# all_Slaveboard_2020.net
KiCad netlist of a schematic drawn in Altium Designer
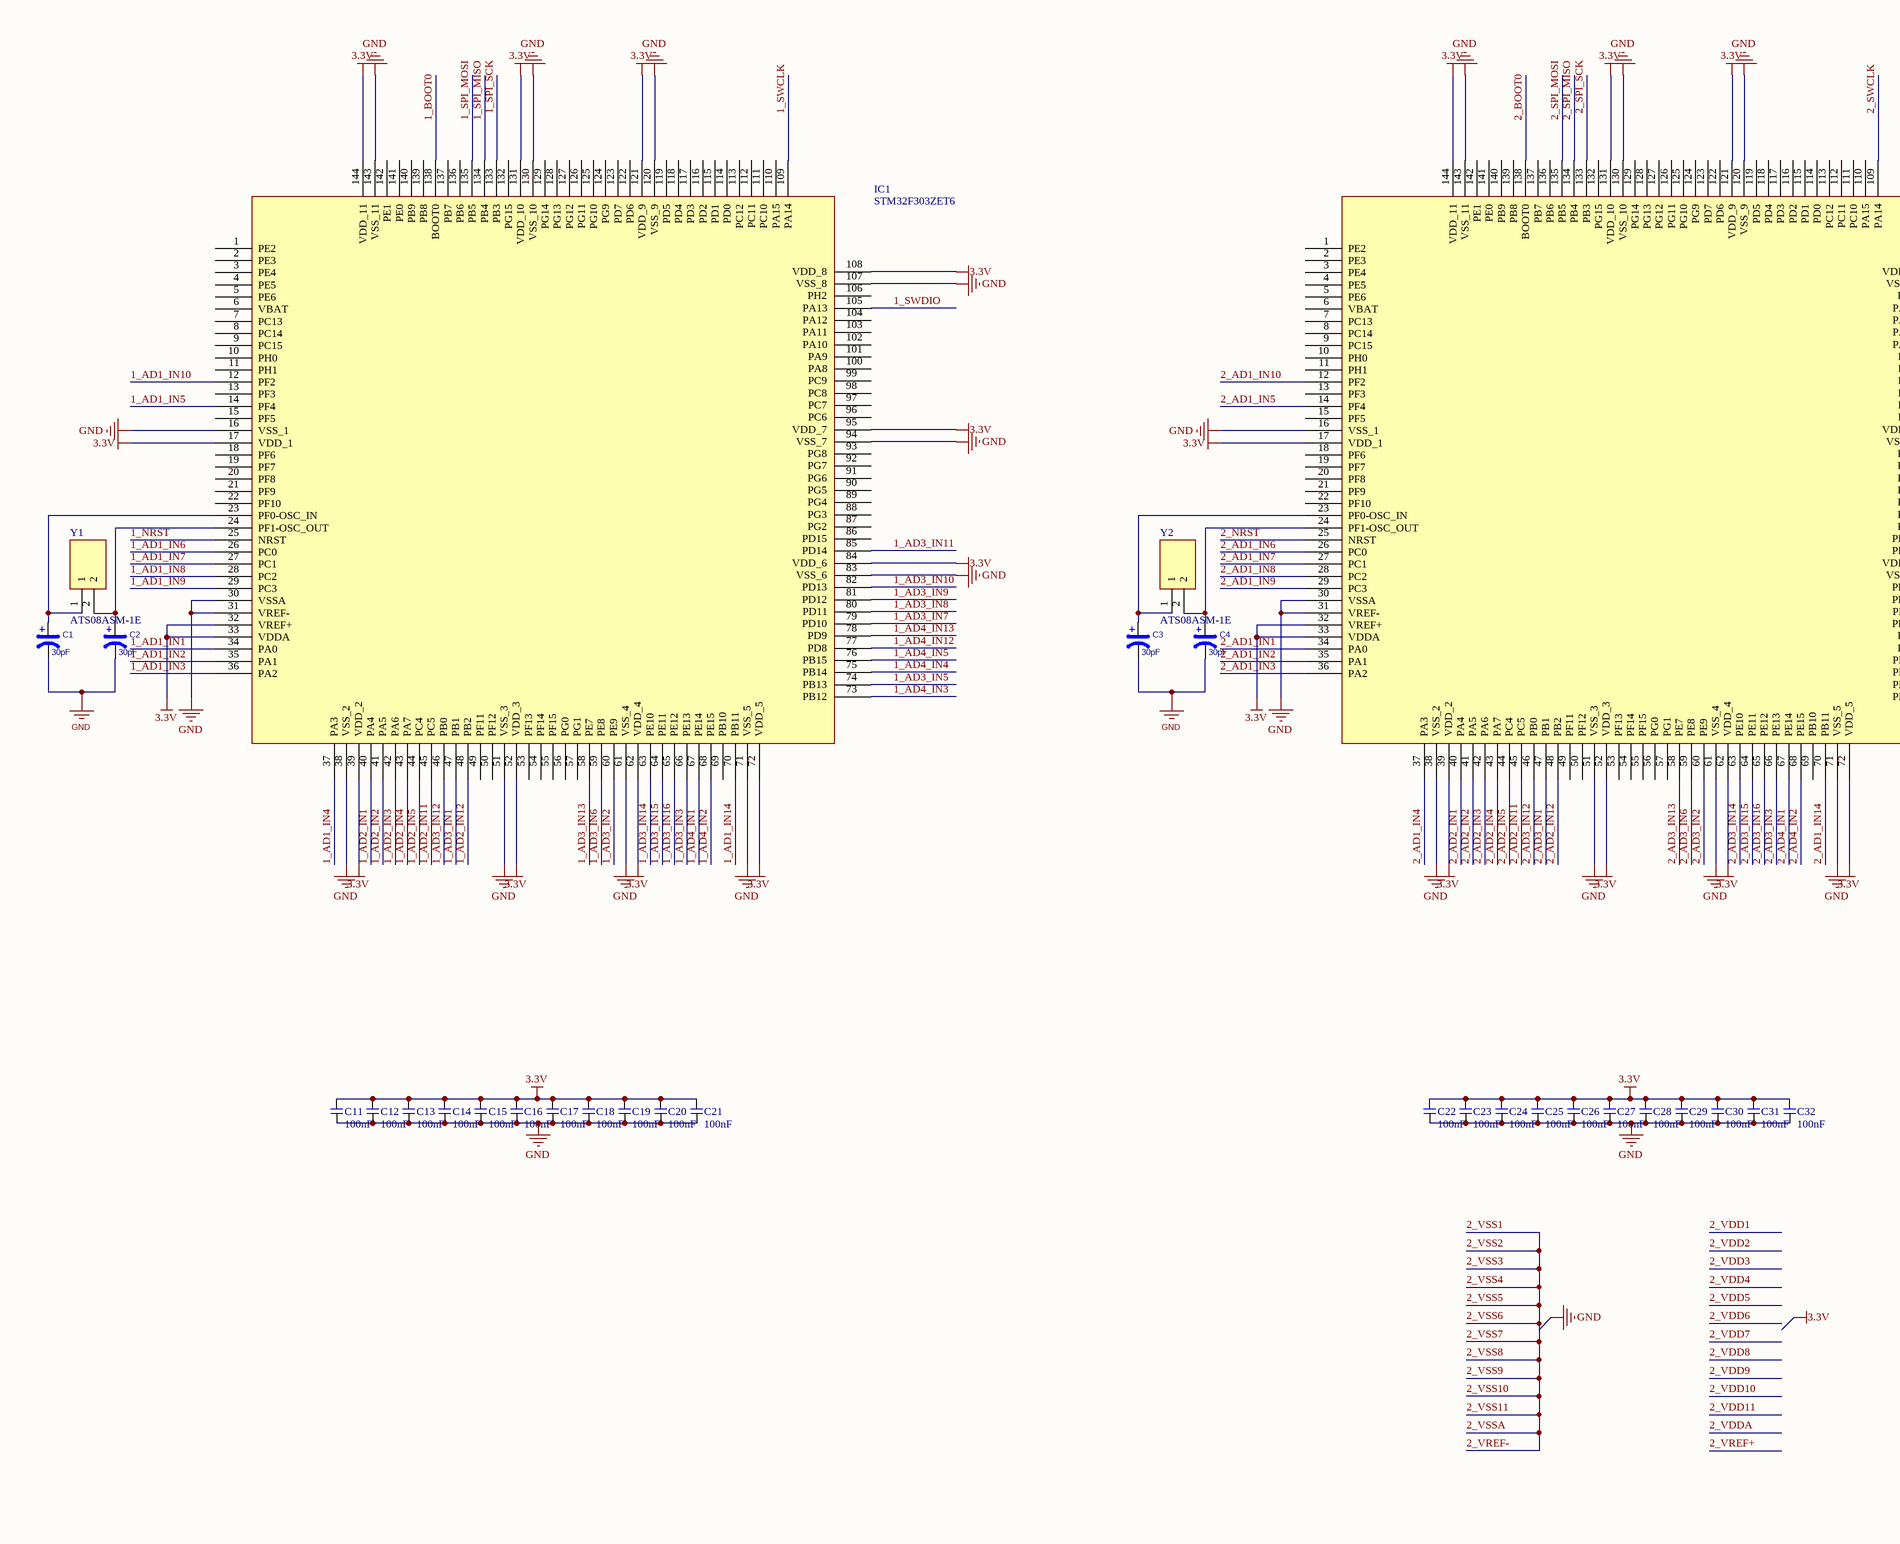
[diagram p0: all_Slaveboard_2020.SchDoc, top left]
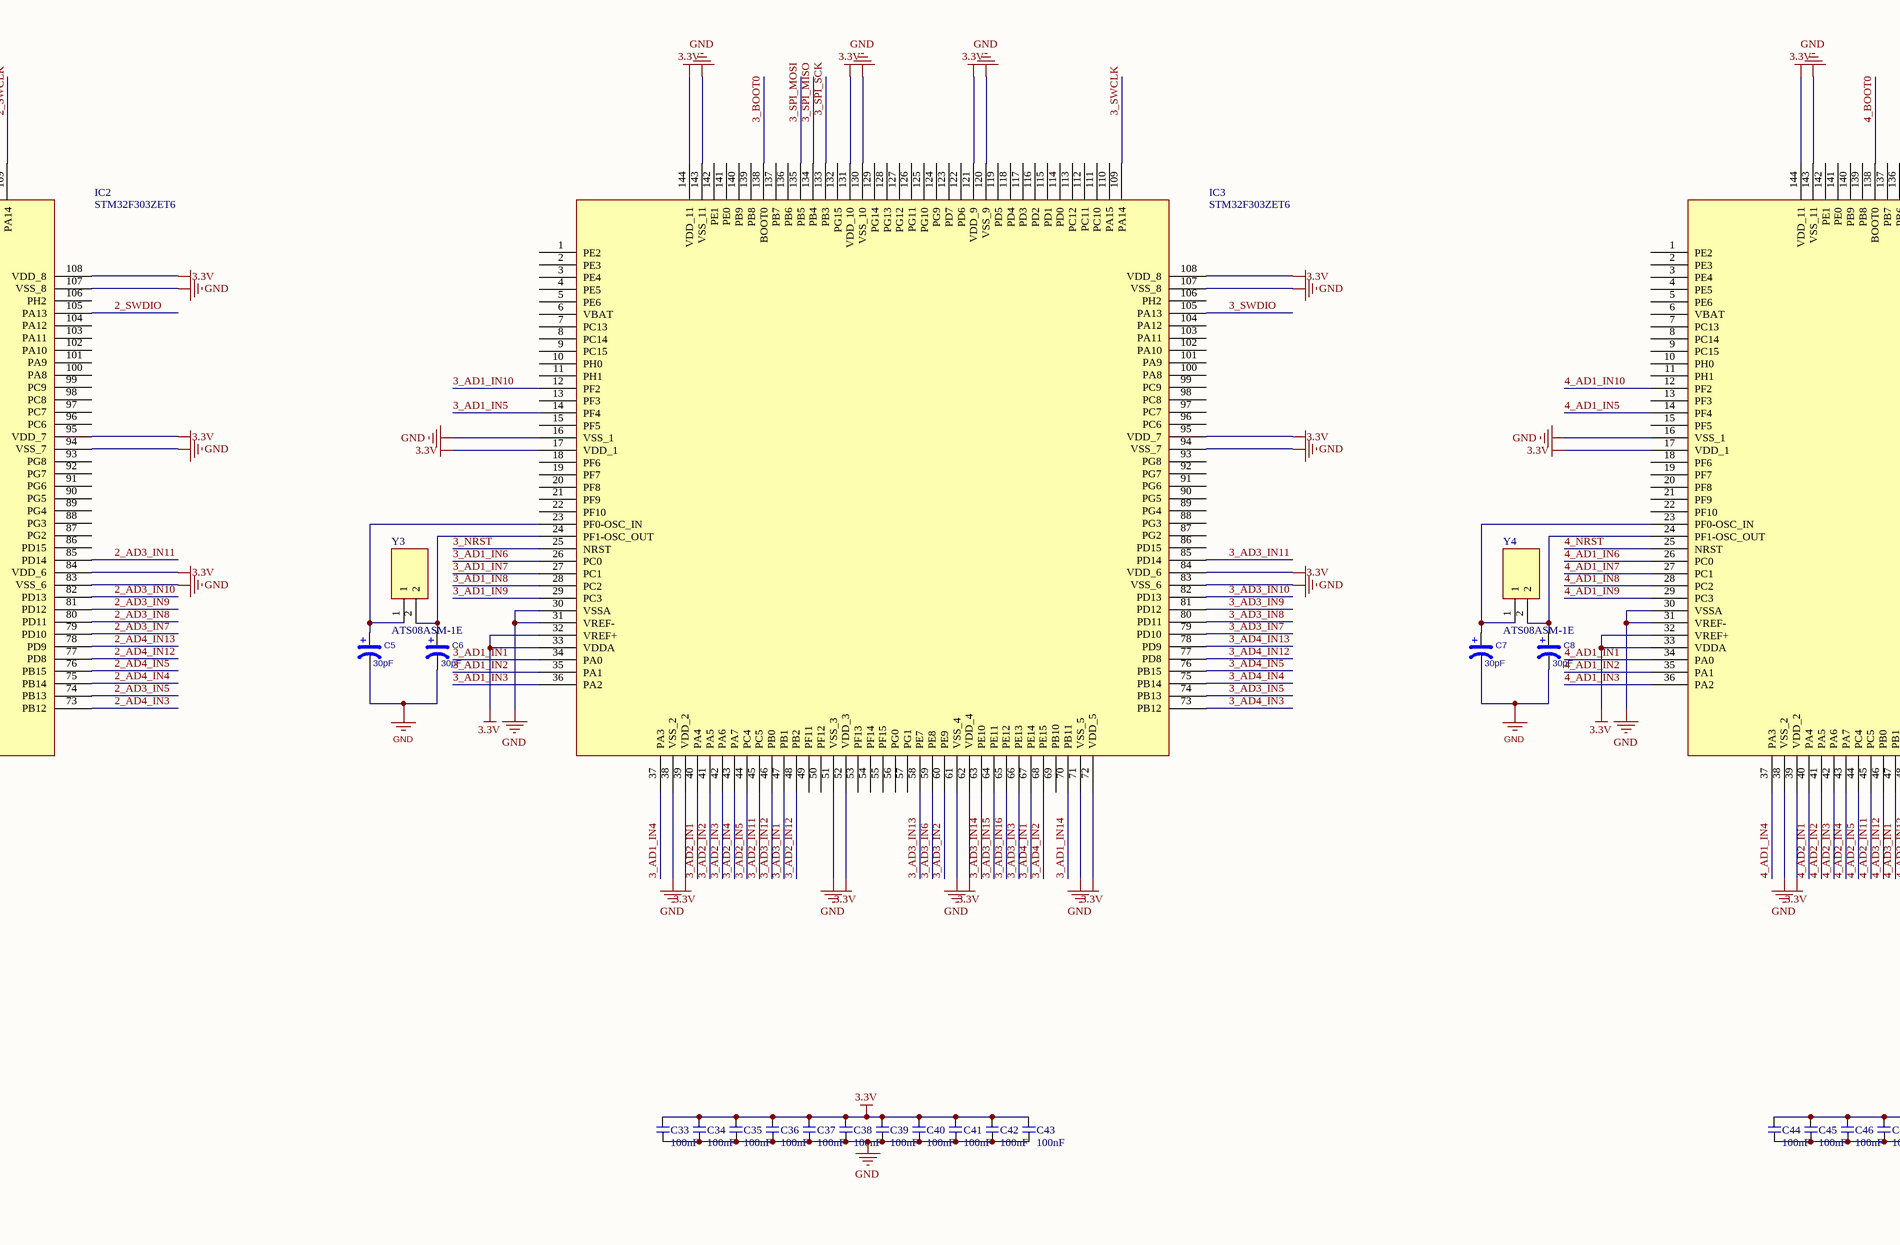
[diagram p1: all_Slaveboard_2020.SchDoc, top middle]
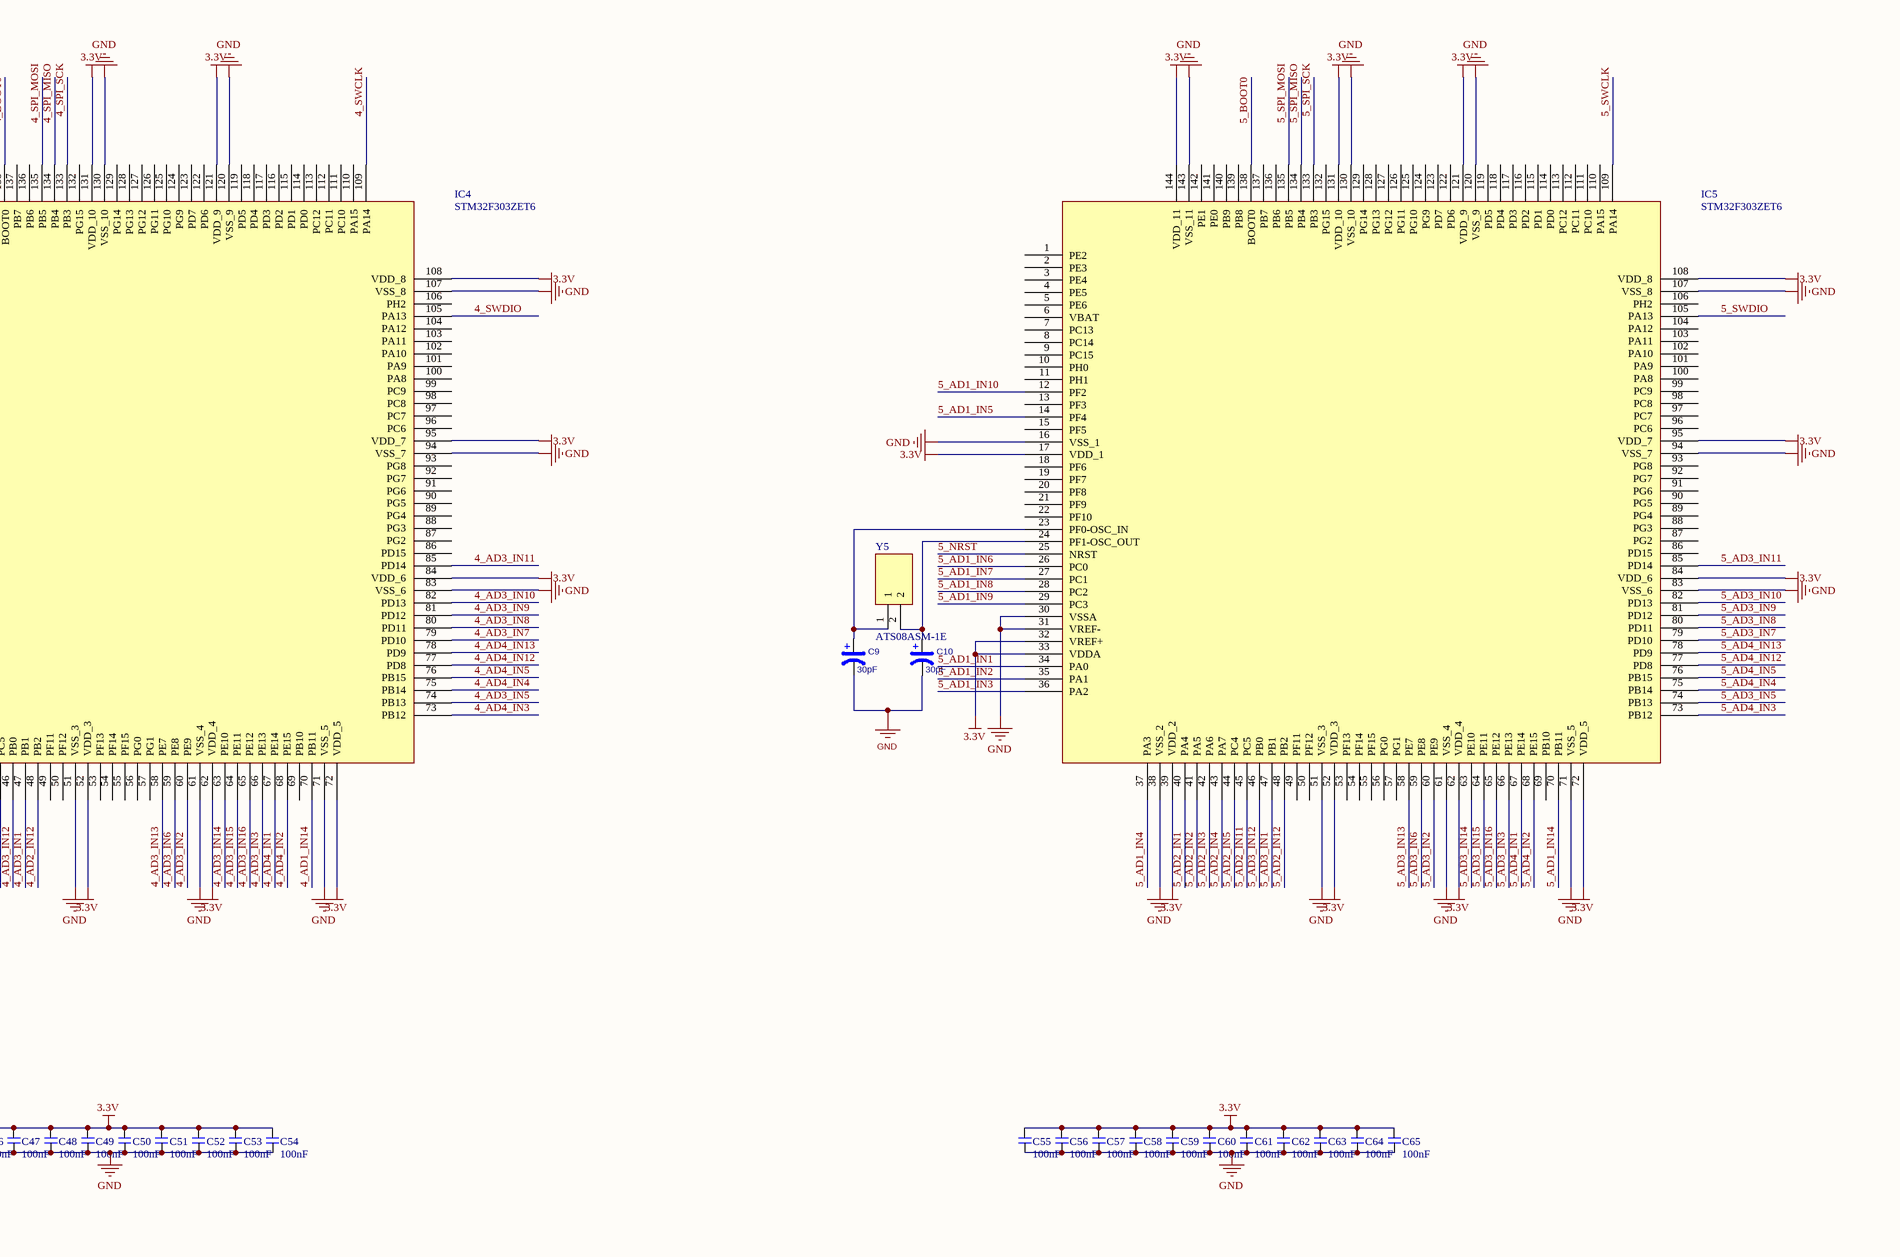
[diagram p2: all_Slaveboard_2020.SchDoc, top right]
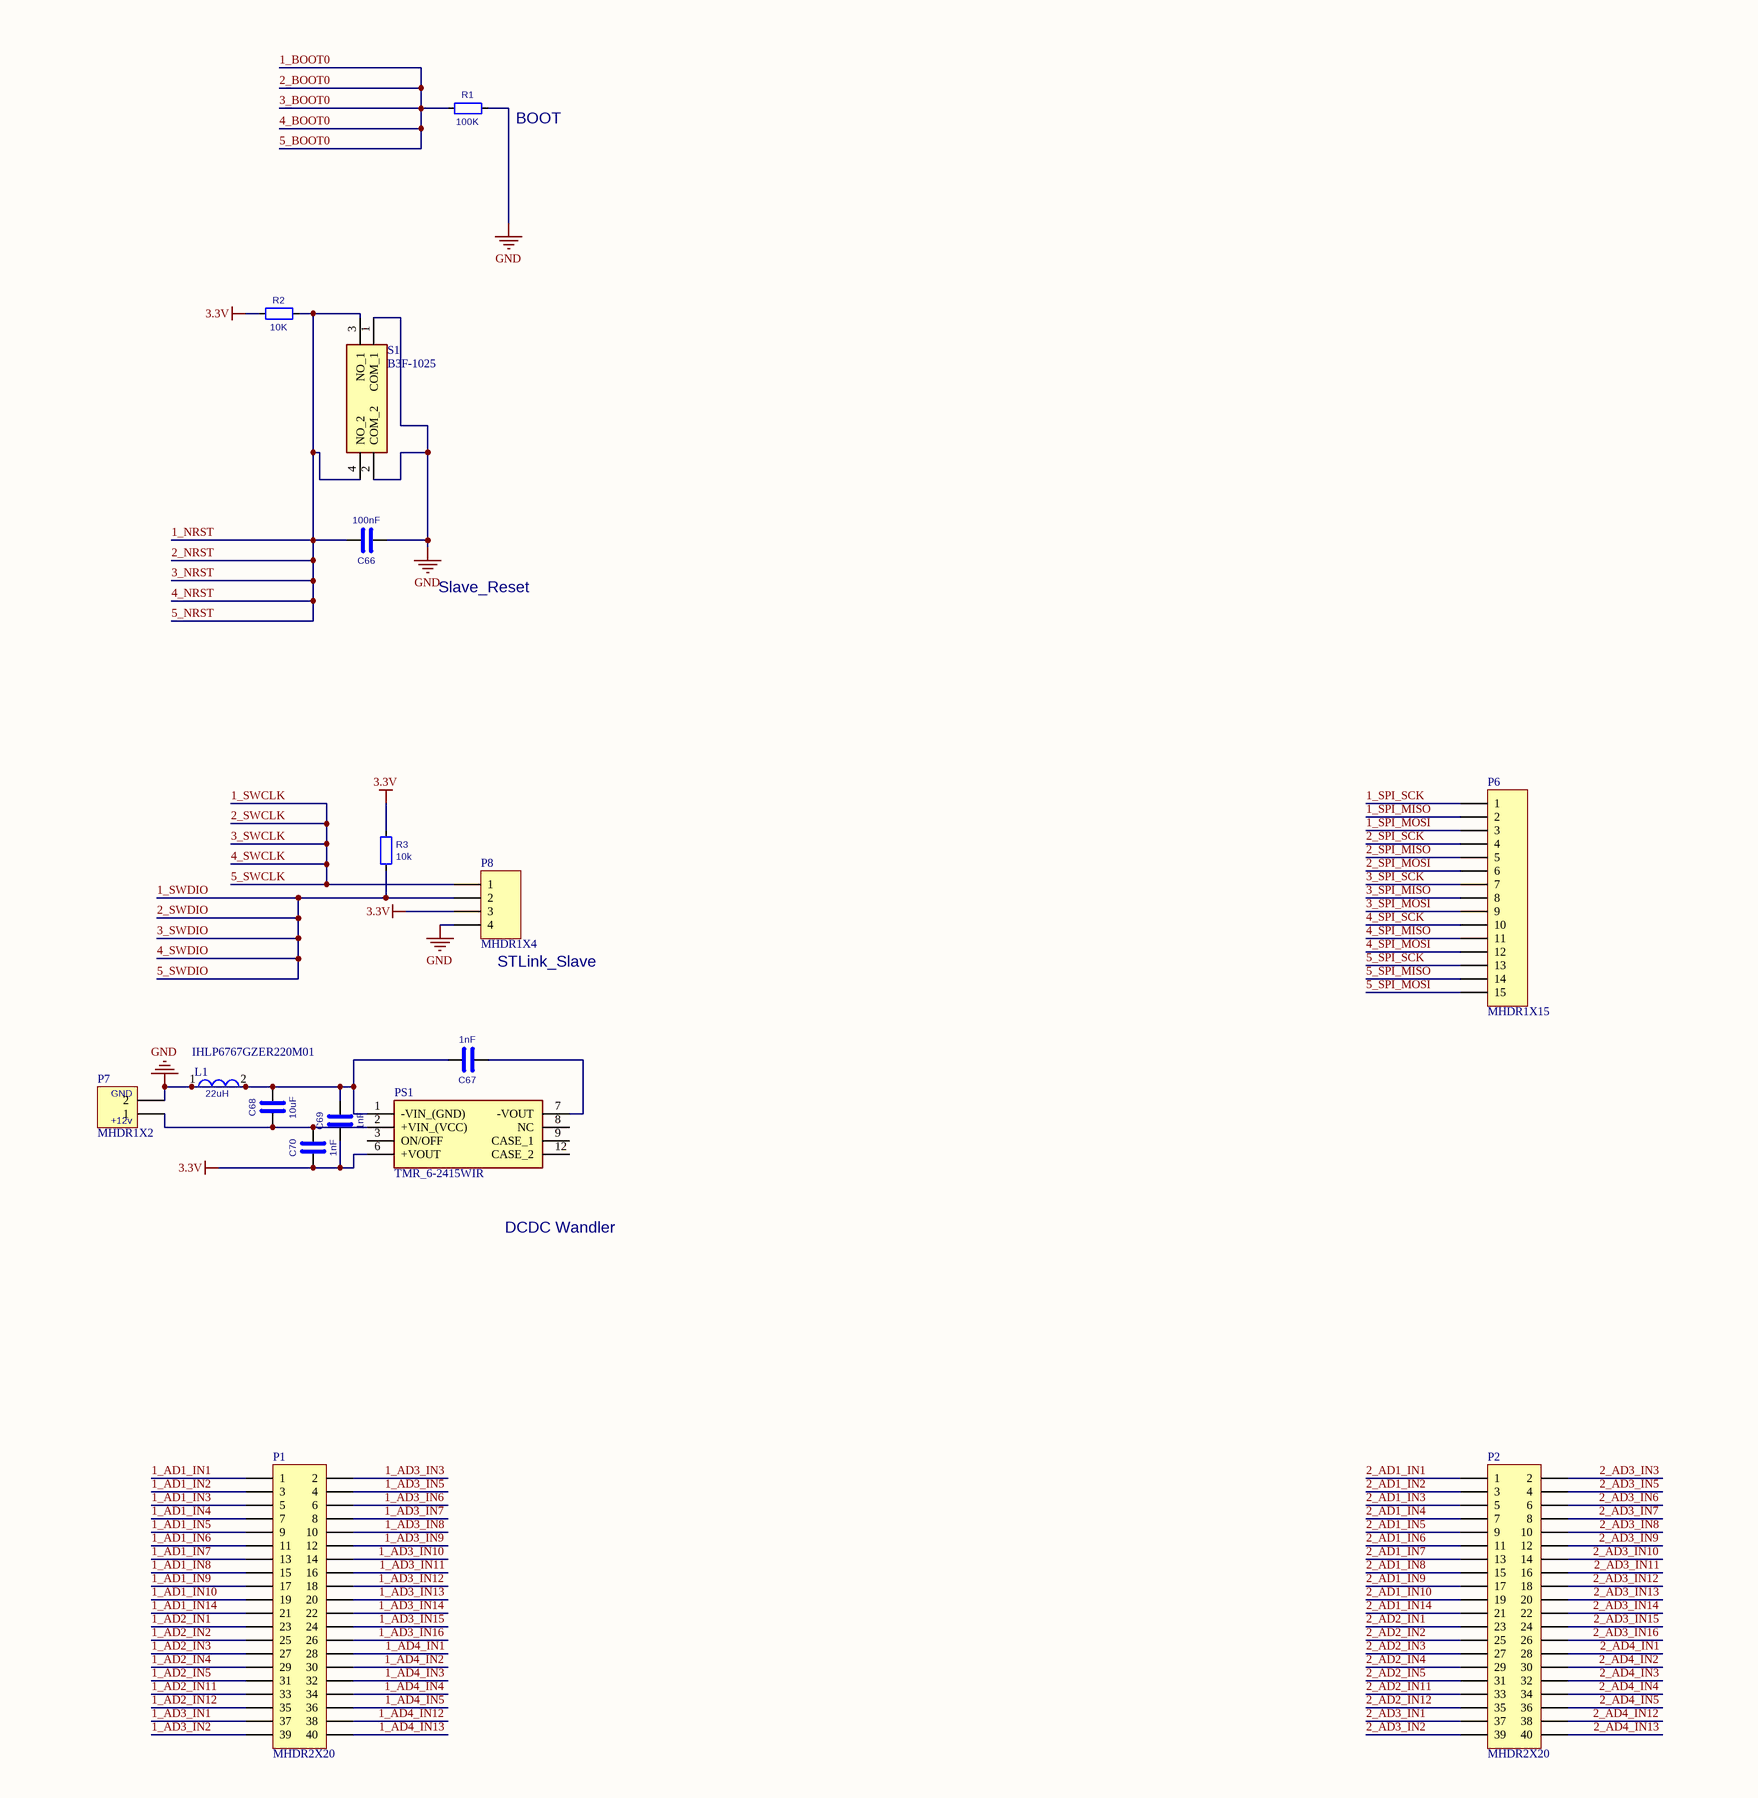
[diagram p3: all_Slaveboard_2020.SchDoc, bottom left]
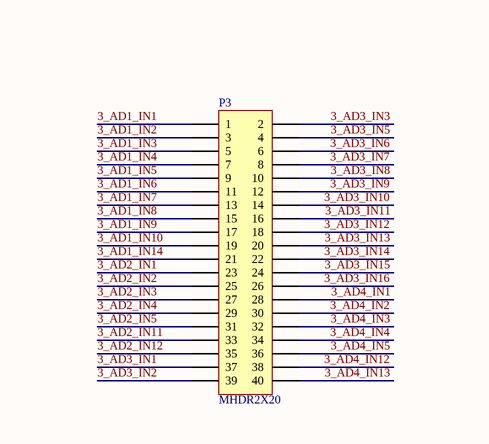
[diagram p4: all_Slaveboard_2020.SchDoc, bottom middle]
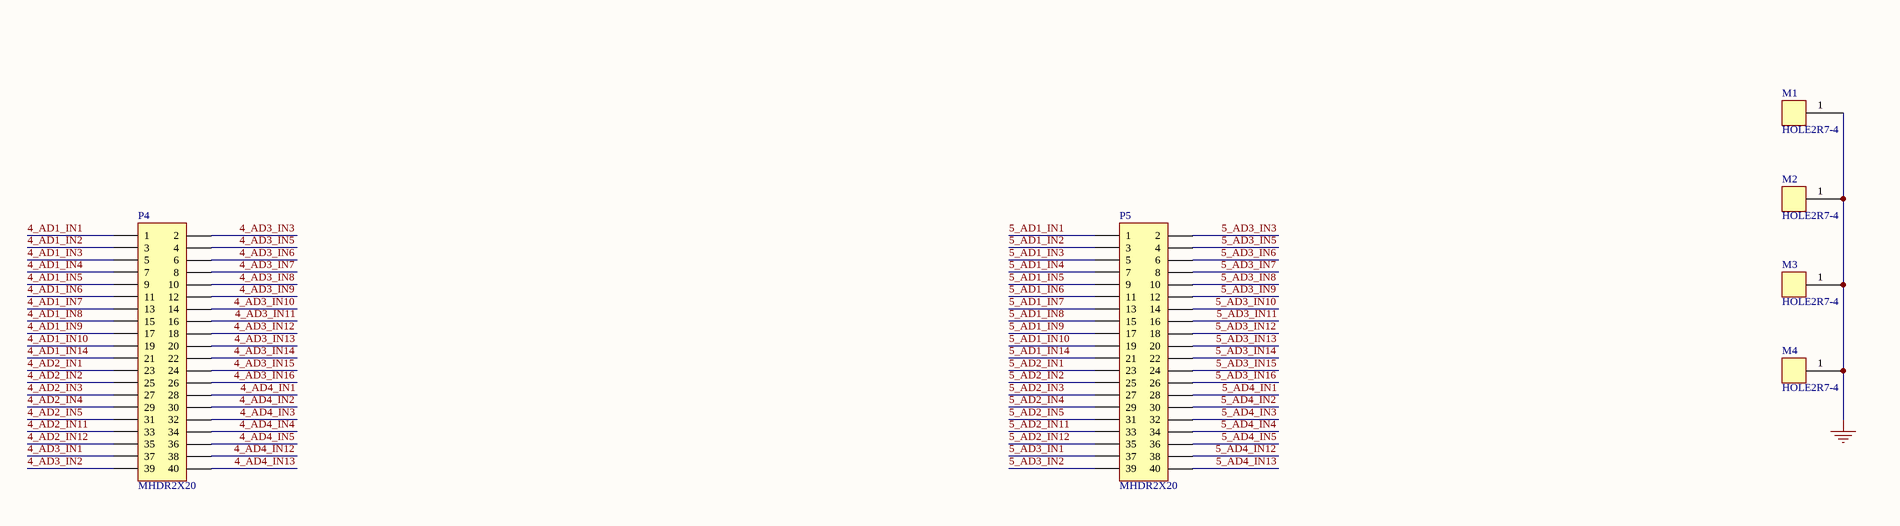
[diagram p5: all_Slaveboard_2020.SchDoc, bottom right]

(export (version "E")
  (design (tool "Eeschema 10.0.6"))
  (components
    (comp (ref "C1") (value "30pF") (footprint "c0805") (libsource (lib "Device") (part "CP1")))
    (comp (ref "C2") (value "30pF") (footprint "c0805") (libsource (lib "Device") (part "CP1")))
    (comp (ref "C3") (value "30pF") (footprint "c0805") (libsource (lib "Device") (part "CP1")))
    (comp (ref "C4") (value "30pF") (footprint "c0805") (libsource (lib "Device") (part "CP1")))
    (comp (ref "C5") (value "30pF") (footprint "c0805") (libsource (lib "Device") (part "CP1")))
    (comp (ref "C6") (value "30pF") (footprint "c0805") (libsource (lib "Device") (part "CP1")))
    (comp (ref "C7") (value "30pF") (footprint "c0805") (libsource (lib "Device") (part "CP1")))
    (comp (ref "C8") (value "30pF") (footprint "c0805") (libsource (lib "Device") (part "CP1")))
    (comp (ref "C9") (value "30pF") (footprint "c0805") (libsource (lib "Device") (part "CP1")))
    (comp (ref "C10") (value "30pF") (footprint "c0805") (libsource (lib "Device") (part "CP1")))
    (comp (ref "C11") (value "100nF") (footprint "c0201") (libsource (lib "My_Chip") (part "Cap_0805")))
    (comp (ref "C12") (value "100nF") (footprint "c0201") (libsource (lib "My_Chip") (part "Cap_0805")))
    (comp (ref "C13") (value "100nF") (footprint "c0201") (libsource (lib "My_Chip") (part "Cap_0805")))
    (comp (ref "C14") (value "100nF") (footprint "c0201") (libsource (lib "My_Chip") (part "Cap_0805")))
    (comp (ref "C15") (value "100nF") (footprint "c0201") (libsource (lib "My_Chip") (part "Cap_0805")))
    (comp (ref "C16") (value "100nF") (footprint "c0201") (libsource (lib "My_Chip") (part "Cap_0805")))
    (comp (ref "C17") (value "100nF") (footprint "c0201") (libsource (lib "My_Chip") (part "Cap_0805")))
    (comp (ref "C18") (value "100nF") (footprint "c0201") (libsource (lib "My_Chip") (part "Cap_0805")))
    (comp (ref "C19") (value "100nF") (footprint "c0201") (libsource (lib "My_Chip") (part "Cap_0805")))
    (comp (ref "C20") (value "100nF") (footprint "c0201") (libsource (lib "My_Chip") (part "Cap_0805")))
    (comp (ref "C21") (value "100nF") (footprint "c0201") (libsource (lib "My_Chip") (part "Cap_0805")))
    (comp (ref "C22") (value "100nF") (footprint "c0201") (libsource (lib "My_Chip") (part "Cap_0805")))
    (comp (ref "C23") (value "100nF") (footprint "c0201") (libsource (lib "My_Chip") (part "Cap_0805")))
    (comp (ref "C24") (value "100nF") (footprint "c0201") (libsource (lib "My_Chip") (part "Cap_0805")))
    (comp (ref "C25") (value "100nF") (footprint "c0201") (libsource (lib "My_Chip") (part "Cap_0805")))
    (comp (ref "C26") (value "100nF") (footprint "c0201") (libsource (lib "My_Chip") (part "Cap_0805")))
    (comp (ref "C27") (value "100nF") (footprint "c0201") (libsource (lib "My_Chip") (part "Cap_0805")))
    (comp (ref "C28") (value "100nF") (footprint "c0201") (libsource (lib "My_Chip") (part "Cap_0805")))
    (comp (ref "C29") (value "100nF") (footprint "c0201") (libsource (lib "My_Chip") (part "Cap_0805")))
    (comp (ref "C30") (value "100nF") (footprint "c0201") (libsource (lib "My_Chip") (part "Cap_0805")))
    (comp (ref "C31") (value "100nF") (footprint "c0201") (libsource (lib "My_Chip") (part "Cap_0805")))
    (comp (ref "C32") (value "100nF") (footprint "c0201") (libsource (lib "My_Chip") (part "Cap_0805")))
    (comp (ref "C33") (value "100nF") (footprint "c0201") (libsource (lib "My_Chip") (part "Cap_0805")))
    (comp (ref "C34") (value "100nF") (footprint "c0201") (libsource (lib "My_Chip") (part "Cap_0805")))
    (comp (ref "C35") (value "100nF") (footprint "c0201") (libsource (lib "My_Chip") (part "Cap_0805")))
    (comp (ref "C36") (value "100nF") (footprint "c0201") (libsource (lib "My_Chip") (part "Cap_0805")))
    (comp (ref "C37") (value "100nF") (footprint "c0201") (libsource (lib "My_Chip") (part "Cap_0805")))
    (comp (ref "C38") (value "100nF") (footprint "c0201") (libsource (lib "My_Chip") (part "Cap_0805")))
    (comp (ref "C39") (value "100nF") (footprint "c0201") (libsource (lib "My_Chip") (part "Cap_0805")))
    (comp (ref "C40") (value "100nF") (footprint "c0201") (libsource (lib "My_Chip") (part "Cap_0805")))
    (comp (ref "C41") (value "100nF") (footprint "c0201") (libsource (lib "My_Chip") (part "Cap_0805")))
    (comp (ref "C42") (value "100nF") (footprint "c0201") (libsource (lib "My_Chip") (part "Cap_0805")))
    (comp (ref "C43") (value "100nF") (footprint "c0201") (libsource (lib "My_Chip") (part "Cap_0805")))
    (comp (ref "C44") (value "100nF") (footprint "c0201") (libsource (lib "My_Chip") (part "Cap_0805")))
    (comp (ref "C45") (value "100nF") (footprint "c0201") (libsource (lib "My_Chip") (part "Cap_0805")))
    (comp (ref "C46") (value "100nF") (footprint "c0201") (libsource (lib "My_Chip") (part "Cap_0805")))
    (comp (ref "C47") (value "100nF") (footprint "c0201") (libsource (lib "My_Chip") (part "Cap_0805")))
    (comp (ref "C48") (value "100nF") (footprint "c0201") (libsource (lib "My_Chip") (part "Cap_0805")))
    (comp (ref "C49") (value "100nF") (footprint "c0201") (libsource (lib "My_Chip") (part "Cap_0805")))
    (comp (ref "C50") (value "100nF") (footprint "c0201") (libsource (lib "My_Chip") (part "Cap_0805")))
    (comp (ref "C51") (value "100nF") (footprint "c0201") (libsource (lib "My_Chip") (part "Cap_0805")))
    (comp (ref "C52") (value "100nF") (footprint "c0201") (libsource (lib "My_Chip") (part "Cap_0805")))
    (comp (ref "C53") (value "100nF") (footprint "c0201") (libsource (lib "My_Chip") (part "Cap_0805")))
    (comp (ref "C54") (value "100nF") (footprint "c0201") (libsource (lib "My_Chip") (part "Cap_0805")))
    (comp (ref "C55") (value "100nF") (footprint "c0201") (libsource (lib "My_Chip") (part "Cap_0805")))
    (comp (ref "C56") (value "100nF") (footprint "c0201") (libsource (lib "My_Chip") (part "Cap_0805")))
    (comp (ref "C57") (value "100nF") (footprint "c0201") (libsource (lib "My_Chip") (part "Cap_0805")))
    (comp (ref "C58") (value "100nF") (footprint "c0201") (libsource (lib "My_Chip") (part "Cap_0805")))
    (comp (ref "C59") (value "100nF") (footprint "c0201") (libsource (lib "My_Chip") (part "Cap_0805")))
    (comp (ref "C60") (value "100nF") (footprint "c0201") (libsource (lib "My_Chip") (part "Cap_0805")))
    (comp (ref "C61") (value "100nF") (footprint "c0201") (libsource (lib "My_Chip") (part "Cap_0805")))
    (comp (ref "C62") (value "100nF") (footprint "c0201") (libsource (lib "My_Chip") (part "Cap_0805")))
    (comp (ref "C63") (value "100nF") (footprint "c0201") (libsource (lib "My_Chip") (part "Cap_0805")))
    (comp (ref "C64") (value "100nF") (footprint "c0201") (libsource (lib "My_Chip") (part "Cap_0805")))
    (comp (ref "C65") (value "100nF") (footprint "c0201") (libsource (lib "My_Chip") (part "Cap_0805")))
    (comp (ref "C66") (value "100nF") (footprint "c0201") (libsource (lib "Device") (part "C")))
    (comp (ref "C67") (value "1nF") (footprint "c0201") (libsource (lib "Device") (part "C")))
    (comp (ref "C68")
      (value "10uF")
      (footprint "c0201")
      (fields (field (name "Comment") "1nF"))
      (libsource (lib "Device") (part "C"))
    )
    (comp (ref "C69") (value "1nF") (footprint "c0201") (libsource (lib "Device") (part "C")))
    (comp (ref "C70") (value "1nF") (footprint "c0201") (libsource (lib "Device") (part "C")))
    (comp (ref "IC1")
      (value "STM32F303ZET6")
      (footprint "f303QFP50P2200X2200X160-144N")
      (libsource (lib "SamacSys") (part "STM32F303ZET6"))
    )
    (comp (ref "IC2")
      (value "STM32F303ZET6")
      (footprint "f303QFP50P2200X2200X160-144N")
      (libsource (lib "SamacSys") (part "STM32F303ZET6"))
    )
    (comp (ref "IC3")
      (value "STM32F303ZET6")
      (footprint "f303QFP50P2200X2200X160-144N")
      (libsource (lib "SamacSys") (part "STM32F303ZET6"))
    )
    (comp (ref "IC4")
      (value "STM32F303ZET6")
      (footprint "f303QFP50P2200X2200X160-144N")
      (libsource (lib "SamacSys") (part "STM32F303ZET6"))
    )
    (comp (ref "IC5")
      (value "STM32F303ZET6")
      (footprint "f303QFP50P2200X2200X160-144N")
      (libsource (lib "SamacSys") (part "STM32F303ZET6"))
    )
    (comp (ref "L1")
      (value "IHLP6767GZER220M01")
      (footprint "FP-IHLP-6767GZ-FP_3_825x1-MFG")
      (description "Commercial Inductors, High Saturation Series 22uH 11A 26.5mΩ 20%")
      (fields (field (name "TOLERANCE") "20%"))
      (libsource (lib "Altium Content Vault") (part "725321dda6339637d4d059423bc1c3c"))
    )
    (comp (ref "M1")
      (value "HOLE2R7-4")
      (footprint "HOLE2R7-4")
      (libsource (lib "SamacSys") (part "HOLE2R7-4"))
    )
    (comp (ref "M2")
      (value "HOLE2R7-4")
      (footprint "HOLE2R7-4")
      (libsource (lib "SamacSys") (part "HOLE2R7-4"))
    )
    (comp (ref "M3")
      (value "HOLE2R7-4")
      (footprint "HOLE2R7-4")
      (libsource (lib "SamacSys") (part "HOLE2R7-4"))
    )
    (comp (ref "M4")
      (value "HOLE2R7-4")
      (footprint "HOLE2R7-4")
      (libsource (lib "SamacSys") (part "HOLE2R7-4"))
    )
    (comp (ref "P1")
      (value "MHDR2X20")
      (footprint "MHDR2X20")
      (description "Header, 20-Pin, Dual row")
      (fields (field (name "PUBLISHER") "Altium Limited"))
      (libsource (lib "Miscellaneous Connectors") (part "MHDR2X20"))
    )
    (comp (ref "P2")
      (value "MHDR2X20")
      (footprint "MHDR2X20")
      (description "Header, 20-Pin, Dual row")
      (fields (field (name "PUBLISHER") "Altium Limited"))
      (libsource (lib "Miscellaneous Connectors") (part "MHDR2X20"))
    )
    (comp (ref "P3")
      (value "MHDR2X20")
      (footprint "MHDR2X20")
      (description "Header, 20-Pin, Dual row")
      (fields (field (name "PUBLISHER") "Altium Limited"))
      (libsource (lib "Miscellaneous Connectors") (part "MHDR2X20"))
    )
    (comp (ref "P4")
      (value "MHDR2X20")
      (footprint "MHDR2X20")
      (description "Header, 20-Pin, Dual row")
      (fields (field (name "PUBLISHER") "Altium Limited"))
      (libsource (lib "Miscellaneous Connectors") (part "MHDR2X20"))
    )
    (comp (ref "P5")
      (value "MHDR2X20")
      (footprint "MHDR2X20")
      (description "Header, 20-Pin, Dual row")
      (fields (field (name "PUBLISHER") "Altium Limited"))
      (libsource (lib "Miscellaneous Connectors") (part "MHDR2X20"))
    )
    (comp (ref "P6")
      (value "MHDR1X15")
      (footprint "MHDR1X15")
      (description "Header, 15-Pin")
      (fields (field (name "PUBLISHER") "Altium Limited"))
      (libsource (lib "Miscellaneous Connectors") (part "MHDR1X15"))
    )
    (comp (ref "P7")
      (value "MHDR1X2")
      (footprint "MHDR1X2")
      (description "Header, 2-Pin")
      (fields (field (name "PUBLISHER") "Altium Limited"))
      (libsource (lib "Miscellaneous Connectors") (part "MHDR1X2"))
    )
    (comp (ref "P8")
      (value "MHDR1X4")
      (footprint "MHDR1X4")
      (description "Header, 4-Pin")
      (fields (field (name "PUBLISHER") "Altium Limited"))
      (libsource (lib "Miscellaneous Connectors") (part "MHDR1X4"))
    )
    (comp (ref "PS1")
      (value "TMR_6-2415WIR")
      (footprint "TMR62410WIR")
      (description "Power Supply")
      (fields
        (field (name "MANUFACTURER_PART_NUMBER") "TMR 6-2415WIR")
        (field (name "MOUSER PART NUMBER") "495-TMR6-2415WIR")
      )
      (libsource (lib "*") (part "TMR_6-2415WIR"))
    )
    (comp (ref "R1")
      (value "100K")
      (footprint "C0805")
      (fields (field (name "Comment") "10K"))
      (libsource (lib "Device") (part "R"))
    )
    (comp (ref "R2") (value "10K") (footprint "C0805") (libsource (lib "Device") (part "R")))
    (comp (ref "R3") (value "10k") (footprint "C0805") (libsource (lib "") (part "R_1")))
    (comp (ref "S1")
      (value "B3F-1025")
      (footprint "B3F1025")
      (description "Switch")
      (fields (field (name "MOUSER PART NUMBER") "653-B3F-1025"))
      (libsource (lib "*") (part "B3F-1025"))
    )
    (comp (ref "Y1")
      (value "ATS08ASM-1E")
      (footprint "ATS040SM1")
      (description "Crystal or Oscillator")
      (fields (field (name "MOUSER PART NUMBER") "774-ATS08ASM-1E"))
      (libsource (lib "*") (part "ATS08ASM-1E"))
    )
    (comp (ref "Y2")
      (value "ATS08ASM-1E")
      (footprint "ATS040SM1")
      (description "Crystal or Oscillator")
      (fields (field (name "MOUSER PART NUMBER") "774-ATS08ASM-1E"))
      (libsource (lib "*") (part "ATS08ASM-1E"))
    )
    (comp (ref "Y3")
      (value "ATS08ASM-1E")
      (footprint "ATS040SM1")
      (description "Crystal or Oscillator")
      (fields (field (name "MOUSER PART NUMBER") "774-ATS08ASM-1E"))
      (libsource (lib "*") (part "ATS08ASM-1E"))
    )
    (comp (ref "Y4")
      (value "ATS08ASM-1E")
      (footprint "ATS040SM1")
      (description "Crystal or Oscillator")
      (fields (field (name "MOUSER PART NUMBER") "774-ATS08ASM-1E"))
      (libsource (lib "*") (part "ATS08ASM-1E"))
    )
    (comp (ref "Y5")
      (value "ATS08ASM-1E")
      (footprint "ATS040SM1")
      (description "Crystal or Oscillator")
      (fields (field (name "MOUSER PART NUMBER") "774-ATS08ASM-1E"))
      (libsource (lib "*") (part "ATS08ASM-1E"))
    )
  )
  (nets
    (net (code "1") (name "/1_AD1_IN1") (class "Default")
      (node (ref "IC1") (pin "34") (pinfunction "PA0_34") (pintype "passive"))
      (node (ref "P1") (pin "1") (pinfunction "1_1") (pintype "passive"))
    )
    (net (code "2") (name "/1_AD1_IN2") (class "Default")
      (node (ref "IC1") (pin "35") (pinfunction "PA1_35") (pintype "passive"))
      (node (ref "P1") (pin "3") (pinfunction "3_3") (pintype "passive"))
    )
    (net (code "3") (name "/1_AD1_IN3") (class "Default")
      (node (ref "IC1") (pin "36") (pinfunction "PA2_36") (pintype "passive"))
      (node (ref "P1") (pin "5") (pinfunction "5_5") (pintype "passive"))
    )
    (net (code "4") (name "/1_AD1_IN4") (class "Default")
      (node (ref "IC1") (pin "37") (pinfunction "PA3_37") (pintype "passive"))
      (node (ref "P1") (pin "7") (pinfunction "7_7") (pintype "passive"))
    )
    (net (code "5") (name "/1_AD1_IN5") (class "Default")
      (node (ref "IC1") (pin "14") (pinfunction "PF4_14") (pintype "passive"))
      (node (ref "P1") (pin "9") (pinfunction "9_9") (pintype "passive"))
    )
    (net (code "6") (name "/1_AD1_IN6") (class "Default")
      (node (ref "IC1") (pin "26") (pinfunction "PC0_26") (pintype "passive"))
      (node (ref "P1") (pin "11") (pinfunction "11_11") (pintype "passive"))
    )
    (net (code "7") (name "/1_AD1_IN7") (class "Default")
      (node (ref "IC1") (pin "27") (pinfunction "PC1_27") (pintype "passive"))
      (node (ref "P1") (pin "13") (pinfunction "13_13") (pintype "passive"))
    )
    (net (code "8") (name "/1_AD1_IN8") (class "Default")
      (node (ref "IC1") (pin "28") (pinfunction "PC2_28") (pintype "passive"))
      (node (ref "P1") (pin "15") (pinfunction "15_15") (pintype "passive"))
    )
    (net (code "9") (name "/1_AD1_IN9") (class "Default")
      (node (ref "IC1") (pin "29") (pinfunction "PC3_29") (pintype "passive"))
      (node (ref "P1") (pin "17") (pinfunction "17_17") (pintype "passive"))
    )
    (net (code "10") (name "/1_AD1_IN10") (class "Default")
      (node (ref "IC1") (pin "12") (pinfunction "PF2_12") (pintype "passive"))
      (node (ref "P1") (pin "19") (pinfunction "19_19") (pintype "passive"))
    )
    (net (code "11") (name "/1_AD1_IN14") (class "Default")
      (node (ref "IC1") (pin "70") (pinfunction "PB11_70") (pintype "passive"))
      (node (ref "P1") (pin "21") (pinfunction "21_21") (pintype "passive"))
    )
    (net (code "12") (name "/1_AD2_IN1") (class "Default")
      (node (ref "IC1") (pin "40") (pinfunction "PA4_40") (pintype "passive"))
      (node (ref "P1") (pin "23") (pinfunction "23_23") (pintype "passive"))
    )
    (net (code "13") (name "/1_AD2_IN2") (class "Default")
      (node (ref "IC1") (pin "41") (pinfunction "PA5_41") (pintype "passive"))
      (node (ref "P1") (pin "25") (pinfunction "25_25") (pintype "passive"))
    )
    (net (code "14") (name "/1_AD2_IN3") (class "Default")
      (node (ref "IC1") (pin "42") (pinfunction "PA6_42") (pintype "passive"))
      (node (ref "P1") (pin "27") (pinfunction "27_27") (pintype "passive"))
    )
    (net (code "15") (name "/1_AD2_IN4") (class "Default")
      (node (ref "IC1") (pin "43") (pinfunction "PA7_43") (pintype "passive"))
      (node (ref "P1") (pin "29") (pinfunction "29_29") (pintype "passive"))
    )
    (net (code "16") (name "/1_AD2_IN5") (class "Default")
      (node (ref "IC1") (pin "44") (pinfunction "PC4_44") (pintype "passive"))
      (node (ref "P1") (pin "31") (pinfunction "31_31") (pintype "passive"))
    )
    (net (code "17") (name "/1_AD2_IN11") (class "Default")
      (node (ref "IC1") (pin "45") (pinfunction "PC5_45") (pintype "passive"))
      (node (ref "P1") (pin "33") (pinfunction "33_33") (pintype "passive"))
    )
    (net (code "18") (name "/1_AD2_IN12") (class "Default")
      (node (ref "IC1") (pin "48") (pinfunction "PB2_48") (pintype "passive"))
      (node (ref "P1") (pin "35") (pinfunction "35_35") (pintype "passive"))
    )
    (net (code "19") (name "/1_AD3_IN1") (class "Default")
      (node (ref "IC1") (pin "47") (pinfunction "PB1_47") (pintype "passive"))
      (node (ref "P1") (pin "37") (pinfunction "37_37") (pintype "passive"))
    )
    (net (code "20") (name "/1_AD3_IN2") (class "Default")
      (node (ref "IC1") (pin "60") (pinfunction "PE9_60") (pintype "passive"))
      (node (ref "P1") (pin "39") (pinfunction "39_39") (pintype "passive"))
    )
    (net (code "21") (name "/1_AD3_IN3") (class "Default")
      (node (ref "IC1") (pin "66") (pinfunction "PE13_66") (pintype "passive"))
      (node (ref "P1") (pin "2") (pinfunction "2_2") (pintype "passive"))
    )
    (net (code "22") (name "/1_AD3_IN5") (class "Default")
      (node (ref "IC1") (pin "74") (pinfunction "PB13_74") (pintype "passive"))
      (node (ref "P1") (pin "4") (pinfunction "4_4") (pintype "passive"))
    )
    (net (code "23") (name "/1_AD3_IN6") (class "Default")
      (node (ref "IC1") (pin "59") (pinfunction "PE8_59") (pintype "passive"))
      (node (ref "P1") (pin "6") (pinfunction "6_6") (pintype "passive"))
    )
    (net (code "24") (name "/1_AD3_IN7") (class "Default")
      (node (ref "IC1") (pin "79") (pinfunction "PD10_79") (pintype "passive"))
      (node (ref "P1") (pin "8") (pinfunction "8_8") (pintype "passive"))
    )
    (net (code "25") (name "/1_AD3_IN8") (class "Default")
      (node (ref "IC1") (pin "80") (pinfunction "PD11_80") (pintype "passive"))
      (node (ref "P1") (pin "10") (pinfunction "10_10") (pintype "passive"))
    )
    (net (code "26") (name "/1_AD3_IN9") (class "Default")
      (node (ref "IC1") (pin "81") (pinfunction "PD12_81") (pintype "passive"))
      (node (ref "P1") (pin "12") (pinfunction "12_12") (pintype "passive"))
    )
    (net (code "27") (name "/1_AD3_IN10") (class "Default")
      (node (ref "IC1") (pin "82") (pinfunction "PD13_82") (pintype "passive"))
      (node (ref "P1") (pin "14") (pinfunction "14_14") (pintype "passive"))
    )
    (net (code "28") (name "/1_AD3_IN11") (class "Default")
      (node (ref "IC1") (pin "85") (pinfunction "PD14_85") (pintype "passive"))
      (node (ref "P1") (pin "16") (pinfunction "16_16") (pintype "passive"))
    )
    (net (code "29") (name "/1_AD3_IN12") (class "Default")
      (node (ref "IC1") (pin "46") (pinfunction "PB0_46") (pintype "passive"))
      (node (ref "P1") (pin "18") (pinfunction "18_18") (pintype "passive"))
    )
    (net (code "30") (name "/1_AD3_IN13") (class "Default")
      (node (ref "IC1") (pin "58") (pinfunction "PE7_58") (pintype "passive"))
      (node (ref "P1") (pin "20") (pinfunction "20_20") (pintype "passive"))
    )
    (net (code "31") (name "/1_AD3_IN14") (class "Default")
      (node (ref "IC1") (pin "63") (pinfunction "PE10_63") (pintype "passive"))
      (node (ref "P1") (pin "22") (pinfunction "22_22") (pintype "passive"))
    )
    (net (code "32") (name "/1_AD3_IN15") (class "Default")
      (node (ref "IC1") (pin "64") (pinfunction "PE11_64") (pintype "passive"))
      (node (ref "P1") (pin "24") (pinfunction "24_24") (pintype "passive"))
    )
    (net (code "33") (name "/1_AD3_IN16") (class "Default")
      (node (ref "IC1") (pin "65") (pinfunction "PE12_65") (pintype "passive"))
      (node (ref "P1") (pin "26") (pinfunction "26_26") (pintype "passive"))
    )
    (net (code "34") (name "/1_AD4_IN1") (class "Default")
      (node (ref "IC1") (pin "67") (pinfunction "PE14_67") (pintype "passive"))
      (node (ref "P1") (pin "28") (pinfunction "28_28") (pintype "passive"))
    )
    (net (code "35") (name "/1_AD4_IN2") (class "Default")
      (node (ref "IC1") (pin "68") (pinfunction "PE15_68") (pintype "passive"))
      (node (ref "P1") (pin "30") (pinfunction "30_30") (pintype "passive"))
    )
    (net (code "36") (name "/1_AD4_IN3") (class "Default")
      (node (ref "IC1") (pin "73") (pinfunction "PB12_73") (pintype "passive"))
      (node (ref "P1") (pin "32") (pinfunction "32_32") (pintype "passive"))
    )
    (net (code "37") (name "/1_AD4_IN4") (class "Default")
      (node (ref "IC1") (pin "75") (pinfunction "PB14_75") (pintype "passive"))
      (node (ref "P1") (pin "34") (pinfunction "34_34") (pintype "passive"))
    )
    (net (code "38") (name "/1_AD4_IN5") (class "Default")
      (node (ref "IC1") (pin "76") (pinfunction "PB15_76") (pintype "passive"))
      (node (ref "P1") (pin "36") (pinfunction "36_36") (pintype "passive"))
    )
    (net (code "39") (name "/1_AD4_IN12") (class "Default")
      (node (ref "IC1") (pin "77") (pinfunction "PD8_77") (pintype "passive"))
      (node (ref "P1") (pin "38") (pinfunction "38_38") (pintype "passive"))
    )
    (net (code "40") (name "/1_AD4_IN13") (class "Default")
      (node (ref "IC1") (pin "78") (pinfunction "PD9_78") (pintype "passive"))
      (node (ref "P1") (pin "40") (pinfunction "40_40") (pintype "passive"))
    )
    (net (code "41") (name "/1_BOOT0") (class "Default")
      (node (ref "IC1") (pin "138") (pinfunction "BOOT0_138") (pintype "passive"))
      (node (ref "IC2") (pin "138") (pinfunction "BOOT0_138") (pintype "passive"))
      (node (ref "IC3") (pin "138") (pinfunction "BOOT0_138") (pintype "passive"))
      (node (ref "IC4") (pin "138") (pinfunction "BOOT0_138") (pintype "passive"))
      (node (ref "IC5") (pin "138") (pinfunction "BOOT0_138") (pintype "passive"))
      (node (ref "R1") (pin "2") (pinfunction "2_2") (pintype "passive"))
    )
    (net (code "42") (name "/1_NRST") (class "Default")
      (node (ref "C66") (pin "1") (pinfunction "1_1") (pintype "passive"))
      (node (ref "IC1") (pin "25") (pinfunction "NRST_25") (pintype "passive"))
      (node (ref "IC2") (pin "25") (pinfunction "NRST_25") (pintype "passive"))
      (node (ref "IC3") (pin "25") (pinfunction "NRST_25") (pintype "passive"))
      (node (ref "IC4") (pin "25") (pinfunction "NRST_25") (pintype "passive"))
      (node (ref "IC5") (pin "25") (pinfunction "NRST_25") (pintype "passive"))
      (node (ref "R2") (pin "1") (pinfunction "1_1") (pintype "passive"))
      (node (ref "S1") (pin "3") (pinfunction "NO_1_3") (pintype "passive"))
      (node (ref "S1") (pin "4") (pinfunction "NO_2_4") (pintype "passive"))
    )
    (net (code "43") (name "/1_SPI_MISO") (class "Default")
      (node (ref "IC1") (pin "134") (pinfunction "PB4_134") (pintype "passive"))
      (node (ref "P6") (pin "2") (pinfunction "2_2") (pintype "passive"))
    )
    (net (code "44") (name "/1_SPI_MOSI") (class "Default")
      (node (ref "IC1") (pin "135") (pinfunction "PB5_135") (pintype "passive"))
      (node (ref "P6") (pin "3") (pinfunction "3_3") (pintype "passive"))
    )
    (net (code "45") (name "/1_SPI_SCK") (class "Default")
      (node (ref "IC1") (pin "133") (pinfunction "PB3_133") (pintype "passive"))
      (node (ref "P6") (pin "1") (pinfunction "1_1") (pintype "passive"))
    )
    (net (code "46") (name "/1_SWCLK") (class "Default")
      (node (ref "IC1") (pin "109") (pinfunction "PA14_109") (pintype "passive"))
      (node (ref "IC2") (pin "109") (pinfunction "PA14_109") (pintype "passive"))
      (node (ref "IC3") (pin "109") (pinfunction "PA14_109") (pintype "passive"))
      (node (ref "IC4") (pin "109") (pinfunction "PA14_109") (pintype "passive"))
      (node (ref "IC5") (pin "109") (pinfunction "PA14_109") (pintype "passive"))
      (node (ref "P8") (pin "1") (pinfunction "1_1") (pintype "passive"))
    )
    (net (code "47") (name "/1_SWDIO") (class "Default")
      (node (ref "IC1") (pin "105") (pinfunction "PA13_105") (pintype "passive"))
      (node (ref "IC2") (pin "105") (pinfunction "PA13_105") (pintype "passive"))
      (node (ref "IC3") (pin "105") (pinfunction "PA13_105") (pintype "passive"))
      (node (ref "IC4") (pin "105") (pinfunction "PA13_105") (pintype "passive"))
      (node (ref "IC5") (pin "105") (pinfunction "PA13_105") (pintype "passive"))
      (node (ref "P8") (pin "2") (pinfunction "2_2") (pintype "passive"))
      (node (ref "R3") (pin "2") (pinfunction "2_2") (pintype "passive"))
    )
    (net (code "48") (name "/2_AD1_IN1") (class "Default")
      (node (ref "IC2") (pin "34") (pinfunction "PA0_34") (pintype "passive"))
      (node (ref "P2") (pin "1") (pinfunction "1_1") (pintype "passive"))
    )
    (net (code "49") (name "/2_AD1_IN2") (class "Default")
      (node (ref "IC2") (pin "35") (pinfunction "PA1_35") (pintype "passive"))
      (node (ref "P2") (pin "3") (pinfunction "3_3") (pintype "passive"))
    )
    (net (code "50") (name "/2_AD1_IN3") (class "Default")
      (node (ref "IC2") (pin "36") (pinfunction "PA2_36") (pintype "passive"))
      (node (ref "P2") (pin "5") (pinfunction "5_5") (pintype "passive"))
    )
    (net (code "51") (name "/2_AD1_IN4") (class "Default")
      (node (ref "IC2") (pin "37") (pinfunction "PA3_37") (pintype "passive"))
      (node (ref "P2") (pin "7") (pinfunction "7_7") (pintype "passive"))
    )
    (net (code "52") (name "/2_AD1_IN5") (class "Default")
      (node (ref "IC2") (pin "14") (pinfunction "PF4_14") (pintype "passive"))
      (node (ref "P2") (pin "9") (pinfunction "9_9") (pintype "passive"))
    )
    (net (code "53") (name "/2_AD1_IN6") (class "Default")
      (node (ref "IC2") (pin "26") (pinfunction "PC0_26") (pintype "passive"))
      (node (ref "P2") (pin "11") (pinfunction "11_11") (pintype "passive"))
    )
    (net (code "54") (name "/2_AD1_IN7") (class "Default")
      (node (ref "IC2") (pin "27") (pinfunction "PC1_27") (pintype "passive"))
      (node (ref "P2") (pin "13") (pinfunction "13_13") (pintype "passive"))
    )
    (net (code "55") (name "/2_AD1_IN8") (class "Default")
      (node (ref "IC2") (pin "28") (pinfunction "PC2_28") (pintype "passive"))
      (node (ref "P2") (pin "15") (pinfunction "15_15") (pintype "passive"))
    )
    (net (code "56") (name "/2_AD1_IN9") (class "Default")
      (node (ref "IC2") (pin "29") (pinfunction "PC3_29") (pintype "passive"))
      (node (ref "P2") (pin "17") (pinfunction "17_17") (pintype "passive"))
    )
    (net (code "57") (name "/2_AD1_IN10") (class "Default")
      (node (ref "IC2") (pin "12") (pinfunction "PF2_12") (pintype "passive"))
      (node (ref "P2") (pin "19") (pinfunction "19_19") (pintype "passive"))
    )
    (net (code "58") (name "/2_AD1_IN14") (class "Default")
      (node (ref "IC2") (pin "70") (pinfunction "PB11_70") (pintype "passive"))
      (node (ref "P2") (pin "21") (pinfunction "21_21") (pintype "passive"))
    )
    (net (code "59") (name "/2_AD2_IN1") (class "Default")
      (node (ref "IC2") (pin "40") (pinfunction "PA4_40") (pintype "passive"))
      (node (ref "P2") (pin "23") (pinfunction "23_23") (pintype "passive"))
    )
    (net (code "60") (name "/2_AD2_IN2") (class "Default")
      (node (ref "IC2") (pin "41") (pinfunction "PA5_41") (pintype "passive"))
      (node (ref "P2") (pin "25") (pinfunction "25_25") (pintype "passive"))
    )
    (net (code "61") (name "/2_AD2_IN3") (class "Default")
      (node (ref "IC2") (pin "42") (pinfunction "PA6_42") (pintype "passive"))
      (node (ref "P2") (pin "27") (pinfunction "27_27") (pintype "passive"))
    )
    (net (code "62") (name "/2_AD2_IN4") (class "Default")
      (node (ref "IC2") (pin "43") (pinfunction "PA7_43") (pintype "passive"))
      (node (ref "P2") (pin "29") (pinfunction "29_29") (pintype "passive"))
    )
    (net (code "63") (name "/2_AD2_IN5") (class "Default")
      (node (ref "IC2") (pin "44") (pinfunction "PC4_44") (pintype "passive"))
      (node (ref "P2") (pin "31") (pinfunction "31_31") (pintype "passive"))
    )
    (net (code "64") (name "/2_AD2_IN11") (class "Default")
      (node (ref "IC2") (pin "45") (pinfunction "PC5_45") (pintype "passive"))
      (node (ref "P2") (pin "33") (pinfunction "33_33") (pintype "passive"))
    )
    (net (code "65") (name "/2_AD2_IN12") (class "Default")
      (node (ref "IC2") (pin "48") (pinfunction "PB2_48") (pintype "passive"))
      (node (ref "P2") (pin "35") (pinfunction "35_35") (pintype "passive"))
    )
    (net (code "66") (name "/2_AD3_IN1") (class "Default")
      (node (ref "IC2") (pin "47") (pinfunction "PB1_47") (pintype "passive"))
      (node (ref "P2") (pin "37") (pinfunction "37_37") (pintype "passive"))
    )
    (net (code "67") (name "/2_AD3_IN2") (class "Default")
      (node (ref "IC2") (pin "60") (pinfunction "PE9_60") (pintype "passive"))
      (node (ref "P2") (pin "39") (pinfunction "39_39") (pintype "passive"))
    )
    (net (code "68") (name "/2_AD3_IN3") (class "Default")
      (node (ref "IC2") (pin "66") (pinfunction "PE13_66") (pintype "passive"))
      (node (ref "P2") (pin "2") (pinfunction "2_2") (pintype "passive"))
    )
    (net (code "69") (name "/2_AD3_IN5") (class "Default")
      (node (ref "IC2") (pin "74") (pinfunction "PB13_74") (pintype "passive"))
      (node (ref "P2") (pin "4") (pinfunction "4_4") (pintype "passive"))
    )
    (net (code "70") (name "/2_AD3_IN6") (class "Default")
      (node (ref "IC2") (pin "59") (pinfunction "PE8_59") (pintype "passive"))
      (node (ref "P2") (pin "6") (pinfunction "6_6") (pintype "passive"))
    )
    (net (code "71") (name "/2_AD3_IN7") (class "Default")
      (node (ref "IC2") (pin "79") (pinfunction "PD10_79") (pintype "passive"))
      (node (ref "P2") (pin "8") (pinfunction "8_8") (pintype "passive"))
    )
    (net (code "72") (name "/2_AD3_IN8") (class "Default")
      (node (ref "IC2") (pin "80") (pinfunction "PD11_80") (pintype "passive"))
      (node (ref "P2") (pin "10") (pinfunction "10_10") (pintype "passive"))
    )
    (net (code "73") (name "/2_AD3_IN9") (class "Default")
      (node (ref "IC2") (pin "81") (pinfunction "PD12_81") (pintype "passive"))
      (node (ref "P2") (pin "12") (pinfunction "12_12") (pintype "passive"))
    )
    (net (code "74") (name "/2_AD3_IN10") (class "Default")
      (node (ref "IC2") (pin "82") (pinfunction "PD13_82") (pintype "passive"))
      (node (ref "P2") (pin "14") (pinfunction "14_14") (pintype "passive"))
    )
    (net (code "75") (name "/2_AD3_IN11") (class "Default")
      (node (ref "IC2") (pin "85") (pinfunction "PD14_85") (pintype "passive"))
      (node (ref "P2") (pin "16") (pinfunction "16_16") (pintype "passive"))
    )
    (net (code "76") (name "/2_AD3_IN12") (class "Default")
      (node (ref "IC2") (pin "46") (pinfunction "PB0_46") (pintype "passive"))
      (node (ref "P2") (pin "18") (pinfunction "18_18") (pintype "passive"))
    )
    (net (code "77") (name "/2_AD3_IN13") (class "Default")
      (node (ref "IC2") (pin "58") (pinfunction "PE7_58") (pintype "passive"))
      (node (ref "P2") (pin "20") (pinfunction "20_20") (pintype "passive"))
    )
    (net (code "78") (name "/2_AD3_IN14") (class "Default")
      (node (ref "IC2") (pin "63") (pinfunction "PE10_63") (pintype "passive"))
      (node (ref "P2") (pin "22") (pinfunction "22_22") (pintype "passive"))
    )
    (net (code "79") (name "/2_AD3_IN15") (class "Default")
      (node (ref "IC2") (pin "64") (pinfunction "PE11_64") (pintype "passive"))
      (node (ref "P2") (pin "24") (pinfunction "24_24") (pintype "passive"))
    )
    (net (code "80") (name "/2_AD3_IN16") (class "Default")
      (node (ref "IC2") (pin "65") (pinfunction "PE12_65") (pintype "passive"))
      (node (ref "P2") (pin "26") (pinfunction "26_26") (pintype "passive"))
    )
    (net (code "81") (name "/2_AD4_IN1") (class "Default")
      (node (ref "IC2") (pin "67") (pinfunction "PE14_67") (pintype "passive"))
      (node (ref "P2") (pin "28") (pinfunction "28_28") (pintype "passive"))
    )
    (net (code "82") (name "/2_AD4_IN2") (class "Default")
      (node (ref "IC2") (pin "68") (pinfunction "PE15_68") (pintype "passive"))
      (node (ref "P2") (pin "30") (pinfunction "30_30") (pintype "passive"))
    )
    (net (code "83") (name "/2_AD4_IN3") (class "Default")
      (node (ref "IC2") (pin "73") (pinfunction "PB12_73") (pintype "passive"))
      (node (ref "P2") (pin "32") (pinfunction "32_32") (pintype "passive"))
    )
    (net (code "84") (name "/2_AD4_IN4") (class "Default")
      (node (ref "IC2") (pin "75") (pinfunction "PB14_75") (pintype "passive"))
      (node (ref "P2") (pin "34") (pinfunction "34_34") (pintype "passive"))
    )
    (net (code "85") (name "/2_AD4_IN5") (class "Default")
      (node (ref "IC2") (pin "76") (pinfunction "PB15_76") (pintype "passive"))
      (node (ref "P2") (pin "36") (pinfunction "36_36") (pintype "passive"))
    )
    (net (code "86") (name "/2_AD4_IN12") (class "Default")
      (node (ref "IC2") (pin "77") (pinfunction "PD8_77") (pintype "passive"))
      (node (ref "P2") (pin "38") (pinfunction "38_38") (pintype "passive"))
    )
    (net (code "87") (name "/2_AD4_IN13") (class "Default")
      (node (ref "IC2") (pin "78") (pinfunction "PD9_78") (pintype "passive"))
      (node (ref "P2") (pin "40") (pinfunction "40_40") (pintype "passive"))
    )
    (net (code "88") (name "/2_SPI_MISO") (class "Default")
      (node (ref "IC2") (pin "134") (pinfunction "PB4_134") (pintype "passive"))
      (node (ref "P6") (pin "5") (pinfunction "5_5") (pintype "passive"))
    )
    (net (code "89") (name "/2_SPI_MOSI") (class "Default")
      (node (ref "IC2") (pin "135") (pinfunction "PB5_135") (pintype "passive"))
      (node (ref "P6") (pin "6") (pinfunction "6_6") (pintype "passive"))
    )
    (net (code "90") (name "/2_SPI_SCK") (class "Default")
      (node (ref "IC2") (pin "133") (pinfunction "PB3_133") (pintype "passive"))
      (node (ref "P6") (pin "4") (pinfunction "4_4") (pintype "passive"))
    )
    (net (code "105") (name "/3_AD1_IN1") (class "Default")
      (node (ref "IC3") (pin "34") (pinfunction "PA0_34") (pintype "passive"))
      (node (ref "P3") (pin "1") (pinfunction "1_1") (pintype "passive"))
    )
    (net (code "106") (name "/3_AD1_IN2") (class "Default")
      (node (ref "IC3") (pin "35") (pinfunction "PA1_35") (pintype "passive"))
      (node (ref "P3") (pin "3") (pinfunction "3_3") (pintype "passive"))
    )
    (net (code "107") (name "/3_AD1_IN3") (class "Default")
      (node (ref "IC3") (pin "36") (pinfunction "PA2_36") (pintype "passive"))
      (node (ref "P3") (pin "5") (pinfunction "5_5") (pintype "passive"))
    )
    (net (code "108") (name "/3_AD1_IN4") (class "Default")
      (node (ref "IC3") (pin "37") (pinfunction "PA3_37") (pintype "passive"))
      (node (ref "P3") (pin "7") (pinfunction "7_7") (pintype "passive"))
    )
    (net (code "109") (name "/3_AD1_IN5") (class "Default")
      (node (ref "IC3") (pin "14") (pinfunction "PF4_14") (pintype "passive"))
      (node (ref "P3") (pin "9") (pinfunction "9_9") (pintype "passive"))
    )
    (net (code "110") (name "/3_AD1_IN6") (class "Default")
      (node (ref "IC3") (pin "26") (pinfunction "PC0_26") (pintype "passive"))
      (node (ref "P3") (pin "11") (pinfunction "11_11") (pintype "passive"))
    )
    (net (code "111") (name "/3_AD1_IN7") (class "Default")
      (node (ref "IC3") (pin "27") (pinfunction "PC1_27") (pintype "passive"))
      (node (ref "P3") (pin "13") (pinfunction "13_13") (pintype "passive"))
    )
    (net (code "112") (name "/3_AD1_IN8") (class "Default")
      (node (ref "IC3") (pin "28") (pinfunction "PC2_28") (pintype "passive"))
      (node (ref "P3") (pin "15") (pinfunction "15_15") (pintype "passive"))
    )
    (net (code "113") (name "/3_AD1_IN9") (class "Default")
      (node (ref "IC3") (pin "29") (pinfunction "PC3_29") (pintype "passive"))
      (node (ref "P3") (pin "17") (pinfunction "17_17") (pintype "passive"))
    )
    (net (code "114") (name "/3_AD1_IN10") (class "Default")
      (node (ref "IC3") (pin "12") (pinfunction "PF2_12") (pintype "passive"))
      (node (ref "P3") (pin "19") (pinfunction "19_19") (pintype "passive"))
    )
    (net (code "115") (name "/3_AD1_IN14") (class "Default")
      (node (ref "IC3") (pin "70") (pinfunction "PB11_70") (pintype "passive"))
      (node (ref "P3") (pin "21") (pinfunction "21_21") (pintype "passive"))
    )
    (net (code "116") (name "/3_AD2_IN1") (class "Default")
      (node (ref "IC3") (pin "40") (pinfunction "PA4_40") (pintype "passive"))
      (node (ref "P3") (pin "23") (pinfunction "23_23") (pintype "passive"))
    )
    (net (code "117") (name "/3_AD2_IN2") (class "Default")
      (node (ref "IC3") (pin "41") (pinfunction "PA5_41") (pintype "passive"))
      (node (ref "P3") (pin "25") (pinfunction "25_25") (pintype "passive"))
    )
    (net (code "118") (name "/3_AD2_IN3") (class "Default")
      (node (ref "IC3") (pin "42") (pinfunction "PA6_42") (pintype "passive"))
      (node (ref "P3") (pin "27") (pinfunction "27_27") (pintype "passive"))
    )
    (net (code "119") (name "/3_AD2_IN4") (class "Default")
      (node (ref "IC3") (pin "43") (pinfunction "PA7_43") (pintype "passive"))
      (node (ref "P3") (pin "29") (pinfunction "29_29") (pintype "passive"))
    )
    (net (code "120") (name "/3_AD2_IN5") (class "Default")
      (node (ref "IC3") (pin "44") (pinfunction "PC4_44") (pintype "passive"))
      (node (ref "P3") (pin "31") (pinfunction "31_31") (pintype "passive"))
    )
    (net (code "121") (name "/3_AD2_IN11") (class "Default")
      (node (ref "IC3") (pin "45") (pinfunction "PC5_45") (pintype "passive"))
      (node (ref "P3") (pin "33") (pinfunction "33_33") (pintype "passive"))
    )
    (net (code "122") (name "/3_AD2_IN12") (class "Default")
      (node (ref "IC3") (pin "48") (pinfunction "PB2_48") (pintype "passive"))
      (node (ref "P3") (pin "35") (pinfunction "35_35") (pintype "passive"))
    )
    (net (code "123") (name "/3_AD3_IN1") (class "Default")
      (node (ref "IC3") (pin "47") (pinfunction "PB1_47") (pintype "passive"))
      (node (ref "P3") (pin "37") (pinfunction "37_37") (pintype "passive"))
    )
    (net (code "124") (name "/3_AD3_IN2") (class "Default")
      (node (ref "IC3") (pin "60") (pinfunction "PE9_60") (pintype "passive"))
      (node (ref "P3") (pin "39") (pinfunction "39_39") (pintype "passive"))
    )
    (net (code "125") (name "/3_AD3_IN3") (class "Default")
      (node (ref "IC3") (pin "66") (pinfunction "PE13_66") (pintype "passive"))
      (node (ref "P3") (pin "2") (pinfunction "2_2") (pintype "passive"))
    )
    (net (code "126") (name "/3_AD3_IN5") (class "Default")
      (node (ref "IC3") (pin "74") (pinfunction "PB13_74") (pintype "passive"))
      (node (ref "P3") (pin "4") (pinfunction "4_4") (pintype "passive"))
    )
    (net (code "127") (name "/3_AD3_IN6") (class "Default")
      (node (ref "IC3") (pin "59") (pinfunction "PE8_59") (pintype "passive"))
      (node (ref "P3") (pin "6") (pinfunction "6_6") (pintype "passive"))
    )
    (net (code "128") (name "/3_AD3_IN7") (class "Default")
      (node (ref "IC3") (pin "79") (pinfunction "PD10_79") (pintype "passive"))
      (node (ref "P3") (pin "8") (pinfunction "8_8") (pintype "passive"))
    )
    (net (code "129") (name "/3_AD3_IN8") (class "Default")
      (node (ref "IC3") (pin "80") (pinfunction "PD11_80") (pintype "passive"))
      (node (ref "P3") (pin "10") (pinfunction "10_10") (pintype "passive"))
    )
    (net (code "130") (name "/3_AD3_IN9") (class "Default")
      (node (ref "IC3") (pin "81") (pinfunction "PD12_81") (pintype "passive"))
      (node (ref "P3") (pin "12") (pinfunction "12_12") (pintype "passive"))
    )
    (net (code "131") (name "/3_AD3_IN10") (class "Default")
      (node (ref "IC3") (pin "82") (pinfunction "PD13_82") (pintype "passive"))
      (node (ref "P3") (pin "14") (pinfunction "14_14") (pintype "passive"))
    )
    (net (code "132") (name "/3_AD3_IN11") (class "Default")
      (node (ref "IC3") (pin "85") (pinfunction "PD14_85") (pintype "passive"))
      (node (ref "P3") (pin "16") (pinfunction "16_16") (pintype "passive"))
    )
    (net (code "133") (name "/3_AD3_IN12") (class "Default")
      (node (ref "IC3") (pin "46") (pinfunction "PB0_46") (pintype "passive"))
      (node (ref "P3") (pin "18") (pinfunction "18_18") (pintype "passive"))
    )
    (net (code "134") (name "/3_AD3_IN13") (class "Default")
      (node (ref "IC3") (pin "58") (pinfunction "PE7_58") (pintype "passive"))
      (node (ref "P3") (pin "20") (pinfunction "20_20") (pintype "passive"))
    )
    (net (code "135") (name "/3_AD3_IN14") (class "Default")
      (node (ref "IC3") (pin "63") (pinfunction "PE10_63") (pintype "passive"))
      (node (ref "P3") (pin "22") (pinfunction "22_22") (pintype "passive"))
    )
    (net (code "136") (name "/3_AD3_IN15") (class "Default")
      (node (ref "IC3") (pin "64") (pinfunction "PE11_64") (pintype "passive"))
      (node (ref "P3") (pin "24") (pinfunction "24_24") (pintype "passive"))
    )
    (net (code "137") (name "/3_AD3_IN16") (class "Default")
      (node (ref "IC3") (pin "65") (pinfunction "PE12_65") (pintype "passive"))
      (node (ref "P3") (pin "26") (pinfunction "26_26") (pintype "passive"))
    )
    (net (code "138") (name "/3_AD4_IN1") (class "Default")
      (node (ref "IC3") (pin "67") (pinfunction "PE14_67") (pintype "passive"))
      (node (ref "P3") (pin "28") (pinfunction "28_28") (pintype "passive"))
    )
    (net (code "139") (name "/3_AD4_IN2") (class "Default")
      (node (ref "IC3") (pin "68") (pinfunction "PE15_68") (pintype "passive"))
      (node (ref "P3") (pin "30") (pinfunction "30_30") (pintype "passive"))
    )
    (net (code "140") (name "/3_AD4_IN3") (class "Default")
      (node (ref "IC3") (pin "73") (pinfunction "PB12_73") (pintype "passive"))
      (node (ref "P3") (pin "32") (pinfunction "32_32") (pintype "passive"))
    )
    (net (code "141") (name "/3_AD4_IN4") (class "Default")
      (node (ref "IC3") (pin "75") (pinfunction "PB14_75") (pintype "passive"))
      (node (ref "P3") (pin "34") (pinfunction "34_34") (pintype "passive"))
    )
    (net (code "142") (name "/3_AD4_IN5") (class "Default")
      (node (ref "IC3") (pin "76") (pinfunction "PB15_76") (pintype "passive"))
      (node (ref "P3") (pin "36") (pinfunction "36_36") (pintype "passive"))
    )
    (net (code "143") (name "/3_AD4_IN12") (class "Default")
      (node (ref "IC3") (pin "77") (pinfunction "PD8_77") (pintype "passive"))
      (node (ref "P3") (pin "38") (pinfunction "38_38") (pintype "passive"))
    )
    (net (code "144") (name "/3_AD4_IN13") (class "Default")
      (node (ref "IC3") (pin "78") (pinfunction "PD9_78") (pintype "passive"))
      (node (ref "P3") (pin "40") (pinfunction "40_40") (pintype "passive"))
    )
    (net (code "145") (name "/3_SPI_MISO") (class "Default")
      (node (ref "IC3") (pin "134") (pinfunction "PB4_134") (pintype "passive"))
      (node (ref "P6") (pin "8") (pinfunction "8_8") (pintype "passive"))
    )
    (net (code "146") (name "/3_SPI_MOSI") (class "Default")
      (node (ref "IC3") (pin "135") (pinfunction "PB5_135") (pintype "passive"))
      (node (ref "P6") (pin "9") (pinfunction "9_9") (pintype "passive"))
    )
    (net (code "147") (name "/3_SPI_SCK") (class "Default")
      (node (ref "IC3") (pin "133") (pinfunction "PB3_133") (pintype "passive"))
      (node (ref "P6") (pin "7") (pinfunction "7_7") (pintype "passive"))
    )
    (net (code "148") (name "/4_AD1_IN1") (class "Default")
      (node (ref "IC4") (pin "34") (pinfunction "PA0_34") (pintype "passive"))
      (node (ref "P4") (pin "1") (pinfunction "1_1") (pintype "passive"))
    )
    (net (code "149") (name "/4_AD1_IN2") (class "Default")
      (node (ref "IC4") (pin "35") (pinfunction "PA1_35") (pintype "passive"))
      (node (ref "P4") (pin "3") (pinfunction "3_3") (pintype "passive"))
    )
    (net (code "150") (name "/4_AD1_IN3") (class "Default")
      (node (ref "IC4") (pin "36") (pinfunction "PA2_36") (pintype "passive"))
      (node (ref "P4") (pin "5") (pinfunction "5_5") (pintype "passive"))
    )
    (net (code "151") (name "/4_AD1_IN4") (class "Default")
      (node (ref "IC4") (pin "37") (pinfunction "PA3_37") (pintype "passive"))
      (node (ref "P4") (pin "7") (pinfunction "7_7") (pintype "passive"))
    )
    (net (code "152") (name "/4_AD1_IN5") (class "Default")
      (node (ref "IC4") (pin "14") (pinfunction "PF4_14") (pintype "passive"))
      (node (ref "P4") (pin "9") (pinfunction "9_9") (pintype "passive"))
    )
    (net (code "153") (name "/4_AD1_IN6") (class "Default")
      (node (ref "IC4") (pin "26") (pinfunction "PC0_26") (pintype "passive"))
      (node (ref "P4") (pin "11") (pinfunction "11_11") (pintype "passive"))
    )
    (net (code "154") (name "/4_AD1_IN7") (class "Default")
      (node (ref "IC4") (pin "27") (pinfunction "PC1_27") (pintype "passive"))
      (node (ref "P4") (pin "13") (pinfunction "13_13") (pintype "passive"))
    )
    (net (code "155") (name "/4_AD1_IN8") (class "Default")
      (node (ref "IC4") (pin "28") (pinfunction "PC2_28") (pintype "passive"))
      (node (ref "P4") (pin "15") (pinfunction "15_15") (pintype "passive"))
    )
    (net (code "156") (name "/4_AD1_IN9") (class "Default")
      (node (ref "IC4") (pin "29") (pinfunction "PC3_29") (pintype "passive"))
      (node (ref "P4") (pin "17") (pinfunction "17_17") (pintype "passive"))
    )
    (net (code "157") (name "/4_AD1_IN10") (class "Default")
      (node (ref "IC4") (pin "12") (pinfunction "PF2_12") (pintype "passive"))
      (node (ref "P4") (pin "19") (pinfunction "19_19") (pintype "passive"))
    )
    (net (code "158") (name "/4_AD1_IN14") (class "Default")
      (node (ref "IC4") (pin "70") (pinfunction "PB11_70") (pintype "passive"))
      (node (ref "P4") (pin "21") (pinfunction "21_21") (pintype "passive"))
    )
    (net (code "159") (name "/4_AD2_IN1") (class "Default")
      (node (ref "IC4") (pin "40") (pinfunction "PA4_40") (pintype "passive"))
      (node (ref "P4") (pin "23") (pinfunction "23_23") (pintype "passive"))
    )
    (net (code "160") (name "/4_AD2_IN2") (class "Default")
      (node (ref "IC4") (pin "41") (pinfunction "PA5_41") (pintype "passive"))
      (node (ref "P4") (pin "25") (pinfunction "25_25") (pintype "passive"))
    )
    (net (code "161") (name "/4_AD2_IN3") (class "Default")
      (node (ref "IC4") (pin "42") (pinfunction "PA6_42") (pintype "passive"))
      (node (ref "P4") (pin "27") (pinfunction "27_27") (pintype "passive"))
    )
    (net (code "162") (name "/4_AD2_IN4") (class "Default")
      (node (ref "IC4") (pin "43") (pinfunction "PA7_43") (pintype "passive"))
      (node (ref "P4") (pin "29") (pinfunction "29_29") (pintype "passive"))
    )
    (net (code "163") (name "/4_AD2_IN5") (class "Default")
      (node (ref "IC4") (pin "44") (pinfunction "PC4_44") (pintype "passive"))
      (node (ref "P4") (pin "31") (pinfunction "31_31") (pintype "passive"))
    )
    (net (code "164") (name "/4_AD2_IN11") (class "Default")
      (node (ref "IC4") (pin "45") (pinfunction "PC5_45") (pintype "passive"))
      (node (ref "P4") (pin "33") (pinfunction "33_33") (pintype "passive"))
    )
    (net (code "165") (name "/4_AD2_IN12") (class "Default")
      (node (ref "IC4") (pin "48") (pinfunction "PB2_48") (pintype "passive"))
      (node (ref "P4") (pin "35") (pinfunction "35_35") (pintype "passive"))
    )
    (net (code "166") (name "/4_AD3_IN1") (class "Default")
      (node (ref "IC4") (pin "47") (pinfunction "PB1_47") (pintype "passive"))
      (node (ref "P4") (pin "37") (pinfunction "37_37") (pintype "passive"))
    )
    (net (code "167") (name "/4_AD3_IN2") (class "Default")
      (node (ref "IC4") (pin "60") (pinfunction "PE9_60") (pintype "passive"))
      (node (ref "P4") (pin "39") (pinfunction "39_39") (pintype "passive"))
    )
    (net (code "168") (name "/4_AD3_IN3") (class "Default")
      (node (ref "IC4") (pin "66") (pinfunction "PE13_66") (pintype "passive"))
      (node (ref "P4") (pin "2") (pinfunction "2_2") (pintype "passive"))
    )
    (net (code "169") (name "/4_AD3_IN5") (class "Default")
      (node (ref "IC4") (pin "74") (pinfunction "PB13_74") (pintype "passive"))
      (node (ref "P4") (pin "4") (pinfunction "4_4") (pintype "passive"))
    )
    (net (code "170") (name "/4_AD3_IN6") (class "Default")
      (node (ref "IC4") (pin "59") (pinfunction "PE8_59") (pintype "passive"))
      (node (ref "P4") (pin "6") (pinfunction "6_6") (pintype "passive"))
    )
    (net (code "171") (name "/4_AD3_IN7") (class "Default")
      (node (ref "IC4") (pin "79") (pinfunction "PD10_79") (pintype "passive"))
      (node (ref "P4") (pin "8") (pinfunction "8_8") (pintype "passive"))
    )
    (net (code "172") (name "/4_AD3_IN8") (class "Default")
      (node (ref "IC4") (pin "80") (pinfunction "PD11_80") (pintype "passive"))
      (node (ref "P4") (pin "10") (pinfunction "10_10") (pintype "passive"))
    )
    (net (code "173") (name "/4_AD3_IN9") (class "Default")
      (node (ref "IC4") (pin "81") (pinfunction "PD12_81") (pintype "passive"))
      (node (ref "P4") (pin "12") (pinfunction "12_12") (pintype "passive"))
    )
    (net (code "174") (name "/4_AD3_IN10") (class "Default")
      (node (ref "IC4") (pin "82") (pinfunction "PD13_82") (pintype "passive"))
      (node (ref "P4") (pin "14") (pinfunction "14_14") (pintype "passive"))
    )
    (net (code "175") (name "/4_AD3_IN11") (class "Default")
      (node (ref "IC4") (pin "85") (pinfunction "PD14_85") (pintype "passive"))
      (node (ref "P4") (pin "16") (pinfunction "16_16") (pintype "passive"))
    )
    (net (code "176") (name "/4_AD3_IN12") (class "Default")
      (node (ref "IC4") (pin "46") (pinfunction "PB0_46") (pintype "passive"))
      (node (ref "P4") (pin "18") (pinfunction "18_18") (pintype "passive"))
    )
    (net (code "177") (name "/4_AD3_IN13") (class "Default")
      (node (ref "IC4") (pin "58") (pinfunction "PE7_58") (pintype "passive"))
      (node (ref "P4") (pin "20") (pinfunction "20_20") (pintype "passive"))
    )
    (net (code "178") (name "/4_AD3_IN14") (class "Default")
      (node (ref "IC4") (pin "63") (pinfunction "PE10_63") (pintype "passive"))
      (node (ref "P4") (pin "22") (pinfunction "22_22") (pintype "passive"))
    )
    (net (code "179") (name "/4_AD3_IN15") (class "Default")
      (node (ref "IC4") (pin "64") (pinfunction "PE11_64") (pintype "passive"))
      (node (ref "P4") (pin "24") (pinfunction "24_24") (pintype "passive"))
    )
    (net (code "180") (name "/4_AD3_IN16") (class "Default")
      (node (ref "IC4") (pin "65") (pinfunction "PE12_65") (pintype "passive"))
      (node (ref "P4") (pin "26") (pinfunction "26_26") (pintype "passive"))
    )
    (net (code "181") (name "/4_AD4_IN1") (class "Default")
      (node (ref "IC4") (pin "67") (pinfunction "PE14_67") (pintype "passive"))
      (node (ref "P4") (pin "28") (pinfunction "28_28") (pintype "passive"))
    )
    (net (code "182") (name "/4_AD4_IN2") (class "Default")
      (node (ref "IC4") (pin "68") (pinfunction "PE15_68") (pintype "passive"))
      (node (ref "P4") (pin "30") (pinfunction "30_30") (pintype "passive"))
    )
    (net (code "183") (name "/4_AD4_IN3") (class "Default")
      (node (ref "IC4") (pin "73") (pinfunction "PB12_73") (pintype "passive"))
      (node (ref "P4") (pin "32") (pinfunction "32_32") (pintype "passive"))
    )
    (net (code "184") (name "/4_AD4_IN4") (class "Default")
      (node (ref "IC4") (pin "75") (pinfunction "PB14_75") (pintype "passive"))
      (node (ref "P4") (pin "34") (pinfunction "34_34") (pintype "passive"))
    )
    (net (code "185") (name "/4_AD4_IN5") (class "Default")
      (node (ref "IC4") (pin "76") (pinfunction "PB15_76") (pintype "passive"))
      (node (ref "P4") (pin "36") (pinfunction "36_36") (pintype "passive"))
    )
    (net (code "186") (name "/4_AD4_IN12") (class "Default")
      (node (ref "IC4") (pin "77") (pinfunction "PD8_77") (pintype "passive"))
      (node (ref "P4") (pin "38") (pinfunction "38_38") (pintype "passive"))
    )
    (net (code "187") (name "/4_AD4_IN13") (class "Default")
      (node (ref "IC4") (pin "78") (pinfunction "PD9_78") (pintype "passive"))
      (node (ref "P4") (pin "40") (pinfunction "40_40") (pintype "passive"))
    )
    (net (code "188") (name "/4_SPI_MISO") (class "Default")
      (node (ref "IC4") (pin "134") (pinfunction "PB4_134") (pintype "passive"))
      (node (ref "P6") (pin "11") (pinfunction "11_11") (pintype "passive"))
    )
    (net (code "189") (name "/4_SPI_MOSI") (class "Default")
      (node (ref "IC4") (pin "135") (pinfunction "PB5_135") (pintype "passive"))
      (node (ref "P6") (pin "12") (pinfunction "12_12") (pintype "passive"))
    )
    (net (code "190") (name "/4_SPI_SCK") (class "Default")
      (node (ref "IC4") (pin "133") (pinfunction "PB3_133") (pintype "passive"))
      (node (ref "P6") (pin "10") (pinfunction "10_10") (pintype "passive"))
    )
    (net (code "191") (name "/5_AD1_IN1") (class "Default")
      (node (ref "IC5") (pin "34") (pinfunction "PA0_34") (pintype "passive"))
      (node (ref "P5") (pin "1") (pinfunction "1_1") (pintype "passive"))
    )
    (net (code "192") (name "/5_AD1_IN2") (class "Default")
      (node (ref "IC5") (pin "35") (pinfunction "PA1_35") (pintype "passive"))
      (node (ref "P5") (pin "3") (pinfunction "3_3") (pintype "passive"))
    )
    (net (code "193") (name "/5_AD1_IN3") (class "Default")
      (node (ref "IC5") (pin "36") (pinfunction "PA2_36") (pintype "passive"))
      (node (ref "P5") (pin "5") (pinfunction "5_5") (pintype "passive"))
    )
    (net (code "194") (name "/5_AD1_IN4") (class "Default")
      (node (ref "IC5") (pin "37") (pinfunction "PA3_37") (pintype "passive"))
      (node (ref "P5") (pin "7") (pinfunction "7_7") (pintype "passive"))
    )
    (net (code "195") (name "/5_AD1_IN5") (class "Default")
      (node (ref "IC5") (pin "14") (pinfunction "PF4_14") (pintype "passive"))
      (node (ref "P5") (pin "9") (pinfunction "9_9") (pintype "passive"))
    )
    (net (code "196") (name "/5_AD1_IN6") (class "Default")
      (node (ref "IC5") (pin "26") (pinfunction "PC0_26") (pintype "passive"))
      (node (ref "P5") (pin "11") (pinfunction "11_11") (pintype "passive"))
    )
    (net (code "197") (name "/5_AD1_IN7") (class "Default")
      (node (ref "IC5") (pin "27") (pinfunction "PC1_27") (pintype "passive"))
      (node (ref "P5") (pin "13") (pinfunction "13_13") (pintype "passive"))
    )
    (net (code "198") (name "/5_AD1_IN8") (class "Default")
      (node (ref "IC5") (pin "28") (pinfunction "PC2_28") (pintype "passive"))
      (node (ref "P5") (pin "15") (pinfunction "15_15") (pintype "passive"))
    )
    (net (code "199") (name "/5_AD1_IN9") (class "Default")
      (node (ref "IC5") (pin "29") (pinfunction "PC3_29") (pintype "passive"))
      (node (ref "P5") (pin "17") (pinfunction "17_17") (pintype "passive"))
    )
    (net (code "200") (name "/5_AD1_IN10") (class "Default")
      (node (ref "IC5") (pin "12") (pinfunction "PF2_12") (pintype "passive"))
      (node (ref "P5") (pin "19") (pinfunction "19_19") (pintype "passive"))
    )
    (net (code "201") (name "/5_AD1_IN14") (class "Default")
      (node (ref "IC5") (pin "70") (pinfunction "PB11_70") (pintype "passive"))
      (node (ref "P5") (pin "21") (pinfunction "21_21") (pintype "passive"))
    )
    (net (code "202") (name "/5_AD2_IN1") (class "Default")
      (node (ref "IC5") (pin "40") (pinfunction "PA4_40") (pintype "passive"))
      (node (ref "P5") (pin "23") (pinfunction "23_23") (pintype "passive"))
    )
    (net (code "203") (name "/5_AD2_IN2") (class "Default")
      (node (ref "IC5") (pin "41") (pinfunction "PA5_41") (pintype "passive"))
      (node (ref "P5") (pin "25") (pinfunction "25_25") (pintype "passive"))
    )
    (net (code "204") (name "/5_AD2_IN3") (class "Default")
      (node (ref "IC5") (pin "42") (pinfunction "PA6_42") (pintype "passive"))
      (node (ref "P5") (pin "27") (pinfunction "27_27") (pintype "passive"))
    )
    (net (code "205") (name "/5_AD2_IN4") (class "Default")
      (node (ref "IC5") (pin "43") (pinfunction "PA7_43") (pintype "passive"))
      (node (ref "P5") (pin "29") (pinfunction "29_29") (pintype "passive"))
    )
    (net (code "206") (name "/5_AD2_IN5") (class "Default")
      (node (ref "IC5") (pin "44") (pinfunction "PC4_44") (pintype "passive"))
      (node (ref "P5") (pin "31") (pinfunction "31_31") (pintype "passive"))
    )
    (net (code "207") (name "/5_AD2_IN11") (class "Default")
      (node (ref "IC5") (pin "45") (pinfunction "PC5_45") (pintype "passive"))
      (node (ref "P5") (pin "33") (pinfunction "33_33") (pintype "passive"))
    )
    (net (code "208") (name "/5_AD2_IN12") (class "Default")
      (node (ref "IC5") (pin "48") (pinfunction "PB2_48") (pintype "passive"))
      (node (ref "P5") (pin "35") (pinfunction "35_35") (pintype "passive"))
    )
    (net (code "209") (name "/5_AD3_IN1") (class "Default")
      (node (ref "IC5") (pin "47") (pinfunction "PB1_47") (pintype "passive"))
      (node (ref "P5") (pin "37") (pinfunction "37_37") (pintype "passive"))
    )
    (net (code "210") (name "/5_AD3_IN2") (class "Default")
      (node (ref "IC5") (pin "60") (pinfunction "PE9_60") (pintype "passive"))
      (node (ref "P5") (pin "39") (pinfunction "39_39") (pintype "passive"))
    )
    (net (code "211") (name "/5_AD3_IN3") (class "Default")
      (node (ref "IC5") (pin "66") (pinfunction "PE13_66") (pintype "passive"))
      (node (ref "P5") (pin "2") (pinfunction "2_2") (pintype "passive"))
    )
    (net (code "212") (name "/5_AD3_IN5") (class "Default")
      (node (ref "IC5") (pin "74") (pinfunction "PB13_74") (pintype "passive"))
      (node (ref "P5") (pin "4") (pinfunction "4_4") (pintype "passive"))
    )
    (net (code "213") (name "/5_AD3_IN6") (class "Default")
      (node (ref "IC5") (pin "59") (pinfunction "PE8_59") (pintype "passive"))
      (node (ref "P5") (pin "6") (pinfunction "6_6") (pintype "passive"))
    )
    (net (code "214") (name "/5_AD3_IN7") (class "Default")
      (node (ref "IC5") (pin "79") (pinfunction "PD10_79") (pintype "passive"))
      (node (ref "P5") (pin "8") (pinfunction "8_8") (pintype "passive"))
    )
    (net (code "215") (name "/5_AD3_IN8") (class "Default")
      (node (ref "IC5") (pin "80") (pinfunction "PD11_80") (pintype "passive"))
      (node (ref "P5") (pin "10") (pinfunction "10_10") (pintype "passive"))
    )
    (net (code "216") (name "/5_AD3_IN9") (class "Default")
      (node (ref "IC5") (pin "81") (pinfunction "PD12_81") (pintype "passive"))
      (node (ref "P5") (pin "12") (pinfunction "12_12") (pintype "passive"))
    )
    (net (code "217") (name "/5_AD3_IN10") (class "Default")
      (node (ref "IC5") (pin "82") (pinfunction "PD13_82") (pintype "passive"))
      (node (ref "P5") (pin "14") (pinfunction "14_14") (pintype "passive"))
    )
    (net (code "218") (name "/5_AD3_IN11") (class "Default")
      (node (ref "IC5") (pin "85") (pinfunction "PD14_85") (pintype "passive"))
      (node (ref "P5") (pin "16") (pinfunction "16_16") (pintype "passive"))
    )
    (net (code "219") (name "/5_AD3_IN12") (class "Default")
      (node (ref "IC5") (pin "46") (pinfunction "PB0_46") (pintype "passive"))
      (node (ref "P5") (pin "18") (pinfunction "18_18") (pintype "passive"))
    )
    (net (code "220") (name "/5_AD3_IN13") (class "Default")
      (node (ref "IC5") (pin "58") (pinfunction "PE7_58") (pintype "passive"))
      (node (ref "P5") (pin "20") (pinfunction "20_20") (pintype "passive"))
    )
    (net (code "221") (name "/5_AD3_IN14") (class "Default")
      (node (ref "IC5") (pin "63") (pinfunction "PE10_63") (pintype "passive"))
      (node (ref "P5") (pin "22") (pinfunction "22_22") (pintype "passive"))
    )
    (net (code "222") (name "/5_AD3_IN15") (class "Default")
      (node (ref "IC5") (pin "64") (pinfunction "PE11_64") (pintype "passive"))
      (node (ref "P5") (pin "24") (pinfunction "24_24") (pintype "passive"))
    )
    (net (code "223") (name "/5_AD3_IN16") (class "Default")
      (node (ref "IC5") (pin "65") (pinfunction "PE12_65") (pintype "passive"))
      (node (ref "P5") (pin "26") (pinfunction "26_26") (pintype "passive"))
    )
    (net (code "224") (name "/5_AD4_IN1") (class "Default")
      (node (ref "IC5") (pin "67") (pinfunction "PE14_67") (pintype "passive"))
      (node (ref "P5") (pin "28") (pinfunction "28_28") (pintype "passive"))
    )
    (net (code "225") (name "/5_AD4_IN2") (class "Default")
      (node (ref "IC5") (pin "68") (pinfunction "PE15_68") (pintype "passive"))
      (node (ref "P5") (pin "30") (pinfunction "30_30") (pintype "passive"))
    )
    (net (code "226") (name "/5_AD4_IN3") (class "Default")
      (node (ref "IC5") (pin "73") (pinfunction "PB12_73") (pintype "passive"))
      (node (ref "P5") (pin "32") (pinfunction "32_32") (pintype "passive"))
    )
    (net (code "227") (name "/5_AD4_IN4") (class "Default")
      (node (ref "IC5") (pin "75") (pinfunction "PB14_75") (pintype "passive"))
      (node (ref "P5") (pin "34") (pinfunction "34_34") (pintype "passive"))
    )
    (net (code "228") (name "/5_AD4_IN5") (class "Default")
      (node (ref "IC5") (pin "76") (pinfunction "PB15_76") (pintype "passive"))
      (node (ref "P5") (pin "36") (pinfunction "36_36") (pintype "passive"))
    )
    (net (code "229") (name "/5_AD4_IN12") (class "Default")
      (node (ref "IC5") (pin "77") (pinfunction "PD8_77") (pintype "passive"))
      (node (ref "P5") (pin "38") (pinfunction "38_38") (pintype "passive"))
    )
    (net (code "230") (name "/5_AD4_IN13") (class "Default")
      (node (ref "IC5") (pin "78") (pinfunction "PD9_78") (pintype "passive"))
      (node (ref "P5") (pin "40") (pinfunction "40_40") (pintype "passive"))
    )
    (net (code "231") (name "/5_SPI_MISO") (class "Default")
      (node (ref "IC5") (pin "134") (pinfunction "PB4_134") (pintype "passive"))
      (node (ref "P6") (pin "14") (pinfunction "14_14") (pintype "passive"))
    )
    (net (code "232") (name "/5_SPI_MOSI") (class "Default")
      (node (ref "IC5") (pin "135") (pinfunction "PB5_135") (pintype "passive"))
      (node (ref "P6") (pin "15") (pinfunction "15_15") (pintype "passive"))
    )
    (net (code "233") (name "/5_SPI_SCK") (class "Default")
      (node (ref "IC5") (pin "133") (pinfunction "PB3_133") (pintype "passive"))
      (node (ref "P6") (pin "13") (pinfunction "13_13") (pintype "passive"))
    )
    (net (code "234") (name "3.3V") (class "Default")
      (node (ref "C11") (pin "1") (pinfunction "1_1") (pintype "passive"))
      (node (ref "C12") (pin "1") (pinfunction "1_1") (pintype "passive"))
      (node (ref "C13") (pin "1") (pinfunction "1_1") (pintype "passive"))
      (node (ref "C14") (pin "1") (pinfunction "1_1") (pintype "passive"))
      (node (ref "C15") (pin "1") (pinfunction "1_1") (pintype "passive"))
      (node (ref "C16") (pin "1") (pinfunction "1_1") (pintype "passive"))
      (node (ref "C17") (pin "1") (pinfunction "1_1") (pintype "passive"))
      (node (ref "C18") (pin "1") (pinfunction "1_1") (pintype "passive"))
      (node (ref "C19") (pin "1") (pinfunction "1_1") (pintype "passive"))
      (node (ref "C20") (pin "1") (pinfunction "1_1") (pintype "passive"))
      (node (ref "C21") (pin "1") (pinfunction "1_1") (pintype "passive"))
      (node (ref "C22") (pin "1") (pinfunction "1_1") (pintype "passive"))
      (node (ref "C23") (pin "1") (pinfunction "1_1") (pintype "passive"))
      (node (ref "C24") (pin "1") (pinfunction "1_1") (pintype "passive"))
      (node (ref "C25") (pin "1") (pinfunction "1_1") (pintype "passive"))
      (node (ref "C26") (pin "1") (pinfunction "1_1") (pintype "passive"))
      (node (ref "C27") (pin "1") (pinfunction "1_1") (pintype "passive"))
      (node (ref "C28") (pin "1") (pinfunction "1_1") (pintype "passive"))
      (node (ref "C29") (pin "1") (pinfunction "1_1") (pintype "passive"))
      (node (ref "C30") (pin "1") (pinfunction "1_1") (pintype "passive"))
      (node (ref "C31") (pin "1") (pinfunction "1_1") (pintype "passive"))
      (node (ref "C32") (pin "1") (pinfunction "1_1") (pintype "passive"))
      (node (ref "C33") (pin "1") (pinfunction "1_1") (pintype "passive"))
      (node (ref "C34") (pin "1") (pinfunction "1_1") (pintype "passive"))
      (node (ref "C35") (pin "1") (pinfunction "1_1") (pintype "passive"))
      (node (ref "C36") (pin "1") (pinfunction "1_1") (pintype "passive"))
      (node (ref "C37") (pin "1") (pinfunction "1_1") (pintype "passive"))
      (node (ref "C38") (pin "1") (pinfunction "1_1") (pintype "passive"))
      (node (ref "C39") (pin "1") (pinfunction "1_1") (pintype "passive"))
      (node (ref "C40") (pin "1") (pinfunction "1_1") (pintype "passive"))
      (node (ref "C41") (pin "1") (pinfunction "1_1") (pintype "passive"))
      (node (ref "C42") (pin "1") (pinfunction "1_1") (pintype "passive"))
      (node (ref "C43") (pin "1") (pinfunction "1_1") (pintype "passive"))
      (node (ref "C44") (pin "1") (pinfunction "1_1") (pintype "passive"))
      (node (ref "C45") (pin "1") (pinfunction "1_1") (pintype "passive"))
      (node (ref "C46") (pin "1") (pinfunction "1_1") (pintype "passive"))
      (node (ref "C47") (pin "1") (pinfunction "1_1") (pintype "passive"))
      (node (ref "C48") (pin "1") (pinfunction "1_1") (pintype "passive"))
      (node (ref "C49") (pin "1") (pinfunction "1_1") (pintype "passive"))
      (node (ref "C50") (pin "1") (pinfunction "1_1") (pintype "passive"))
      (node (ref "C51") (pin "1") (pinfunction "1_1") (pintype "passive"))
      (node (ref "C52") (pin "1") (pinfunction "1_1") (pintype "passive"))
      (node (ref "C53") (pin "1") (pinfunction "1_1") (pintype "passive"))
      (node (ref "C54") (pin "1") (pinfunction "1_1") (pintype "passive"))
      (node (ref "C55") (pin "1") (pinfunction "1_1") (pintype "passive"))
      (node (ref "C56") (pin "1") (pinfunction "1_1") (pintype "passive"))
      (node (ref "C57") (pin "1") (pinfunction "1_1") (pintype "passive"))
      (node (ref "C58") (pin "1") (pinfunction "1_1") (pintype "passive"))
      (node (ref "C59") (pin "1") (pinfunction "1_1") (pintype "passive"))
      (node (ref "C60") (pin "1") (pinfunction "1_1") (pintype "passive"))
      (node (ref "C61") (pin "1") (pinfunction "1_1") (pintype "passive"))
      (node (ref "C62") (pin "1") (pinfunction "1_1") (pintype "passive"))
      (node (ref "C63") (pin "1") (pinfunction "1_1") (pintype "passive"))
      (node (ref "C64") (pin "1") (pinfunction "1_1") (pintype "passive"))
      (node (ref "C65") (pin "1") (pinfunction "1_1") (pintype "passive"))
      (node (ref "C69") (pin "2") (pinfunction "2_2") (pintype "passive"))
      (node (ref "C70") (pin "2") (pinfunction "2_2") (pintype "passive"))
      (node (ref "IC1") (pin "108") (pinfunction "VDD_8_108") (pintype "passive"))
      (node (ref "IC1") (pin "121") (pinfunction "VDD_9_121") (pintype "passive"))
      (node (ref "IC1") (pin "131") (pinfunction "VDD_10_131") (pintype "passive"))
      (node (ref "IC1") (pin "144") (pinfunction "VDD_11_144") (pintype "passive"))
      (node (ref "IC1") (pin "17") (pinfunction "VDD_1_17") (pintype "passive"))
      (node (ref "IC1") (pin "32") (pinfunction "VREF+_32") (pintype "passive"))
      (node (ref "IC1") (pin "33") (pinfunction "VDDA_33") (pintype "passive"))
      (node (ref "IC1") (pin "39") (pinfunction "VDD_2_39") (pintype "passive"))
      (node (ref "IC1") (pin "52") (pinfunction "VDD_3_52") (pintype "passive"))
      (node (ref "IC1") (pin "62") (pinfunction "VDD_4_62") (pintype "passive"))
      (node (ref "IC1") (pin "72") (pinfunction "VDD_5_72") (pintype "passive"))
      (node (ref "IC1") (pin "84") (pinfunction "VDD_6_84") (pintype "passive"))
      (node (ref "IC1") (pin "95") (pinfunction "VDD_7_95") (pintype "passive"))
      (node (ref "IC2") (pin "108") (pinfunction "VDD_8_108") (pintype "passive"))
      (node (ref "IC2") (pin "121") (pinfunction "VDD_9_121") (pintype "passive"))
      (node (ref "IC2") (pin "131") (pinfunction "VDD_10_131") (pintype "passive"))
      (node (ref "IC2") (pin "144") (pinfunction "VDD_11_144") (pintype "passive"))
      (node (ref "IC2") (pin "17") (pinfunction "VDD_1_17") (pintype "passive"))
      (node (ref "IC2") (pin "32") (pinfunction "VREF+_32") (pintype "passive"))
      (node (ref "IC2") (pin "33") (pinfunction "VDDA_33") (pintype "passive"))
      (node (ref "IC2") (pin "39") (pinfunction "VDD_2_39") (pintype "passive"))
      (node (ref "IC2") (pin "52") (pinfunction "VDD_3_52") (pintype "passive"))
      (node (ref "IC2") (pin "62") (pinfunction "VDD_4_62") (pintype "passive"))
      (node (ref "IC2") (pin "72") (pinfunction "VDD_5_72") (pintype "passive"))
      (node (ref "IC2") (pin "84") (pinfunction "VDD_6_84") (pintype "passive"))
      (node (ref "IC2") (pin "95") (pinfunction "VDD_7_95") (pintype "passive"))
      (node (ref "IC3") (pin "108") (pinfunction "VDD_8_108") (pintype "passive"))
      (node (ref "IC3") (pin "121") (pinfunction "VDD_9_121") (pintype "passive"))
      (node (ref "IC3") (pin "131") (pinfunction "VDD_10_131") (pintype "passive"))
      (node (ref "IC3") (pin "144") (pinfunction "VDD_11_144") (pintype "passive"))
      (node (ref "IC3") (pin "17") (pinfunction "VDD_1_17") (pintype "passive"))
      (node (ref "IC3") (pin "32") (pinfunction "VREF+_32") (pintype "passive"))
      (node (ref "IC3") (pin "33") (pinfunction "VDDA_33") (pintype "passive"))
      (node (ref "IC3") (pin "39") (pinfunction "VDD_2_39") (pintype "passive"))
      (node (ref "IC3") (pin "52") (pinfunction "VDD_3_52") (pintype "passive"))
      (node (ref "IC3") (pin "62") (pinfunction "VDD_4_62") (pintype "passive"))
      (node (ref "IC3") (pin "72") (pinfunction "VDD_5_72") (pintype "passive"))
      (node (ref "IC3") (pin "84") (pinfunction "VDD_6_84") (pintype "passive"))
      (node (ref "IC3") (pin "95") (pinfunction "VDD_7_95") (pintype "passive"))
      (node (ref "IC4") (pin "108") (pinfunction "VDD_8_108") (pintype "passive"))
      (node (ref "IC4") (pin "121") (pinfunction "VDD_9_121") (pintype "passive"))
      (node (ref "IC4") (pin "131") (pinfunction "VDD_10_131") (pintype "passive"))
      (node (ref "IC4") (pin "144") (pinfunction "VDD_11_144") (pintype "passive"))
      (node (ref "IC4") (pin "17") (pinfunction "VDD_1_17") (pintype "passive"))
      (node (ref "IC4") (pin "32") (pinfunction "VREF+_32") (pintype "passive"))
      (node (ref "IC4") (pin "33") (pinfunction "VDDA_33") (pintype "passive"))
      (node (ref "IC4") (pin "39") (pinfunction "VDD_2_39") (pintype "passive"))
      (node (ref "IC4") (pin "52") (pinfunction "VDD_3_52") (pintype "passive"))
      (node (ref "IC4") (pin "62") (pinfunction "VDD_4_62") (pintype "passive"))
      (node (ref "IC4") (pin "72") (pinfunction "VDD_5_72") (pintype "passive"))
      (node (ref "IC4") (pin "84") (pinfunction "VDD_6_84") (pintype "passive"))
      (node (ref "IC4") (pin "95") (pinfunction "VDD_7_95") (pintype "passive"))
      (node (ref "IC5") (pin "108") (pinfunction "VDD_8_108") (pintype "passive"))
      (node (ref "IC5") (pin "121") (pinfunction "VDD_9_121") (pintype "passive"))
      (node (ref "IC5") (pin "131") (pinfunction "VDD_10_131") (pintype "passive"))
      (node (ref "IC5") (pin "144") (pinfunction "VDD_11_144") (pintype "passive"))
      (node (ref "IC5") (pin "17") (pinfunction "VDD_1_17") (pintype "passive"))
      (node (ref "IC5") (pin "32") (pinfunction "VREF+_32") (pintype "passive"))
      (node (ref "IC5") (pin "33") (pinfunction "VDDA_33") (pintype "passive"))
      (node (ref "IC5") (pin "39") (pinfunction "VDD_2_39") (pintype "passive"))
      (node (ref "IC5") (pin "52") (pinfunction "VDD_3_52") (pintype "passive"))
      (node (ref "IC5") (pin "62") (pinfunction "VDD_4_62") (pintype "passive"))
      (node (ref "IC5") (pin "72") (pinfunction "VDD_5_72") (pintype "passive"))
      (node (ref "IC5") (pin "84") (pinfunction "VDD_6_84") (pintype "passive"))
      (node (ref "IC5") (pin "95") (pinfunction "VDD_7_95") (pintype "passive"))
      (node (ref "P8") (pin "3") (pinfunction "3_3") (pintype "passive"))
      (node (ref "PS1") (pin "6") (pinfunction "+VOUT_6") (pintype "passive"))
      (node (ref "R2") (pin "2") (pinfunction "2_2") (pintype "passive"))
      (node (ref "R3") (pin "1") (pinfunction "1_1") (pintype "passive"))
    )
    (net (code "235") (name "GND") (class "Default")
      (node (ref "C1") (pin "2") (pinfunction "2_2") (pintype "passive"))
      (node (ref "C10") (pin "2") (pinfunction "2_2") (pintype "passive"))
      (node (ref "C11") (pin "2") (pinfunction "2_2") (pintype "passive"))
      (node (ref "C12") (pin "2") (pinfunction "2_2") (pintype "passive"))
      (node (ref "C13") (pin "2") (pinfunction "2_2") (pintype "passive"))
      (node (ref "C14") (pin "2") (pinfunction "2_2") (pintype "passive"))
      (node (ref "C15") (pin "2") (pinfunction "2_2") (pintype "passive"))
      (node (ref "C16") (pin "2") (pinfunction "2_2") (pintype "passive"))
      (node (ref "C17") (pin "2") (pinfunction "2_2") (pintype "passive"))
      (node (ref "C18") (pin "2") (pinfunction "2_2") (pintype "passive"))
      (node (ref "C19") (pin "2") (pinfunction "2_2") (pintype "passive"))
      (node (ref "C2") (pin "2") (pinfunction "2_2") (pintype "passive"))
      (node (ref "C20") (pin "2") (pinfunction "2_2") (pintype "passive"))
      (node (ref "C21") (pin "2") (pinfunction "2_2") (pintype "passive"))
      (node (ref "C22") (pin "2") (pinfunction "2_2") (pintype "passive"))
      (node (ref "C23") (pin "2") (pinfunction "2_2") (pintype "passive"))
      (node (ref "C24") (pin "2") (pinfunction "2_2") (pintype "passive"))
      (node (ref "C25") (pin "2") (pinfunction "2_2") (pintype "passive"))
      (node (ref "C26") (pin "2") (pinfunction "2_2") (pintype "passive"))
      (node (ref "C27") (pin "2") (pinfunction "2_2") (pintype "passive"))
      (node (ref "C28") (pin "2") (pinfunction "2_2") (pintype "passive"))
      (node (ref "C29") (pin "2") (pinfunction "2_2") (pintype "passive"))
      (node (ref "C3") (pin "2") (pinfunction "2_2") (pintype "passive"))
      (node (ref "C30") (pin "2") (pinfunction "2_2") (pintype "passive"))
      (node (ref "C31") (pin "2") (pinfunction "2_2") (pintype "passive"))
      (node (ref "C32") (pin "2") (pinfunction "2_2") (pintype "passive"))
      (node (ref "C33") (pin "2") (pinfunction "2_2") (pintype "passive"))
      (node (ref "C34") (pin "2") (pinfunction "2_2") (pintype "passive"))
      (node (ref "C35") (pin "2") (pinfunction "2_2") (pintype "passive"))
      (node (ref "C36") (pin "2") (pinfunction "2_2") (pintype "passive"))
      (node (ref "C37") (pin "2") (pinfunction "2_2") (pintype "passive"))
      (node (ref "C38") (pin "2") (pinfunction "2_2") (pintype "passive"))
      (node (ref "C39") (pin "2") (pinfunction "2_2") (pintype "passive"))
      (node (ref "C4") (pin "2") (pinfunction "2_2") (pintype "passive"))
      (node (ref "C40") (pin "2") (pinfunction "2_2") (pintype "passive"))
      (node (ref "C41") (pin "2") (pinfunction "2_2") (pintype "passive"))
      (node (ref "C42") (pin "2") (pinfunction "2_2") (pintype "passive"))
      (node (ref "C43") (pin "2") (pinfunction "2_2") (pintype "passive"))
      (node (ref "C44") (pin "2") (pinfunction "2_2") (pintype "passive"))
      (node (ref "C45") (pin "2") (pinfunction "2_2") (pintype "passive"))
      (node (ref "C46") (pin "2") (pinfunction "2_2") (pintype "passive"))
      (node (ref "C47") (pin "2") (pinfunction "2_2") (pintype "passive"))
      (node (ref "C48") (pin "2") (pinfunction "2_2") (pintype "passive"))
      (node (ref "C49") (pin "2") (pinfunction "2_2") (pintype "passive"))
      (node (ref "C5") (pin "2") (pinfunction "2_2") (pintype "passive"))
      (node (ref "C50") (pin "2") (pinfunction "2_2") (pintype "passive"))
      (node (ref "C51") (pin "2") (pinfunction "2_2") (pintype "passive"))
      (node (ref "C52") (pin "2") (pinfunction "2_2") (pintype "passive"))
      (node (ref "C53") (pin "2") (pinfunction "2_2") (pintype "passive"))
      (node (ref "C54") (pin "2") (pinfunction "2_2") (pintype "passive"))
      (node (ref "C55") (pin "2") (pinfunction "2_2") (pintype "passive"))
      (node (ref "C56") (pin "2") (pinfunction "2_2") (pintype "passive"))
      (node (ref "C57") (pin "2") (pinfunction "2_2") (pintype "passive"))
      (node (ref "C58") (pin "2") (pinfunction "2_2") (pintype "passive"))
      (node (ref "C59") (pin "2") (pinfunction "2_2") (pintype "passive"))
      (node (ref "C6") (pin "2") (pinfunction "2_2") (pintype "passive"))
      (node (ref "C60") (pin "2") (pinfunction "2_2") (pintype "passive"))
      (node (ref "C61") (pin "2") (pinfunction "2_2") (pintype "passive"))
      (node (ref "C62") (pin "2") (pinfunction "2_2") (pintype "passive"))
      (node (ref "C63") (pin "2") (pinfunction "2_2") (pintype "passive"))
      (node (ref "C64") (pin "2") (pinfunction "2_2") (pintype "passive"))
      (node (ref "C65") (pin "2") (pinfunction "2_2") (pintype "passive"))
      (node (ref "C66") (pin "2") (pinfunction "2_2") (pintype "passive"))
      (node (ref "C67") (pin "1") (pinfunction "1_1") (pintype "passive"))
      (node (ref "C68") (pin "1") (pinfunction "1_1") (pintype "passive"))
      (node (ref "C69") (pin "1") (pinfunction "1_1") (pintype "passive"))
      (node (ref "C7") (pin "2") (pinfunction "2_2") (pintype "passive"))
      (node (ref "C8") (pin "2") (pinfunction "2_2") (pintype "passive"))
      (node (ref "C9") (pin "2") (pinfunction "2_2") (pintype "passive"))
      (node (ref "IC1") (pin "107") (pinfunction "VSS_8_107") (pintype "passive"))
      (node (ref "IC1") (pin "120") (pinfunction "VSS_9_120") (pintype "passive"))
      (node (ref "IC1") (pin "130") (pinfunction "VSS_10_130") (pintype "passive"))
      (node (ref "IC1") (pin "143") (pinfunction "VSS_11_143") (pintype "passive"))
      (node (ref "IC1") (pin "16") (pinfunction "VSS_1_16") (pintype "passive"))
      (node (ref "IC1") (pin "30") (pinfunction "VSSA_30") (pintype "passive"))
      (node (ref "IC1") (pin "31") (pinfunction "VREF-_31") (pintype "passive"))
      (node (ref "IC1") (pin "38") (pinfunction "VSS_2_38") (pintype "passive"))
      (node (ref "IC1") (pin "51") (pinfunction "VSS_3_51") (pintype "passive"))
      (node (ref "IC1") (pin "61") (pinfunction "VSS_4_61") (pintype "passive"))
      (node (ref "IC1") (pin "71") (pinfunction "VSS_5_71") (pintype "passive"))
      (node (ref "IC1") (pin "83") (pinfunction "VSS_6_83") (pintype "passive"))
      (node (ref "IC1") (pin "94") (pinfunction "VSS_7_94") (pintype "passive"))
      (node (ref "IC2") (pin "107") (pinfunction "VSS_8_107") (pintype "passive"))
      (node (ref "IC2") (pin "120") (pinfunction "VSS_9_120") (pintype "passive"))
      (node (ref "IC2") (pin "130") (pinfunction "VSS_10_130") (pintype "passive"))
      (node (ref "IC2") (pin "143") (pinfunction "VSS_11_143") (pintype "passive"))
      (node (ref "IC2") (pin "16") (pinfunction "VSS_1_16") (pintype "passive"))
      (node (ref "IC2") (pin "30") (pinfunction "VSSA_30") (pintype "passive"))
      (node (ref "IC2") (pin "31") (pinfunction "VREF-_31") (pintype "passive"))
      (node (ref "IC2") (pin "38") (pinfunction "VSS_2_38") (pintype "passive"))
      (node (ref "IC2") (pin "51") (pinfunction "VSS_3_51") (pintype "passive"))
      (node (ref "IC2") (pin "61") (pinfunction "VSS_4_61") (pintype "passive"))
      (node (ref "IC2") (pin "71") (pinfunction "VSS_5_71") (pintype "passive"))
      (node (ref "IC2") (pin "83") (pinfunction "VSS_6_83") (pintype "passive"))
      (node (ref "IC2") (pin "94") (pinfunction "VSS_7_94") (pintype "passive"))
      (node (ref "IC3") (pin "107") (pinfunction "VSS_8_107") (pintype "passive"))
      (node (ref "IC3") (pin "120") (pinfunction "VSS_9_120") (pintype "passive"))
      (node (ref "IC3") (pin "130") (pinfunction "VSS_10_130") (pintype "passive"))
      (node (ref "IC3") (pin "143") (pinfunction "VSS_11_143") (pintype "passive"))
      (node (ref "IC3") (pin "16") (pinfunction "VSS_1_16") (pintype "passive"))
      (node (ref "IC3") (pin "30") (pinfunction "VSSA_30") (pintype "passive"))
      (node (ref "IC3") (pin "31") (pinfunction "VREF-_31") (pintype "passive"))
      (node (ref "IC3") (pin "38") (pinfunction "VSS_2_38") (pintype "passive"))
      (node (ref "IC3") (pin "51") (pinfunction "VSS_3_51") (pintype "passive"))
      (node (ref "IC3") (pin "61") (pinfunction "VSS_4_61") (pintype "passive"))
      (node (ref "IC3") (pin "71") (pinfunction "VSS_5_71") (pintype "passive"))
      (node (ref "IC3") (pin "83") (pinfunction "VSS_6_83") (pintype "passive"))
      (node (ref "IC3") (pin "94") (pinfunction "VSS_7_94") (pintype "passive"))
      (node (ref "IC4") (pin "107") (pinfunction "VSS_8_107") (pintype "passive"))
      (node (ref "IC4") (pin "120") (pinfunction "VSS_9_120") (pintype "passive"))
      (node (ref "IC4") (pin "130") (pinfunction "VSS_10_130") (pintype "passive"))
      (node (ref "IC4") (pin "143") (pinfunction "VSS_11_143") (pintype "passive"))
      (node (ref "IC4") (pin "16") (pinfunction "VSS_1_16") (pintype "passive"))
      (node (ref "IC4") (pin "30") (pinfunction "VSSA_30") (pintype "passive"))
      (node (ref "IC4") (pin "31") (pinfunction "VREF-_31") (pintype "passive"))
      (node (ref "IC4") (pin "38") (pinfunction "VSS_2_38") (pintype "passive"))
      (node (ref "IC4") (pin "51") (pinfunction "VSS_3_51") (pintype "passive"))
      (node (ref "IC4") (pin "61") (pinfunction "VSS_4_61") (pintype "passive"))
      (node (ref "IC4") (pin "71") (pinfunction "VSS_5_71") (pintype "passive"))
      (node (ref "IC4") (pin "83") (pinfunction "VSS_6_83") (pintype "passive"))
      (node (ref "IC4") (pin "94") (pinfunction "VSS_7_94") (pintype "passive"))
      (node (ref "IC5") (pin "107") (pinfunction "VSS_8_107") (pintype "passive"))
      (node (ref "IC5") (pin "120") (pinfunction "VSS_9_120") (pintype "passive"))
      (node (ref "IC5") (pin "130") (pinfunction "VSS_10_130") (pintype "passive"))
      (node (ref "IC5") (pin "143") (pinfunction "VSS_11_143") (pintype "passive"))
      (node (ref "IC5") (pin "16") (pinfunction "VSS_1_16") (pintype "passive"))
      (node (ref "IC5") (pin "30") (pinfunction "VSSA_30") (pintype "passive"))
      (node (ref "IC5") (pin "31") (pinfunction "VREF-_31") (pintype "passive"))
      (node (ref "IC5") (pin "38") (pinfunction "VSS_2_38") (pintype "passive"))
      (node (ref "IC5") (pin "51") (pinfunction "VSS_3_51") (pintype "passive"))
      (node (ref "IC5") (pin "61") (pinfunction "VSS_4_61") (pintype "passive"))
      (node (ref "IC5") (pin "71") (pinfunction "VSS_5_71") (pintype "passive"))
      (node (ref "IC5") (pin "83") (pinfunction "VSS_6_83") (pintype "passive"))
      (node (ref "IC5") (pin "94") (pinfunction "VSS_7_94") (pintype "passive"))
      (node (ref "L1") (pin "1") (pinfunction "1_1") (pintype "passive"))
      (node (ref "L1") (pin "2") (pinfunction "2_2") (pintype "passive"))
      (node (ref "M1") (pin "1") (pintype "passive"))
      (node (ref "M2") (pin "1") (pintype "passive"))
      (node (ref "M3") (pin "1") (pintype "passive"))
      (node (ref "M4") (pin "1") (pintype "passive"))
      (node (ref "P7") (pin "2") (pinfunction "2_2") (pintype "passive"))
      (node (ref "P8") (pin "4") (pinfunction "4_4") (pintype "passive"))
      (node (ref "PS1") (pin "1") (pinfunction "-VIN_(GND)_1") (pintype "passive"))
      (node (ref "R1") (pin "1") (pinfunction "1_1") (pintype "passive"))
      (node (ref "S1") (pin "1") (pinfunction "COM_1_1") (pintype "passive"))
      (node (ref "S1") (pin "2") (pinfunction "COM_2_2") (pintype "passive"))
    )
    (net (code "236") (name "Net-(IC1-PF0-OSC_IN)") (class "Default")
      (node (ref "C1") (pin "1") (pinfunction "1_1") (pintype "passive"))
      (node (ref "IC1") (pin "23") (pinfunction "PF0-OSC_IN_23") (pintype "passive"))
      (node (ref "Y1") (pin "1") (pinfunction "1_1") (pintype "passive"))
    )
    (net (code "237") (name "Net-(IC1-PF1-OSC_OUT)") (class "Default")
      (node (ref "C2") (pin "1") (pinfunction "1_1") (pintype "passive"))
      (node (ref "IC1") (pin "24") (pinfunction "PF1-OSC_OUT_24") (pintype "passive"))
      (node (ref "Y1") (pin "2") (pinfunction "2_2") (pintype "passive"))
    )
    (net (code "238") (name "Net-(IC2-PF0-OSC_IN)") (class "Default")
      (node (ref "C3") (pin "1") (pinfunction "1_1") (pintype "passive"))
      (node (ref "IC2") (pin "23") (pinfunction "PF0-OSC_IN_23") (pintype "passive"))
      (node (ref "Y2") (pin "1") (pinfunction "1_1") (pintype "passive"))
    )
    (net (code "239") (name "Net-(IC2-PF1-OSC_OUT)") (class "Default")
      (node (ref "C4") (pin "1") (pinfunction "1_1") (pintype "passive"))
      (node (ref "IC2") (pin "24") (pinfunction "PF1-OSC_OUT_24") (pintype "passive"))
      (node (ref "Y2") (pin "2") (pinfunction "2_2") (pintype "passive"))
    )
    (net (code "240") (name "Net-(IC3-PF0-OSC_IN)") (class "Default")
      (node (ref "C5") (pin "1") (pinfunction "1_1") (pintype "passive"))
      (node (ref "IC3") (pin "23") (pinfunction "PF0-OSC_IN_23") (pintype "passive"))
      (node (ref "Y3") (pin "1") (pinfunction "1_1") (pintype "passive"))
    )
    (net (code "241") (name "Net-(IC3-PF1-OSC_OUT)") (class "Default")
      (node (ref "C6") (pin "1") (pinfunction "1_1") (pintype "passive"))
      (node (ref "IC3") (pin "24") (pinfunction "PF1-OSC_OUT_24") (pintype "passive"))
      (node (ref "Y3") (pin "2") (pinfunction "2_2") (pintype "passive"))
    )
    (net (code "242") (name "Net-(IC4-PF0-OSC_IN)") (class "Default")
      (node (ref "C7") (pin "1") (pinfunction "1_1") (pintype "passive"))
      (node (ref "IC4") (pin "23") (pinfunction "PF0-OSC_IN_23") (pintype "passive"))
      (node (ref "Y4") (pin "1") (pinfunction "1_1") (pintype "passive"))
    )
    (net (code "243") (name "Net-(IC4-PF1-OSC_OUT)") (class "Default")
      (node (ref "C8") (pin "1") (pinfunction "1_1") (pintype "passive"))
      (node (ref "IC4") (pin "24") (pinfunction "PF1-OSC_OUT_24") (pintype "passive"))
      (node (ref "Y4") (pin "2") (pinfunction "2_2") (pintype "passive"))
    )
    (net (code "244") (name "Net-(IC5-PF0-OSC_IN)") (class "Default")
      (node (ref "C9") (pin "1") (pinfunction "1_1") (pintype "passive"))
      (node (ref "IC5") (pin "23") (pinfunction "PF0-OSC_IN_23") (pintype "passive"))
      (node (ref "Y5") (pin "1") (pinfunction "1_1") (pintype "passive"))
    )
    (net (code "245") (name "Net-(IC5-PF1-OSC_OUT)") (class "Default")
      (node (ref "C10") (pin "1") (pinfunction "1_1") (pintype "passive"))
      (node (ref "IC5") (pin "24") (pinfunction "PF1-OSC_OUT_24") (pintype "passive"))
      (node (ref "Y5") (pin "2") (pinfunction "2_2") (pintype "passive"))
    )
    (net (code "246") (name "Net-(PS1-+VIN_(VCC))") (class "Default")
      (node (ref "C68") (pin "2") (pinfunction "2_2") (pintype "passive"))
      (node (ref "C70") (pin "1") (pinfunction "1_1") (pintype "passive"))
      (node (ref "P7") (pin "1") (pinfunction "1_1") (pintype "passive"))
      (node (ref "PS1") (pin "2") (pinfunction "+VIN_(VCC)_2") (pintype "passive"))
    )
    (net (code "247") (name "Net-(PS1--VOUT)") (class "Default")
      (node (ref "C67") (pin "2") (pinfunction "2_2") (pintype "passive"))
      (node (ref "PS1") (pin "7") (pinfunction "-VOUT_7") (pintype "passive"))
    )
    (net (code "248") (name "unconnected-(IC1-PA8-Pad100)") (class "Default")
      (node (ref "IC1") (pin "100") (pinfunction "PA8_100") (pintype "passive"))
    )
    (net (code "249") (name "unconnected-(IC1-PA9-Pad101)") (class "Default")
      (node (ref "IC1") (pin "101") (pinfunction "PA9_101") (pintype "passive"))
    )
    (net (code "250") (name "unconnected-(IC1-PA10-Pad102)") (class "Default")
      (node (ref "IC1") (pin "102") (pinfunction "PA10_102") (pintype "passive"))
    )
    (net (code "251") (name "unconnected-(IC1-PA11-Pad103)") (class "Default")
      (node (ref "IC1") (pin "103") (pinfunction "PA11_103") (pintype "passive"))
    )
    (net (code "252") (name "unconnected-(IC1-PA12-Pad104)") (class "Default")
      (node (ref "IC1") (pin "104") (pinfunction "PA12_104") (pintype "passive"))
    )
    (net (code "253") (name "unconnected-(IC1-PA15-Pad110)") (class "Default")
      (node (ref "IC1") (pin "110") (pinfunction "PA15_110") (pintype "passive"))
    )
    (net (code "254") (name "unconnected-(IC1-PB6-Pad136)") (class "Default")
      (node (ref "IC1") (pin "136") (pinfunction "PB6_136") (pintype "passive"))
    )
    (net (code "255") (name "unconnected-(IC1-PB7-Pad137)") (class "Default")
      (node (ref "IC1") (pin "137") (pinfunction "PB7_137") (pintype "passive"))
    )
    (net (code "256") (name "unconnected-(IC1-PB8-Pad139)") (class "Default")
      (node (ref "IC1") (pin "139") (pinfunction "PB8_139") (pintype "passive"))
    )
    (net (code "257") (name "unconnected-(IC1-PB9-Pad140)") (class "Default")
      (node (ref "IC1") (pin "140") (pinfunction "PB9_140") (pintype "passive"))
    )
    (net (code "258") (name "unconnected-(IC1-PB10-Pad69)") (class "Default")
      (node (ref "IC1") (pin "69") (pinfunction "PB10_69") (pintype "passive"))
    )
    (net (code "259") (name "unconnected-(IC1-PC6-Pad96)") (class "Default")
      (node (ref "IC1") (pin "96") (pinfunction "PC6_96") (pintype "passive"))
    )
    (net (code "260") (name "unconnected-(IC1-PC7-Pad97)") (class "Default")
      (node (ref "IC1") (pin "97") (pinfunction "PC7_97") (pintype "passive"))
    )
    (net (code "261") (name "unconnected-(IC1-PC8-Pad98)") (class "Default")
      (node (ref "IC1") (pin "98") (pinfunction "PC8_98") (pintype "passive"))
    )
    (net (code "262") (name "unconnected-(IC1-PC9-Pad99)") (class "Default")
      (node (ref "IC1") (pin "99") (pinfunction "PC9_99") (pintype "passive"))
    )
    (net (code "263") (name "unconnected-(IC1-PC10-Pad111)") (class "Default")
      (node (ref "IC1") (pin "111") (pinfunction "PC10_111") (pintype "passive"))
    )
    (net (code "264") (name "unconnected-(IC1-PC11-Pad112)") (class "Default")
      (node (ref "IC1") (pin "112") (pinfunction "PC11_112") (pintype "passive"))
    )
    (net (code "265") (name "unconnected-(IC1-PC12-Pad113)") (class "Default")
      (node (ref "IC1") (pin "113") (pinfunction "PC12_113") (pintype "passive"))
    )
    (net (code "266") (name "unconnected-(IC1-PC13-Pad7)") (class "Default")
      (node (ref "IC1") (pin "7") (pinfunction "PC13_7") (pintype "passive"))
    )
    (net (code "267") (name "unconnected-(IC1-PC14-Pad8)") (class "Default")
      (node (ref "IC1") (pin "8") (pinfunction "PC14_8") (pintype "passive"))
    )
    (net (code "268") (name "unconnected-(IC1-PC15-Pad9)") (class "Default")
      (node (ref "IC1") (pin "9") (pinfunction "PC15_9") (pintype "passive"))
    )
    (net (code "269") (name "unconnected-(IC1-PD0-Pad114)") (class "Default")
      (node (ref "IC1") (pin "114") (pinfunction "PD0_114") (pintype "passive"))
    )
    (net (code "270") (name "unconnected-(IC1-PD1-Pad115)") (class "Default")
      (node (ref "IC1") (pin "115") (pinfunction "PD1_115") (pintype "passive"))
    )
    (net (code "271") (name "unconnected-(IC1-PD2-Pad116)") (class "Default")
      (node (ref "IC1") (pin "116") (pinfunction "PD2_116") (pintype "passive"))
    )
    (net (code "272") (name "unconnected-(IC1-PD3-Pad117)") (class "Default")
      (node (ref "IC1") (pin "117") (pinfunction "PD3_117") (pintype "passive"))
    )
    (net (code "273") (name "unconnected-(IC1-PD4-Pad118)") (class "Default")
      (node (ref "IC1") (pin "118") (pinfunction "PD4_118") (pintype "passive"))
    )
    (net (code "274") (name "unconnected-(IC1-PD5-Pad119)") (class "Default")
      (node (ref "IC1") (pin "119") (pinfunction "PD5_119") (pintype "passive"))
    )
    (net (code "275") (name "unconnected-(IC1-PD6-Pad122)") (class "Default")
      (node (ref "IC1") (pin "122") (pinfunction "PD6_122") (pintype "passive"))
    )
    (net (code "276") (name "unconnected-(IC1-PD7-Pad123)") (class "Default")
      (node (ref "IC1") (pin "123") (pinfunction "PD7_123") (pintype "passive"))
    )
    (net (code "277") (name "unconnected-(IC1-PD15-Pad86)") (class "Default")
      (node (ref "IC1") (pin "86") (pinfunction "PD15_86") (pintype "passive"))
    )
    (net (code "278") (name "unconnected-(IC1-PE0-Pad141)") (class "Default")
      (node (ref "IC1") (pin "141") (pinfunction "PE0_141") (pintype "passive"))
    )
    (net (code "279") (name "unconnected-(IC1-PE1-Pad142)") (class "Default")
      (node (ref "IC1") (pin "142") (pinfunction "PE1_142") (pintype "passive"))
    )
    (net (code "280") (name "unconnected-(IC1-PE2-Pad1)") (class "Default")
      (node (ref "IC1") (pin "1") (pinfunction "PE2_1") (pintype "passive"))
    )
    (net (code "281") (name "unconnected-(IC1-PE3-Pad2)") (class "Default")
      (node (ref "IC1") (pin "2") (pinfunction "PE3_2") (pintype "passive"))
    )
    (net (code "282") (name "unconnected-(IC1-PE4-Pad3)") (class "Default")
      (node (ref "IC1") (pin "3") (pinfunction "PE4_3") (pintype "passive"))
    )
    (net (code "283") (name "unconnected-(IC1-PE5-Pad4)") (class "Default")
      (node (ref "IC1") (pin "4") (pinfunction "PE5_4") (pintype "passive"))
    )
    (net (code "284") (name "unconnected-(IC1-PE6-Pad5)") (class "Default")
      (node (ref "IC1") (pin "5") (pinfunction "PE6_5") (pintype "passive"))
    )
    (net (code "285") (name "unconnected-(IC1-PF3-Pad13)") (class "Default")
      (node (ref "IC1") (pin "13") (pinfunction "PF3_13") (pintype "passive"))
    )
    (net (code "286") (name "unconnected-(IC1-PF5-Pad15)") (class "Default")
      (node (ref "IC1") (pin "15") (pinfunction "PF5_15") (pintype "passive"))
    )
    (net (code "287") (name "unconnected-(IC1-PF6-Pad18)") (class "Default")
      (node (ref "IC1") (pin "18") (pinfunction "PF6_18") (pintype "passive"))
    )
    (net (code "288") (name "unconnected-(IC1-PF7-Pad19)") (class "Default")
      (node (ref "IC1") (pin "19") (pinfunction "PF7_19") (pintype "passive"))
    )
    (net (code "289") (name "unconnected-(IC1-PF8-Pad20)") (class "Default")
      (node (ref "IC1") (pin "20") (pinfunction "PF8_20") (pintype "passive"))
    )
    (net (code "290") (name "unconnected-(IC1-PF9-Pad21)") (class "Default")
      (node (ref "IC1") (pin "21") (pinfunction "PF9_21") (pintype "passive"))
    )
    (net (code "291") (name "unconnected-(IC1-PF10-Pad22)") (class "Default")
      (node (ref "IC1") (pin "22") (pinfunction "PF10_22") (pintype "passive"))
    )
    (net (code "292") (name "unconnected-(IC1-PF11-Pad49)") (class "Default")
      (node (ref "IC1") (pin "49") (pinfunction "PF11_49") (pintype "passive"))
    )
    (net (code "293") (name "unconnected-(IC1-PF12-Pad50)") (class "Default")
      (node (ref "IC1") (pin "50") (pinfunction "PF12_50") (pintype "passive"))
    )
    (net (code "294") (name "unconnected-(IC1-PF13-Pad53)") (class "Default")
      (node (ref "IC1") (pin "53") (pinfunction "PF13_53") (pintype "passive"))
    )
    (net (code "295") (name "unconnected-(IC1-PF14-Pad54)") (class "Default")
      (node (ref "IC1") (pin "54") (pinfunction "PF14_54") (pintype "passive"))
    )
    (net (code "296") (name "unconnected-(IC1-PF15-Pad55)") (class "Default")
      (node (ref "IC1") (pin "55") (pinfunction "PF15_55") (pintype "passive"))
    )
    (net (code "297") (name "unconnected-(IC1-PG0-Pad56)") (class "Default")
      (node (ref "IC1") (pin "56") (pinfunction "PG0_56") (pintype "passive"))
    )
    (net (code "298") (name "unconnected-(IC1-PG1-Pad57)") (class "Default")
      (node (ref "IC1") (pin "57") (pinfunction "PG1_57") (pintype "passive"))
    )
    (net (code "299") (name "unconnected-(IC1-PG2-Pad87)") (class "Default")
      (node (ref "IC1") (pin "87") (pinfunction "PG2_87") (pintype "passive"))
    )
    (net (code "300") (name "unconnected-(IC1-PG3-Pad88)") (class "Default")
      (node (ref "IC1") (pin "88") (pinfunction "PG3_88") (pintype "passive"))
    )
    (net (code "301") (name "unconnected-(IC1-PG4-Pad89)") (class "Default")
      (node (ref "IC1") (pin "89") (pinfunction "PG4_89") (pintype "passive"))
    )
    (net (code "302") (name "unconnected-(IC1-PG5-Pad90)") (class "Default")
      (node (ref "IC1") (pin "90") (pinfunction "PG5_90") (pintype "passive"))
    )
    (net (code "303") (name "unconnected-(IC1-PG6-Pad91)") (class "Default")
      (node (ref "IC1") (pin "91") (pinfunction "PG6_91") (pintype "passive"))
    )
    (net (code "304") (name "unconnected-(IC1-PG7-Pad92)") (class "Default")
      (node (ref "IC1") (pin "92") (pinfunction "PG7_92") (pintype "passive"))
    )
    (net (code "305") (name "unconnected-(IC1-PG8-Pad93)") (class "Default")
      (node (ref "IC1") (pin "93") (pinfunction "PG8_93") (pintype "passive"))
    )
    (net (code "306") (name "unconnected-(IC1-PG9-Pad124)") (class "Default")
      (node (ref "IC1") (pin "124") (pinfunction "PG9_124") (pintype "passive"))
    )
    (net (code "307") (name "unconnected-(IC1-PG10-Pad125)") (class "Default")
      (node (ref "IC1") (pin "125") (pinfunction "PG10_125") (pintype "passive"))
    )
    (net (code "308") (name "unconnected-(IC1-PG11-Pad126)") (class "Default")
      (node (ref "IC1") (pin "126") (pinfunction "PG11_126") (pintype "passive"))
    )
    (net (code "309") (name "unconnected-(IC1-PG12-Pad127)") (class "Default")
      (node (ref "IC1") (pin "127") (pinfunction "PG12_127") (pintype "passive"))
    )
    (net (code "310") (name "unconnected-(IC1-PG13-Pad128)") (class "Default")
      (node (ref "IC1") (pin "128") (pinfunction "PG13_128") (pintype "passive"))
    )
    (net (code "311") (name "unconnected-(IC1-PG14-Pad129)") (class "Default")
      (node (ref "IC1") (pin "129") (pinfunction "PG14_129") (pintype "passive"))
    )
    (net (code "312") (name "unconnected-(IC1-PG15-Pad132)") (class "Default")
      (node (ref "IC1") (pin "132") (pinfunction "PG15_132") (pintype "passive"))
    )
    (net (code "313") (name "unconnected-(IC1-PH0-Pad10)") (class "Default")
      (node (ref "IC1") (pin "10") (pinfunction "PH0_10") (pintype "passive"))
    )
    (net (code "314") (name "unconnected-(IC1-PH1-Pad11)") (class "Default")
      (node (ref "IC1") (pin "11") (pinfunction "PH1_11") (pintype "passive"))
    )
    (net (code "315") (name "unconnected-(IC1-PH2-Pad106)") (class "Default")
      (node (ref "IC1") (pin "106") (pinfunction "PH2_106") (pintype "passive"))
    )
    (net (code "316") (name "unconnected-(IC1-VBAT-Pad6)") (class "Default")
      (node (ref "IC1") (pin "6") (pinfunction "VBAT_6") (pintype "passive"))
    )
    (net (code "317") (name "unconnected-(IC2-PA8-Pad100)") (class "Default")
      (node (ref "IC2") (pin "100") (pinfunction "PA8_100") (pintype "passive"))
    )
    (net (code "318") (name "unconnected-(IC2-PA9-Pad101)") (class "Default")
      (node (ref "IC2") (pin "101") (pinfunction "PA9_101") (pintype "passive"))
    )
    (net (code "319") (name "unconnected-(IC2-PA10-Pad102)") (class "Default")
      (node (ref "IC2") (pin "102") (pinfunction "PA10_102") (pintype "passive"))
    )
    (net (code "320") (name "unconnected-(IC2-PA11-Pad103)") (class "Default")
      (node (ref "IC2") (pin "103") (pinfunction "PA11_103") (pintype "passive"))
    )
    (net (code "321") (name "unconnected-(IC2-PA12-Pad104)") (class "Default")
      (node (ref "IC2") (pin "104") (pinfunction "PA12_104") (pintype "passive"))
    )
    (net (code "322") (name "unconnected-(IC2-PA15-Pad110)") (class "Default")
      (node (ref "IC2") (pin "110") (pinfunction "PA15_110") (pintype "passive"))
    )
    (net (code "323") (name "unconnected-(IC2-PB6-Pad136)") (class "Default")
      (node (ref "IC2") (pin "136") (pinfunction "PB6_136") (pintype "passive"))
    )
    (net (code "324") (name "unconnected-(IC2-PB7-Pad137)") (class "Default")
      (node (ref "IC2") (pin "137") (pinfunction "PB7_137") (pintype "passive"))
    )
    (net (code "325") (name "unconnected-(IC2-PB8-Pad139)") (class "Default")
      (node (ref "IC2") (pin "139") (pinfunction "PB8_139") (pintype "passive"))
    )
    (net (code "326") (name "unconnected-(IC2-PB9-Pad140)") (class "Default")
      (node (ref "IC2") (pin "140") (pinfunction "PB9_140") (pintype "passive"))
    )
    (net (code "327") (name "unconnected-(IC2-PB10-Pad69)") (class "Default")
      (node (ref "IC2") (pin "69") (pinfunction "PB10_69") (pintype "passive"))
    )
    (net (code "328") (name "unconnected-(IC2-PC6-Pad96)") (class "Default")
      (node (ref "IC2") (pin "96") (pinfunction "PC6_96") (pintype "passive"))
    )
    (net (code "329") (name "unconnected-(IC2-PC7-Pad97)") (class "Default")
      (node (ref "IC2") (pin "97") (pinfunction "PC7_97") (pintype "passive"))
    )
    (net (code "330") (name "unconnected-(IC2-PC8-Pad98)") (class "Default")
      (node (ref "IC2") (pin "98") (pinfunction "PC8_98") (pintype "passive"))
    )
    (net (code "331") (name "unconnected-(IC2-PC9-Pad99)") (class "Default")
      (node (ref "IC2") (pin "99") (pinfunction "PC9_99") (pintype "passive"))
    )
    (net (code "332") (name "unconnected-(IC2-PC10-Pad111)") (class "Default")
      (node (ref "IC2") (pin "111") (pinfunction "PC10_111") (pintype "passive"))
    )
    (net (code "333") (name "unconnected-(IC2-PC11-Pad112)") (class "Default")
      (node (ref "IC2") (pin "112") (pinfunction "PC11_112") (pintype "passive"))
    )
    (net (code "334") (name "unconnected-(IC2-PC12-Pad113)") (class "Default")
      (node (ref "IC2") (pin "113") (pinfunction "PC12_113") (pintype "passive"))
    )
    (net (code "335") (name "unconnected-(IC2-PC13-Pad7)") (class "Default")
      (node (ref "IC2") (pin "7") (pinfunction "PC13_7") (pintype "passive"))
    )
    (net (code "336") (name "unconnected-(IC2-PC14-Pad8)") (class "Default")
      (node (ref "IC2") (pin "8") (pinfunction "PC14_8") (pintype "passive"))
    )
    (net (code "337") (name "unconnected-(IC2-PC15-Pad9)") (class "Default")
      (node (ref "IC2") (pin "9") (pinfunction "PC15_9") (pintype "passive"))
    )
    (net (code "338") (name "unconnected-(IC2-PD0-Pad114)") (class "Default")
      (node (ref "IC2") (pin "114") (pinfunction "PD0_114") (pintype "passive"))
    )
    (net (code "339") (name "unconnected-(IC2-PD1-Pad115)") (class "Default")
      (node (ref "IC2") (pin "115") (pinfunction "PD1_115") (pintype "passive"))
    )
    (net (code "340") (name "unconnected-(IC2-PD2-Pad116)") (class "Default")
      (node (ref "IC2") (pin "116") (pinfunction "PD2_116") (pintype "passive"))
    )
    (net (code "341") (name "unconnected-(IC2-PD3-Pad117)") (class "Default")
      (node (ref "IC2") (pin "117") (pinfunction "PD3_117") (pintype "passive"))
    )
    (net (code "342") (name "unconnected-(IC2-PD4-Pad118)") (class "Default")
      (node (ref "IC2") (pin "118") (pinfunction "PD4_118") (pintype "passive"))
    )
    (net (code "343") (name "unconnected-(IC2-PD5-Pad119)") (class "Default")
      (node (ref "IC2") (pin "119") (pinfunction "PD5_119") (pintype "passive"))
    )
    (net (code "344") (name "unconnected-(IC2-PD6-Pad122)") (class "Default")
      (node (ref "IC2") (pin "122") (pinfunction "PD6_122") (pintype "passive"))
    )
    (net (code "345") (name "unconnected-(IC2-PD7-Pad123)") (class "Default")
      (node (ref "IC2") (pin "123") (pinfunction "PD7_123") (pintype "passive"))
    )
    (net (code "346") (name "unconnected-(IC2-PD15-Pad86)") (class "Default")
      (node (ref "IC2") (pin "86") (pinfunction "PD15_86") (pintype "passive"))
    )
    (net (code "347") (name "unconnected-(IC2-PE0-Pad141)") (class "Default")
      (node (ref "IC2") (pin "141") (pinfunction "PE0_141") (pintype "passive"))
    )
    (net (code "348") (name "unconnected-(IC2-PE1-Pad142)") (class "Default")
      (node (ref "IC2") (pin "142") (pinfunction "PE1_142") (pintype "passive"))
    )
    (net (code "349") (name "unconnected-(IC2-PE2-Pad1)") (class "Default")
      (node (ref "IC2") (pin "1") (pinfunction "PE2_1") (pintype "passive"))
    )
    (net (code "350") (name "unconnected-(IC2-PE3-Pad2)") (class "Default")
      (node (ref "IC2") (pin "2") (pinfunction "PE3_2") (pintype "passive"))
    )
    (net (code "351") (name "unconnected-(IC2-PE4-Pad3)") (class "Default")
      (node (ref "IC2") (pin "3") (pinfunction "PE4_3") (pintype "passive"))
    )
    (net (code "352") (name "unconnected-(IC2-PE5-Pad4)") (class "Default")
      (node (ref "IC2") (pin "4") (pinfunction "PE5_4") (pintype "passive"))
    )
    (net (code "353") (name "unconnected-(IC2-PE6-Pad5)") (class "Default")
      (node (ref "IC2") (pin "5") (pinfunction "PE6_5") (pintype "passive"))
    )
    (net (code "354") (name "unconnected-(IC2-PF3-Pad13)") (class "Default")
      (node (ref "IC2") (pin "13") (pinfunction "PF3_13") (pintype "passive"))
    )
    (net (code "355") (name "unconnected-(IC2-PF5-Pad15)") (class "Default")
      (node (ref "IC2") (pin "15") (pinfunction "PF5_15") (pintype "passive"))
    )
    (net (code "356") (name "unconnected-(IC2-PF6-Pad18)") (class "Default")
      (node (ref "IC2") (pin "18") (pinfunction "PF6_18") (pintype "passive"))
    )
    (net (code "357") (name "unconnected-(IC2-PF7-Pad19)") (class "Default")
      (node (ref "IC2") (pin "19") (pinfunction "PF7_19") (pintype "passive"))
    )
    (net (code "358") (name "unconnected-(IC2-PF8-Pad20)") (class "Default")
      (node (ref "IC2") (pin "20") (pinfunction "PF8_20") (pintype "passive"))
    )
    (net (code "359") (name "unconnected-(IC2-PF9-Pad21)") (class "Default")
      (node (ref "IC2") (pin "21") (pinfunction "PF9_21") (pintype "passive"))
    )
    (net (code "360") (name "unconnected-(IC2-PF10-Pad22)") (class "Default")
      (node (ref "IC2") (pin "22") (pinfunction "PF10_22") (pintype "passive"))
    )
    (net (code "361") (name "unconnected-(IC2-PF11-Pad49)") (class "Default")
      (node (ref "IC2") (pin "49") (pinfunction "PF11_49") (pintype "passive"))
    )
    (net (code "362") (name "unconnected-(IC2-PF12-Pad50)") (class "Default")
      (node (ref "IC2") (pin "50") (pinfunction "PF12_50") (pintype "passive"))
    )
    (net (code "363") (name "unconnected-(IC2-PF13-Pad53)") (class "Default")
      (node (ref "IC2") (pin "53") (pinfunction "PF13_53") (pintype "passive"))
    )
    (net (code "364") (name "unconnected-(IC2-PF14-Pad54)") (class "Default")
      (node (ref "IC2") (pin "54") (pinfunction "PF14_54") (pintype "passive"))
    )
    (net (code "365") (name "unconnected-(IC2-PF15-Pad55)") (class "Default")
      (node (ref "IC2") (pin "55") (pinfunction "PF15_55") (pintype "passive"))
    )
    (net (code "366") (name "unconnected-(IC2-PG0-Pad56)") (class "Default")
      (node (ref "IC2") (pin "56") (pinfunction "PG0_56") (pintype "passive"))
    )
    (net (code "367") (name "unconnected-(IC2-PG1-Pad57)") (class "Default")
      (node (ref "IC2") (pin "57") (pinfunction "PG1_57") (pintype "passive"))
    )
    (net (code "368") (name "unconnected-(IC2-PG2-Pad87)") (class "Default")
      (node (ref "IC2") (pin "87") (pinfunction "PG2_87") (pintype "passive"))
    )
    (net (code "369") (name "unconnected-(IC2-PG3-Pad88)") (class "Default")
      (node (ref "IC2") (pin "88") (pinfunction "PG3_88") (pintype "passive"))
    )
    (net (code "370") (name "unconnected-(IC2-PG4-Pad89)") (class "Default")
      (node (ref "IC2") (pin "89") (pinfunction "PG4_89") (pintype "passive"))
    )
    (net (code "371") (name "unconnected-(IC2-PG5-Pad90)") (class "Default")
      (node (ref "IC2") (pin "90") (pinfunction "PG5_90") (pintype "passive"))
    )
    (net (code "372") (name "unconnected-(IC2-PG6-Pad91)") (class "Default")
      (node (ref "IC2") (pin "91") (pinfunction "PG6_91") (pintype "passive"))
    )
    (net (code "373") (name "unconnected-(IC2-PG7-Pad92)") (class "Default")
      (node (ref "IC2") (pin "92") (pinfunction "PG7_92") (pintype "passive"))
    )
    (net (code "374") (name "unconnected-(IC2-PG8-Pad93)") (class "Default")
      (node (ref "IC2") (pin "93") (pinfunction "PG8_93") (pintype "passive"))
    )
    (net (code "375") (name "unconnected-(IC2-PG9-Pad124)") (class "Default")
      (node (ref "IC2") (pin "124") (pinfunction "PG9_124") (pintype "passive"))
    )
    (net (code "376") (name "unconnected-(IC2-PG10-Pad125)") (class "Default")
      (node (ref "IC2") (pin "125") (pinfunction "PG10_125") (pintype "passive"))
    )
    (net (code "377") (name "unconnected-(IC2-PG11-Pad126)") (class "Default")
      (node (ref "IC2") (pin "126") (pinfunction "PG11_126") (pintype "passive"))
    )
    (net (code "378") (name "unconnected-(IC2-PG12-Pad127)") (class "Default")
      (node (ref "IC2") (pin "127") (pinfunction "PG12_127") (pintype "passive"))
    )
    (net (code "379") (name "unconnected-(IC2-PG13-Pad128)") (class "Default")
      (node (ref "IC2") (pin "128") (pinfunction "PG13_128") (pintype "passive"))
    )
    (net (code "380") (name "unconnected-(IC2-PG14-Pad129)") (class "Default")
      (node (ref "IC2") (pin "129") (pinfunction "PG14_129") (pintype "passive"))
    )
    (net (code "381") (name "unconnected-(IC2-PG15-Pad132)") (class "Default")
      (node (ref "IC2") (pin "132") (pinfunction "PG15_132") (pintype "passive"))
    )
    (net (code "382") (name "unconnected-(IC2-PH0-Pad10)") (class "Default")
      (node (ref "IC2") (pin "10") (pinfunction "PH0_10") (pintype "passive"))
    )
    (net (code "383") (name "unconnected-(IC2-PH1-Pad11)") (class "Default")
      (node (ref "IC2") (pin "11") (pinfunction "PH1_11") (pintype "passive"))
    )
    (net (code "384") (name "unconnected-(IC2-PH2-Pad106)") (class "Default")
      (node (ref "IC2") (pin "106") (pinfunction "PH2_106") (pintype "passive"))
    )
    (net (code "385") (name "unconnected-(IC2-VBAT-Pad6)") (class "Default")
      (node (ref "IC2") (pin "6") (pinfunction "VBAT_6") (pintype "passive"))
    )
    (net (code "386") (name "unconnected-(IC3-PA8-Pad100)") (class "Default")
      (node (ref "IC3") (pin "100") (pinfunction "PA8_100") (pintype "passive"))
    )
    (net (code "387") (name "unconnected-(IC3-PA9-Pad101)") (class "Default")
      (node (ref "IC3") (pin "101") (pinfunction "PA9_101") (pintype "passive"))
    )
    (net (code "388") (name "unconnected-(IC3-PA10-Pad102)") (class "Default")
      (node (ref "IC3") (pin "102") (pinfunction "PA10_102") (pintype "passive"))
    )
    (net (code "389") (name "unconnected-(IC3-PA11-Pad103)") (class "Default")
      (node (ref "IC3") (pin "103") (pinfunction "PA11_103") (pintype "passive"))
    )
    (net (code "390") (name "unconnected-(IC3-PA12-Pad104)") (class "Default")
      (node (ref "IC3") (pin "104") (pinfunction "PA12_104") (pintype "passive"))
    )
    (net (code "391") (name "unconnected-(IC3-PA15-Pad110)") (class "Default")
      (node (ref "IC3") (pin "110") (pinfunction "PA15_110") (pintype "passive"))
    )
    (net (code "392") (name "unconnected-(IC3-PB6-Pad136)") (class "Default")
      (node (ref "IC3") (pin "136") (pinfunction "PB6_136") (pintype "passive"))
    )
    (net (code "393") (name "unconnected-(IC3-PB7-Pad137)") (class "Default")
      (node (ref "IC3") (pin "137") (pinfunction "PB7_137") (pintype "passive"))
    )
    (net (code "394") (name "unconnected-(IC3-PB8-Pad139)") (class "Default")
      (node (ref "IC3") (pin "139") (pinfunction "PB8_139") (pintype "passive"))
    )
    (net (code "395") (name "unconnected-(IC3-PB9-Pad140)") (class "Default")
      (node (ref "IC3") (pin "140") (pinfunction "PB9_140") (pintype "passive"))
    )
    (net (code "396") (name "unconnected-(IC3-PB10-Pad69)") (class "Default")
      (node (ref "IC3") (pin "69") (pinfunction "PB10_69") (pintype "passive"))
    )
    (net (code "397") (name "unconnected-(IC3-PC6-Pad96)") (class "Default")
      (node (ref "IC3") (pin "96") (pinfunction "PC6_96") (pintype "passive"))
    )
    (net (code "398") (name "unconnected-(IC3-PC7-Pad97)") (class "Default")
      (node (ref "IC3") (pin "97") (pinfunction "PC7_97") (pintype "passive"))
    )
    (net (code "399") (name "unconnected-(IC3-PC8-Pad98)") (class "Default")
      (node (ref "IC3") (pin "98") (pinfunction "PC8_98") (pintype "passive"))
    )
    (net (code "400") (name "unconnected-(IC3-PC9-Pad99)") (class "Default")
      (node (ref "IC3") (pin "99") (pinfunction "PC9_99") (pintype "passive"))
    )
    (net (code "401") (name "unconnected-(IC3-PC10-Pad111)") (class "Default")
      (node (ref "IC3") (pin "111") (pinfunction "PC10_111") (pintype "passive"))
    )
    (net (code "402") (name "unconnected-(IC3-PC11-Pad112)") (class "Default")
      (node (ref "IC3") (pin "112") (pinfunction "PC11_112") (pintype "passive"))
    )
    (net (code "403") (name "unconnected-(IC3-PC12-Pad113)") (class "Default")
      (node (ref "IC3") (pin "113") (pinfunction "PC12_113") (pintype "passive"))
    )
    (net (code "404") (name "unconnected-(IC3-PC13-Pad7)") (class "Default")
      (node (ref "IC3") (pin "7") (pinfunction "PC13_7") (pintype "passive"))
    )
    (net (code "405") (name "unconnected-(IC3-PC14-Pad8)") (class "Default")
      (node (ref "IC3") (pin "8") (pinfunction "PC14_8") (pintype "passive"))
    )
    (net (code "406") (name "unconnected-(IC3-PC15-Pad9)") (class "Default")
      (node (ref "IC3") (pin "9") (pinfunction "PC15_9") (pintype "passive"))
    )
    (net (code "407") (name "unconnected-(IC3-PD0-Pad114)") (class "Default")
      (node (ref "IC3") (pin "114") (pinfunction "PD0_114") (pintype "passive"))
    )
    (net (code "408") (name "unconnected-(IC3-PD1-Pad115)") (class "Default")
      (node (ref "IC3") (pin "115") (pinfunction "PD1_115") (pintype "passive"))
    )
    (net (code "409") (name "unconnected-(IC3-PD2-Pad116)") (class "Default")
      (node (ref "IC3") (pin "116") (pinfunction "PD2_116") (pintype "passive"))
    )
    (net (code "410") (name "unconnected-(IC3-PD3-Pad117)") (class "Default")
      (node (ref "IC3") (pin "117") (pinfunction "PD3_117") (pintype "passive"))
    )
    (net (code "411") (name "unconnected-(IC3-PD4-Pad118)") (class "Default")
      (node (ref "IC3") (pin "118") (pinfunction "PD4_118") (pintype "passive"))
    )
    (net (code "412") (name "unconnected-(IC3-PD5-Pad119)") (class "Default")
      (node (ref "IC3") (pin "119") (pinfunction "PD5_119") (pintype "passive"))
    )
    (net (code "413") (name "unconnected-(IC3-PD6-Pad122)") (class "Default")
      (node (ref "IC3") (pin "122") (pinfunction "PD6_122") (pintype "passive"))
    )
    (net (code "414") (name "unconnected-(IC3-PD7-Pad123)") (class "Default")
      (node (ref "IC3") (pin "123") (pinfunction "PD7_123") (pintype "passive"))
    )
    (net (code "415") (name "unconnected-(IC3-PD15-Pad86)") (class "Default")
      (node (ref "IC3") (pin "86") (pinfunction "PD15_86") (pintype "passive"))
    )
    (net (code "416") (name "unconnected-(IC3-PE0-Pad141)") (class "Default")
      (node (ref "IC3") (pin "141") (pinfunction "PE0_141") (pintype "passive"))
    )
    (net (code "417") (name "unconnected-(IC3-PE1-Pad142)") (class "Default")
      (node (ref "IC3") (pin "142") (pinfunction "PE1_142") (pintype "passive"))
    )
    (net (code "418") (name "unconnected-(IC3-PE2-Pad1)") (class "Default")
      (node (ref "IC3") (pin "1") (pinfunction "PE2_1") (pintype "passive"))
    )
    (net (code "419") (name "unconnected-(IC3-PE3-Pad2)") (class "Default")
      (node (ref "IC3") (pin "2") (pinfunction "PE3_2") (pintype "passive"))
    )
    (net (code "420") (name "unconnected-(IC3-PE4-Pad3)") (class "Default")
      (node (ref "IC3") (pin "3") (pinfunction "PE4_3") (pintype "passive"))
    )
    (net (code "421") (name "unconnected-(IC3-PE5-Pad4)") (class "Default")
      (node (ref "IC3") (pin "4") (pinfunction "PE5_4") (pintype "passive"))
    )
    (net (code "422") (name "unconnected-(IC3-PE6-Pad5)") (class "Default")
      (node (ref "IC3") (pin "5") (pinfunction "PE6_5") (pintype "passive"))
    )
    (net (code "423") (name "unconnected-(IC3-PF3-Pad13)") (class "Default")
      (node (ref "IC3") (pin "13") (pinfunction "PF3_13") (pintype "passive"))
    )
    (net (code "424") (name "unconnected-(IC3-PF5-Pad15)") (class "Default")
      (node (ref "IC3") (pin "15") (pinfunction "PF5_15") (pintype "passive"))
    )
    (net (code "425") (name "unconnected-(IC3-PF6-Pad18)") (class "Default")
      (node (ref "IC3") (pin "18") (pinfunction "PF6_18") (pintype "passive"))
    )
    (net (code "426") (name "unconnected-(IC3-PF7-Pad19)") (class "Default")
      (node (ref "IC3") (pin "19") (pinfunction "PF7_19") (pintype "passive"))
    )
    (net (code "427") (name "unconnected-(IC3-PF8-Pad20)") (class "Default")
      (node (ref "IC3") (pin "20") (pinfunction "PF8_20") (pintype "passive"))
    )
    (net (code "428") (name "unconnected-(IC3-PF9-Pad21)") (class "Default")
      (node (ref "IC3") (pin "21") (pinfunction "PF9_21") (pintype "passive"))
    )
    (net (code "429") (name "unconnected-(IC3-PF10-Pad22)") (class "Default")
      (node (ref "IC3") (pin "22") (pinfunction "PF10_22") (pintype "passive"))
    )
    (net (code "430") (name "unconnected-(IC3-PF11-Pad49)") (class "Default")
      (node (ref "IC3") (pin "49") (pinfunction "PF11_49") (pintype "passive"))
    )
    (net (code "431") (name "unconnected-(IC3-PF12-Pad50)") (class "Default")
      (node (ref "IC3") (pin "50") (pinfunction "PF12_50") (pintype "passive"))
    )
    (net (code "432") (name "unconnected-(IC3-PF13-Pad53)") (class "Default")
      (node (ref "IC3") (pin "53") (pinfunction "PF13_53") (pintype "passive"))
    )
    (net (code "433") (name "unconnected-(IC3-PF14-Pad54)") (class "Default")
      (node (ref "IC3") (pin "54") (pinfunction "PF14_54") (pintype "passive"))
    )
    (net (code "434") (name "unconnected-(IC3-PF15-Pad55)") (class "Default")
      (node (ref "IC3") (pin "55") (pinfunction "PF15_55") (pintype "passive"))
    )
    (net (code "435") (name "unconnected-(IC3-PG0-Pad56)") (class "Default")
      (node (ref "IC3") (pin "56") (pinfunction "PG0_56") (pintype "passive"))
    )
    (net (code "436") (name "unconnected-(IC3-PG1-Pad57)") (class "Default")
      (node (ref "IC3") (pin "57") (pinfunction "PG1_57") (pintype "passive"))
    )
    (net (code "437") (name "unconnected-(IC3-PG2-Pad87)") (class "Default")
      (node (ref "IC3") (pin "87") (pinfunction "PG2_87") (pintype "passive"))
    )
    (net (code "438") (name "unconnected-(IC3-PG3-Pad88)") (class "Default")
      (node (ref "IC3") (pin "88") (pinfunction "PG3_88") (pintype "passive"))
    )
    (net (code "439") (name "unconnected-(IC3-PG4-Pad89)") (class "Default")
      (node (ref "IC3") (pin "89") (pinfunction "PG4_89") (pintype "passive"))
    )
    (net (code "440") (name "unconnected-(IC3-PG5-Pad90)") (class "Default")
      (node (ref "IC3") (pin "90") (pinfunction "PG5_90") (pintype "passive"))
    )
    (net (code "441") (name "unconnected-(IC3-PG6-Pad91)") (class "Default")
      (node (ref "IC3") (pin "91") (pinfunction "PG6_91") (pintype "passive"))
    )
    (net (code "442") (name "unconnected-(IC3-PG7-Pad92)") (class "Default")
      (node (ref "IC3") (pin "92") (pinfunction "PG7_92") (pintype "passive"))
    )
    (net (code "443") (name "unconnected-(IC3-PG8-Pad93)") (class "Default")
      (node (ref "IC3") (pin "93") (pinfunction "PG8_93") (pintype "passive"))
    )
    (net (code "444") (name "unconnected-(IC3-PG9-Pad124)") (class "Default")
      (node (ref "IC3") (pin "124") (pinfunction "PG9_124") (pintype "passive"))
    )
    (net (code "445") (name "unconnected-(IC3-PG10-Pad125)") (class "Default")
      (node (ref "IC3") (pin "125") (pinfunction "PG10_125") (pintype "passive"))
    )
    (net (code "446") (name "unconnected-(IC3-PG11-Pad126)") (class "Default")
      (node (ref "IC3") (pin "126") (pinfunction "PG11_126") (pintype "passive"))
    )
    (net (code "447") (name "unconnected-(IC3-PG12-Pad127)") (class "Default")
      (node (ref "IC3") (pin "127") (pinfunction "PG12_127") (pintype "passive"))
    )
    (net (code "448") (name "unconnected-(IC3-PG13-Pad128)") (class "Default")
      (node (ref "IC3") (pin "128") (pinfunction "PG13_128") (pintype "passive"))
    )
    (net (code "449") (name "unconnected-(IC3-PG14-Pad129)") (class "Default")
      (node (ref "IC3") (pin "129") (pinfunction "PG14_129") (pintype "passive"))
    )
    (net (code "450") (name "unconnected-(IC3-PG15-Pad132)") (class "Default")
      (node (ref "IC3") (pin "132") (pinfunction "PG15_132") (pintype "passive"))
    )
    (net (code "451") (name "unconnected-(IC3-PH0-Pad10)") (class "Default")
      (node (ref "IC3") (pin "10") (pinfunction "PH0_10") (pintype "passive"))
    )
    (net (code "452") (name "unconnected-(IC3-PH1-Pad11)") (class "Default")
      (node (ref "IC3") (pin "11") (pinfunction "PH1_11") (pintype "passive"))
    )
    (net (code "453") (name "unconnected-(IC3-PH2-Pad106)") (class "Default")
      (node (ref "IC3") (pin "106") (pinfunction "PH2_106") (pintype "passive"))
    )
    (net (code "454") (name "unconnected-(IC3-VBAT-Pad6)") (class "Default")
      (node (ref "IC3") (pin "6") (pinfunction "VBAT_6") (pintype "passive"))
    )
    (net (code "455") (name "unconnected-(IC4-PA8-Pad100)") (class "Default")
      (node (ref "IC4") (pin "100") (pinfunction "PA8_100") (pintype "passive"))
    )
    (net (code "456") (name "unconnected-(IC4-PA9-Pad101)") (class "Default")
      (node (ref "IC4") (pin "101") (pinfunction "PA9_101") (pintype "passive"))
    )
    (net (code "457") (name "unconnected-(IC4-PA10-Pad102)") (class "Default")
      (node (ref "IC4") (pin "102") (pinfunction "PA10_102") (pintype "passive"))
    )
    (net (code "458") (name "unconnected-(IC4-PA11-Pad103)") (class "Default")
      (node (ref "IC4") (pin "103") (pinfunction "PA11_103") (pintype "passive"))
    )
    (net (code "459") (name "unconnected-(IC4-PA12-Pad104)") (class "Default")
      (node (ref "IC4") (pin "104") (pinfunction "PA12_104") (pintype "passive"))
    )
    (net (code "460") (name "unconnected-(IC4-PA15-Pad110)") (class "Default")
      (node (ref "IC4") (pin "110") (pinfunction "PA15_110") (pintype "passive"))
    )
    (net (code "461") (name "unconnected-(IC4-PB6-Pad136)") (class "Default")
      (node (ref "IC4") (pin "136") (pinfunction "PB6_136") (pintype "passive"))
    )
    (net (code "462") (name "unconnected-(IC4-PB7-Pad137)") (class "Default")
      (node (ref "IC4") (pin "137") (pinfunction "PB7_137") (pintype "passive"))
    )
    (net (code "463") (name "unconnected-(IC4-PB8-Pad139)") (class "Default")
      (node (ref "IC4") (pin "139") (pinfunction "PB8_139") (pintype "passive"))
    )
    (net (code "464") (name "unconnected-(IC4-PB9-Pad140)") (class "Default")
      (node (ref "IC4") (pin "140") (pinfunction "PB9_140") (pintype "passive"))
    )
    (net (code "465") (name "unconnected-(IC4-PB10-Pad69)") (class "Default")
      (node (ref "IC4") (pin "69") (pinfunction "PB10_69") (pintype "passive"))
    )
    (net (code "466") (name "unconnected-(IC4-PC6-Pad96)") (class "Default")
      (node (ref "IC4") (pin "96") (pinfunction "PC6_96") (pintype "passive"))
    )
    (net (code "467") (name "unconnected-(IC4-PC7-Pad97)") (class "Default")
      (node (ref "IC4") (pin "97") (pinfunction "PC7_97") (pintype "passive"))
    )
    (net (code "468") (name "unconnected-(IC4-PC8-Pad98)") (class "Default")
      (node (ref "IC4") (pin "98") (pinfunction "PC8_98") (pintype "passive"))
    )
    (net (code "469") (name "unconnected-(IC4-PC9-Pad99)") (class "Default")
      (node (ref "IC4") (pin "99") (pinfunction "PC9_99") (pintype "passive"))
    )
    (net (code "470") (name "unconnected-(IC4-PC10-Pad111)") (class "Default")
      (node (ref "IC4") (pin "111") (pinfunction "PC10_111") (pintype "passive"))
    )
    (net (code "471") (name "unconnected-(IC4-PC11-Pad112)") (class "Default")
      (node (ref "IC4") (pin "112") (pinfunction "PC11_112") (pintype "passive"))
    )
    (net (code "472") (name "unconnected-(IC4-PC12-Pad113)") (class "Default")
      (node (ref "IC4") (pin "113") (pinfunction "PC12_113") (pintype "passive"))
    )
    (net (code "473") (name "unconnected-(IC4-PC13-Pad7)") (class "Default")
      (node (ref "IC4") (pin "7") (pinfunction "PC13_7") (pintype "passive"))
    )
    (net (code "474") (name "unconnected-(IC4-PC14-Pad8)") (class "Default")
      (node (ref "IC4") (pin "8") (pinfunction "PC14_8") (pintype "passive"))
    )
    (net (code "475") (name "unconnected-(IC4-PC15-Pad9)") (class "Default")
      (node (ref "IC4") (pin "9") (pinfunction "PC15_9") (pintype "passive"))
    )
    (net (code "476") (name "unconnected-(IC4-PD0-Pad114)") (class "Default")
      (node (ref "IC4") (pin "114") (pinfunction "PD0_114") (pintype "passive"))
    )
    (net (code "477") (name "unconnected-(IC4-PD1-Pad115)") (class "Default")
      (node (ref "IC4") (pin "115") (pinfunction "PD1_115") (pintype "passive"))
    )
    (net (code "478") (name "unconnected-(IC4-PD2-Pad116)") (class "Default")
      (node (ref "IC4") (pin "116") (pinfunction "PD2_116") (pintype "passive"))
    )
    (net (code "479") (name "unconnected-(IC4-PD3-Pad117)") (class "Default")
      (node (ref "IC4") (pin "117") (pinfunction "PD3_117") (pintype "passive"))
    )
    (net (code "480") (name "unconnected-(IC4-PD4-Pad118)") (class "Default")
      (node (ref "IC4") (pin "118") (pinfunction "PD4_118") (pintype "passive"))
    )
    (net (code "481") (name "unconnected-(IC4-PD5-Pad119)") (class "Default")
      (node (ref "IC4") (pin "119") (pinfunction "PD5_119") (pintype "passive"))
    )
    (net (code "482") (name "unconnected-(IC4-PD6-Pad122)") (class "Default")
      (node (ref "IC4") (pin "122") (pinfunction "PD6_122") (pintype "passive"))
    )
    (net (code "483") (name "unconnected-(IC4-PD7-Pad123)") (class "Default")
      (node (ref "IC4") (pin "123") (pinfunction "PD7_123") (pintype "passive"))
    )
    (net (code "484") (name "unconnected-(IC4-PD15-Pad86)") (class "Default")
      (node (ref "IC4") (pin "86") (pinfunction "PD15_86") (pintype "passive"))
    )
    (net (code "485") (name "unconnected-(IC4-PE0-Pad141)") (class "Default")
      (node (ref "IC4") (pin "141") (pinfunction "PE0_141") (pintype "passive"))
    )
    (net (code "486") (name "unconnected-(IC4-PE1-Pad142)") (class "Default")
      (node (ref "IC4") (pin "142") (pinfunction "PE1_142") (pintype "passive"))
    )
    (net (code "487") (name "unconnected-(IC4-PE2-Pad1)") (class "Default")
      (node (ref "IC4") (pin "1") (pinfunction "PE2_1") (pintype "passive"))
    )
    (net (code "488") (name "unconnected-(IC4-PE3-Pad2)") (class "Default")
      (node (ref "IC4") (pin "2") (pinfunction "PE3_2") (pintype "passive"))
    )
    (net (code "489") (name "unconnected-(IC4-PE4-Pad3)") (class "Default")
      (node (ref "IC4") (pin "3") (pinfunction "PE4_3") (pintype "passive"))
    )
    (net (code "490") (name "unconnected-(IC4-PE5-Pad4)") (class "Default")
      (node (ref "IC4") (pin "4") (pinfunction "PE5_4") (pintype "passive"))
    )
    (net (code "491") (name "unconnected-(IC4-PE6-Pad5)") (class "Default")
      (node (ref "IC4") (pin "5") (pinfunction "PE6_5") (pintype "passive"))
    )
    (net (code "492") (name "unconnected-(IC4-PF3-Pad13)") (class "Default")
      (node (ref "IC4") (pin "13") (pinfunction "PF3_13") (pintype "passive"))
    )
    (net (code "493") (name "unconnected-(IC4-PF5-Pad15)") (class "Default")
      (node (ref "IC4") (pin "15") (pinfunction "PF5_15") (pintype "passive"))
    )
    (net (code "494") (name "unconnected-(IC4-PF6-Pad18)") (class "Default")
      (node (ref "IC4") (pin "18") (pinfunction "PF6_18") (pintype "passive"))
    )
    (net (code "495") (name "unconnected-(IC4-PF7-Pad19)") (class "Default")
      (node (ref "IC4") (pin "19") (pinfunction "PF7_19") (pintype "passive"))
    )
    (net (code "496") (name "unconnected-(IC4-PF8-Pad20)") (class "Default")
      (node (ref "IC4") (pin "20") (pinfunction "PF8_20") (pintype "passive"))
    )
    (net (code "497") (name "unconnected-(IC4-PF9-Pad21)") (class "Default")
      (node (ref "IC4") (pin "21") (pinfunction "PF9_21") (pintype "passive"))
    )
    (net (code "498") (name "unconnected-(IC4-PF10-Pad22)") (class "Default")
      (node (ref "IC4") (pin "22") (pinfunction "PF10_22") (pintype "passive"))
    )
    (net (code "499") (name "unconnected-(IC4-PF11-Pad49)") (class "Default")
      (node (ref "IC4") (pin "49") (pinfunction "PF11_49") (pintype "passive"))
    )
    (net (code "500") (name "unconnected-(IC4-PF12-Pad50)") (class "Default")
      (node (ref "IC4") (pin "50") (pinfunction "PF12_50") (pintype "passive"))
    )
    (net (code "501") (name "unconnected-(IC4-PF13-Pad53)") (class "Default")
      (node (ref "IC4") (pin "53") (pinfunction "PF13_53") (pintype "passive"))
    )
    (net (code "502") (name "unconnected-(IC4-PF14-Pad54)") (class "Default")
      (node (ref "IC4") (pin "54") (pinfunction "PF14_54") (pintype "passive"))
    )
    (net (code "503") (name "unconnected-(IC4-PF15-Pad55)") (class "Default")
      (node (ref "IC4") (pin "55") (pinfunction "PF15_55") (pintype "passive"))
    )
    (net (code "504") (name "unconnected-(IC4-PG0-Pad56)") (class "Default")
      (node (ref "IC4") (pin "56") (pinfunction "PG0_56") (pintype "passive"))
    )
    (net (code "505") (name "unconnected-(IC4-PG1-Pad57)") (class "Default")
      (node (ref "IC4") (pin "57") (pinfunction "PG1_57") (pintype "passive"))
    )
    (net (code "506") (name "unconnected-(IC4-PG2-Pad87)") (class "Default")
      (node (ref "IC4") (pin "87") (pinfunction "PG2_87") (pintype "passive"))
    )
    (net (code "507") (name "unconnected-(IC4-PG3-Pad88)") (class "Default")
      (node (ref "IC4") (pin "88") (pinfunction "PG3_88") (pintype "passive"))
    )
    (net (code "508") (name "unconnected-(IC4-PG4-Pad89)") (class "Default")
      (node (ref "IC4") (pin "89") (pinfunction "PG4_89") (pintype "passive"))
    )
    (net (code "509") (name "unconnected-(IC4-PG5-Pad90)") (class "Default")
      (node (ref "IC4") (pin "90") (pinfunction "PG5_90") (pintype "passive"))
    )
    (net (code "510") (name "unconnected-(IC4-PG6-Pad91)") (class "Default")
      (node (ref "IC4") (pin "91") (pinfunction "PG6_91") (pintype "passive"))
    )
    (net (code "511") (name "unconnected-(IC4-PG7-Pad92)") (class "Default")
      (node (ref "IC4") (pin "92") (pinfunction "PG7_92") (pintype "passive"))
    )
    (net (code "512") (name "unconnected-(IC4-PG8-Pad93)") (class "Default")
      (node (ref "IC4") (pin "93") (pinfunction "PG8_93") (pintype "passive"))
    )
    (net (code "513") (name "unconnected-(IC4-PG9-Pad124)") (class "Default")
      (node (ref "IC4") (pin "124") (pinfunction "PG9_124") (pintype "passive"))
    )
    (net (code "514") (name "unconnected-(IC4-PG10-Pad125)") (class "Default")
      (node (ref "IC4") (pin "125") (pinfunction "PG10_125") (pintype "passive"))
    )
    (net (code "515") (name "unconnected-(IC4-PG11-Pad126)") (class "Default")
      (node (ref "IC4") (pin "126") (pinfunction "PG11_126") (pintype "passive"))
    )
    (net (code "516") (name "unconnected-(IC4-PG12-Pad127)") (class "Default")
      (node (ref "IC4") (pin "127") (pinfunction "PG12_127") (pintype "passive"))
    )
    (net (code "517") (name "unconnected-(IC4-PG13-Pad128)") (class "Default")
      (node (ref "IC4") (pin "128") (pinfunction "PG13_128") (pintype "passive"))
    )
    (net (code "518") (name "unconnected-(IC4-PG14-Pad129)") (class "Default")
      (node (ref "IC4") (pin "129") (pinfunction "PG14_129") (pintype "passive"))
    )
    (net (code "519") (name "unconnected-(IC4-PG15-Pad132)") (class "Default")
      (node (ref "IC4") (pin "132") (pinfunction "PG15_132") (pintype "passive"))
    )
    (net (code "520") (name "unconnected-(IC4-PH0-Pad10)") (class "Default")
      (node (ref "IC4") (pin "10") (pinfunction "PH0_10") (pintype "passive"))
    )
    (net (code "521") (name "unconnected-(IC4-PH1-Pad11)") (class "Default")
      (node (ref "IC4") (pin "11") (pinfunction "PH1_11") (pintype "passive"))
    )
    (net (code "522") (name "unconnected-(IC4-PH2-Pad106)") (class "Default")
      (node (ref "IC4") (pin "106") (pinfunction "PH2_106") (pintype "passive"))
    )
    (net (code "523") (name "unconnected-(IC4-VBAT-Pad6)") (class "Default")
      (node (ref "IC4") (pin "6") (pinfunction "VBAT_6") (pintype "passive"))
    )
    (net (code "524") (name "unconnected-(IC5-PA8-Pad100)") (class "Default")
      (node (ref "IC5") (pin "100") (pinfunction "PA8_100") (pintype "passive"))
    )
    (net (code "525") (name "unconnected-(IC5-PA9-Pad101)") (class "Default")
      (node (ref "IC5") (pin "101") (pinfunction "PA9_101") (pintype "passive"))
    )
    (net (code "526") (name "unconnected-(IC5-PA10-Pad102)") (class "Default")
      (node (ref "IC5") (pin "102") (pinfunction "PA10_102") (pintype "passive"))
    )
    (net (code "527") (name "unconnected-(IC5-PA11-Pad103)") (class "Default")
      (node (ref "IC5") (pin "103") (pinfunction "PA11_103") (pintype "passive"))
    )
    (net (code "528") (name "unconnected-(IC5-PA12-Pad104)") (class "Default")
      (node (ref "IC5") (pin "104") (pinfunction "PA12_104") (pintype "passive"))
    )
    (net (code "529") (name "unconnected-(IC5-PA15-Pad110)") (class "Default")
      (node (ref "IC5") (pin "110") (pinfunction "PA15_110") (pintype "passive"))
    )
    (net (code "530") (name "unconnected-(IC5-PB6-Pad136)") (class "Default")
      (node (ref "IC5") (pin "136") (pinfunction "PB6_136") (pintype "passive"))
    )
    (net (code "531") (name "unconnected-(IC5-PB7-Pad137)") (class "Default")
      (node (ref "IC5") (pin "137") (pinfunction "PB7_137") (pintype "passive"))
    )
    (net (code "532") (name "unconnected-(IC5-PB8-Pad139)") (class "Default")
      (node (ref "IC5") (pin "139") (pinfunction "PB8_139") (pintype "passive"))
    )
    (net (code "533") (name "unconnected-(IC5-PB9-Pad140)") (class "Default")
      (node (ref "IC5") (pin "140") (pinfunction "PB9_140") (pintype "passive"))
    )
    (net (code "534") (name "unconnected-(IC5-PB10-Pad69)") (class "Default")
      (node (ref "IC5") (pin "69") (pinfunction "PB10_69") (pintype "passive"))
    )
    (net (code "535") (name "unconnected-(IC5-PC6-Pad96)") (class "Default")
      (node (ref "IC5") (pin "96") (pinfunction "PC6_96") (pintype "passive"))
    )
    (net (code "536") (name "unconnected-(IC5-PC7-Pad97)") (class "Default")
      (node (ref "IC5") (pin "97") (pinfunction "PC7_97") (pintype "passive"))
    )
    (net (code "537") (name "unconnected-(IC5-PC8-Pad98)") (class "Default")
      (node (ref "IC5") (pin "98") (pinfunction "PC8_98") (pintype "passive"))
    )
    (net (code "538") (name "unconnected-(IC5-PC9-Pad99)") (class "Default")
      (node (ref "IC5") (pin "99") (pinfunction "PC9_99") (pintype "passive"))
    )
    (net (code "539") (name "unconnected-(IC5-PC10-Pad111)") (class "Default")
      (node (ref "IC5") (pin "111") (pinfunction "PC10_111") (pintype "passive"))
    )
    (net (code "540") (name "unconnected-(IC5-PC11-Pad112)") (class "Default")
      (node (ref "IC5") (pin "112") (pinfunction "PC11_112") (pintype "passive"))
    )
    (net (code "541") (name "unconnected-(IC5-PC12-Pad113)") (class "Default")
      (node (ref "IC5") (pin "113") (pinfunction "PC12_113") (pintype "passive"))
    )
    (net (code "542") (name "unconnected-(IC5-PC13-Pad7)") (class "Default")
      (node (ref "IC5") (pin "7") (pinfunction "PC13_7") (pintype "passive"))
    )
    (net (code "543") (name "unconnected-(IC5-PC14-Pad8)") (class "Default")
      (node (ref "IC5") (pin "8") (pinfunction "PC14_8") (pintype "passive"))
    )
    (net (code "544") (name "unconnected-(IC5-PC15-Pad9)") (class "Default")
      (node (ref "IC5") (pin "9") (pinfunction "PC15_9") (pintype "passive"))
    )
    (net (code "545") (name "unconnected-(IC5-PD0-Pad114)") (class "Default")
      (node (ref "IC5") (pin "114") (pinfunction "PD0_114") (pintype "passive"))
    )
    (net (code "546") (name "unconnected-(IC5-PD1-Pad115)") (class "Default")
      (node (ref "IC5") (pin "115") (pinfunction "PD1_115") (pintype "passive"))
    )
    (net (code "547") (name "unconnected-(IC5-PD2-Pad116)") (class "Default")
      (node (ref "IC5") (pin "116") (pinfunction "PD2_116") (pintype "passive"))
    )
    (net (code "548") (name "unconnected-(IC5-PD3-Pad117)") (class "Default")
      (node (ref "IC5") (pin "117") (pinfunction "PD3_117") (pintype "passive"))
    )
    (net (code "549") (name "unconnected-(IC5-PD4-Pad118)") (class "Default")
      (node (ref "IC5") (pin "118") (pinfunction "PD4_118") (pintype "passive"))
    )
    (net (code "550") (name "unconnected-(IC5-PD5-Pad119)") (class "Default")
      (node (ref "IC5") (pin "119") (pinfunction "PD5_119") (pintype "passive"))
    )
    (net (code "551") (name "unconnected-(IC5-PD6-Pad122)") (class "Default")
      (node (ref "IC5") (pin "122") (pinfunction "PD6_122") (pintype "passive"))
    )
    (net (code "552") (name "unconnected-(IC5-PD7-Pad123)") (class "Default")
      (node (ref "IC5") (pin "123") (pinfunction "PD7_123") (pintype "passive"))
    )
    (net (code "553") (name "unconnected-(IC5-PD15-Pad86)") (class "Default")
      (node (ref "IC5") (pin "86") (pinfunction "PD15_86") (pintype "passive"))
    )
    (net (code "554") (name "unconnected-(IC5-PE0-Pad141)") (class "Default")
      (node (ref "IC5") (pin "141") (pinfunction "PE0_141") (pintype "passive"))
    )
    (net (code "555") (name "unconnected-(IC5-PE1-Pad142)") (class "Default")
      (node (ref "IC5") (pin "142") (pinfunction "PE1_142") (pintype "passive"))
    )
    (net (code "556") (name "unconnected-(IC5-PE2-Pad1)") (class "Default")
      (node (ref "IC5") (pin "1") (pinfunction "PE2_1") (pintype "passive"))
    )
    (net (code "557") (name "unconnected-(IC5-PE3-Pad2)") (class "Default")
      (node (ref "IC5") (pin "2") (pinfunction "PE3_2") (pintype "passive"))
    )
    (net (code "558") (name "unconnected-(IC5-PE4-Pad3)") (class "Default")
      (node (ref "IC5") (pin "3") (pinfunction "PE4_3") (pintype "passive"))
    )
    (net (code "559") (name "unconnected-(IC5-PE5-Pad4)") (class "Default")
      (node (ref "IC5") (pin "4") (pinfunction "PE5_4") (pintype "passive"))
    )
    (net (code "560") (name "unconnected-(IC5-PE6-Pad5)") (class "Default")
      (node (ref "IC5") (pin "5") (pinfunction "PE6_5") (pintype "passive"))
    )
    (net (code "561") (name "unconnected-(IC5-PF3-Pad13)") (class "Default")
      (node (ref "IC5") (pin "13") (pinfunction "PF3_13") (pintype "passive"))
    )
    (net (code "562") (name "unconnected-(IC5-PF5-Pad15)") (class "Default")
      (node (ref "IC5") (pin "15") (pinfunction "PF5_15") (pintype "passive"))
    )
    (net (code "563") (name "unconnected-(IC5-PF6-Pad18)") (class "Default")
      (node (ref "IC5") (pin "18") (pinfunction "PF6_18") (pintype "passive"))
    )
    (net (code "564") (name "unconnected-(IC5-PF7-Pad19)") (class "Default")
      (node (ref "IC5") (pin "19") (pinfunction "PF7_19") (pintype "passive"))
    )
    (net (code "565") (name "unconnected-(IC5-PF8-Pad20)") (class "Default")
      (node (ref "IC5") (pin "20") (pinfunction "PF8_20") (pintype "passive"))
    )
    (net (code "566") (name "unconnected-(IC5-PF9-Pad21)") (class "Default")
      (node (ref "IC5") (pin "21") (pinfunction "PF9_21") (pintype "passive"))
    )
    (net (code "567") (name "unconnected-(IC5-PF10-Pad22)") (class "Default")
      (node (ref "IC5") (pin "22") (pinfunction "PF10_22") (pintype "passive"))
    )
    (net (code "568") (name "unconnected-(IC5-PF11-Pad49)") (class "Default")
      (node (ref "IC5") (pin "49") (pinfunction "PF11_49") (pintype "passive"))
    )
    (net (code "569") (name "unconnected-(IC5-PF12-Pad50)") (class "Default")
      (node (ref "IC5") (pin "50") (pinfunction "PF12_50") (pintype "passive"))
    )
    (net (code "570") (name "unconnected-(IC5-PF13-Pad53)") (class "Default")
      (node (ref "IC5") (pin "53") (pinfunction "PF13_53") (pintype "passive"))
    )
    (net (code "571") (name "unconnected-(IC5-PF14-Pad54)") (class "Default")
      (node (ref "IC5") (pin "54") (pinfunction "PF14_54") (pintype "passive"))
    )
    (net (code "572") (name "unconnected-(IC5-PF15-Pad55)") (class "Default")
      (node (ref "IC5") (pin "55") (pinfunction "PF15_55") (pintype "passive"))
    )
    (net (code "573") (name "unconnected-(IC5-PG0-Pad56)") (class "Default")
      (node (ref "IC5") (pin "56") (pinfunction "PG0_56") (pintype "passive"))
    )
    (net (code "574") (name "unconnected-(IC5-PG1-Pad57)") (class "Default")
      (node (ref "IC5") (pin "57") (pinfunction "PG1_57") (pintype "passive"))
    )
    (net (code "575") (name "unconnected-(IC5-PG2-Pad87)") (class "Default")
      (node (ref "IC5") (pin "87") (pinfunction "PG2_87") (pintype "passive"))
    )
    (net (code "576") (name "unconnected-(IC5-PG3-Pad88)") (class "Default")
      (node (ref "IC5") (pin "88") (pinfunction "PG3_88") (pintype "passive"))
    )
    (net (code "577") (name "unconnected-(IC5-PG4-Pad89)") (class "Default")
      (node (ref "IC5") (pin "89") (pinfunction "PG4_89") (pintype "passive"))
    )
    (net (code "578") (name "unconnected-(IC5-PG5-Pad90)") (class "Default")
      (node (ref "IC5") (pin "90") (pinfunction "PG5_90") (pintype "passive"))
    )
    (net (code "579") (name "unconnected-(IC5-PG6-Pad91)") (class "Default")
      (node (ref "IC5") (pin "91") (pinfunction "PG6_91") (pintype "passive"))
    )
    (net (code "580") (name "unconnected-(IC5-PG7-Pad92)") (class "Default")
      (node (ref "IC5") (pin "92") (pinfunction "PG7_92") (pintype "passive"))
    )
    (net (code "581") (name "unconnected-(IC5-PG8-Pad93)") (class "Default")
      (node (ref "IC5") (pin "93") (pinfunction "PG8_93") (pintype "passive"))
    )
    (net (code "582") (name "unconnected-(IC5-PG9-Pad124)") (class "Default")
      (node (ref "IC5") (pin "124") (pinfunction "PG9_124") (pintype "passive"))
    )
    (net (code "583") (name "unconnected-(IC5-PG10-Pad125)") (class "Default")
      (node (ref "IC5") (pin "125") (pinfunction "PG10_125") (pintype "passive"))
    )
    (net (code "584") (name "unconnected-(IC5-PG11-Pad126)") (class "Default")
      (node (ref "IC5") (pin "126") (pinfunction "PG11_126") (pintype "passive"))
    )
    (net (code "585") (name "unconnected-(IC5-PG12-Pad127)") (class "Default")
      (node (ref "IC5") (pin "127") (pinfunction "PG12_127") (pintype "passive"))
    )
    (net (code "586") (name "unconnected-(IC5-PG13-Pad128)") (class "Default")
      (node (ref "IC5") (pin "128") (pinfunction "PG13_128") (pintype "passive"))
    )
    (net (code "587") (name "unconnected-(IC5-PG14-Pad129)") (class "Default")
      (node (ref "IC5") (pin "129") (pinfunction "PG14_129") (pintype "passive"))
    )
    (net (code "588") (name "unconnected-(IC5-PG15-Pad132)") (class "Default")
      (node (ref "IC5") (pin "132") (pinfunction "PG15_132") (pintype "passive"))
    )
    (net (code "589") (name "unconnected-(IC5-PH0-Pad10)") (class "Default")
      (node (ref "IC5") (pin "10") (pinfunction "PH0_10") (pintype "passive"))
    )
    (net (code "590") (name "unconnected-(IC5-PH1-Pad11)") (class "Default")
      (node (ref "IC5") (pin "11") (pinfunction "PH1_11") (pintype "passive"))
    )
    (net (code "591") (name "unconnected-(IC5-PH2-Pad106)") (class "Default")
      (node (ref "IC5") (pin "106") (pinfunction "PH2_106") (pintype "passive"))
    )
    (net (code "592") (name "unconnected-(IC5-VBAT-Pad6)") (class "Default")
      (node (ref "IC5") (pin "6") (pinfunction "VBAT_6") (pintype "passive"))
    )
    (net (code "593") (name "unconnected-(PS1-CASE_1-Pad9)") (class "Default")
      (node (ref "PS1") (pin "9") (pinfunction "CASE_1_9") (pintype "passive"))
    )
    (net (code "594") (name "unconnected-(PS1-CASE_2-Pad12)") (class "Default")
      (node (ref "PS1") (pin "12") (pinfunction "CASE_2_12") (pintype "passive"))
    )
    (net (code "595") (name "unconnected-(PS1-NC-Pad8)") (class "Default")
      (node (ref "PS1") (pin "8") (pinfunction "NC_8") (pintype "passive"))
    )
    (net (code "596") (name "unconnected-(PS1-ON{slash}OFF-Pad3)") (class "Default")
      (node (ref "PS1") (pin "3") (pinfunction "ON/OFF_3") (pintype "passive"))
    )
  )
)
